# Jupiter_Ace_build023.net
KiCad netlist of a schematic drawn in EAGLE
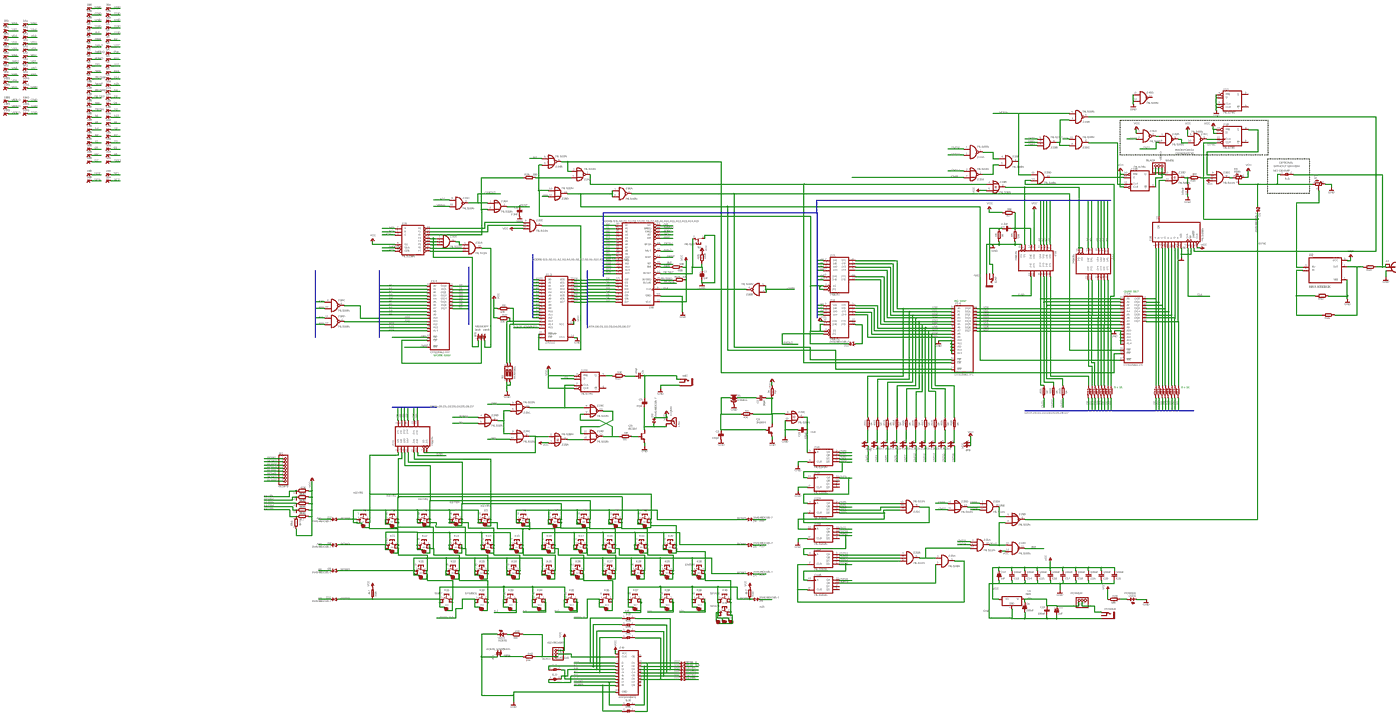
[diagram p0: schematic, sheet 1, overview]
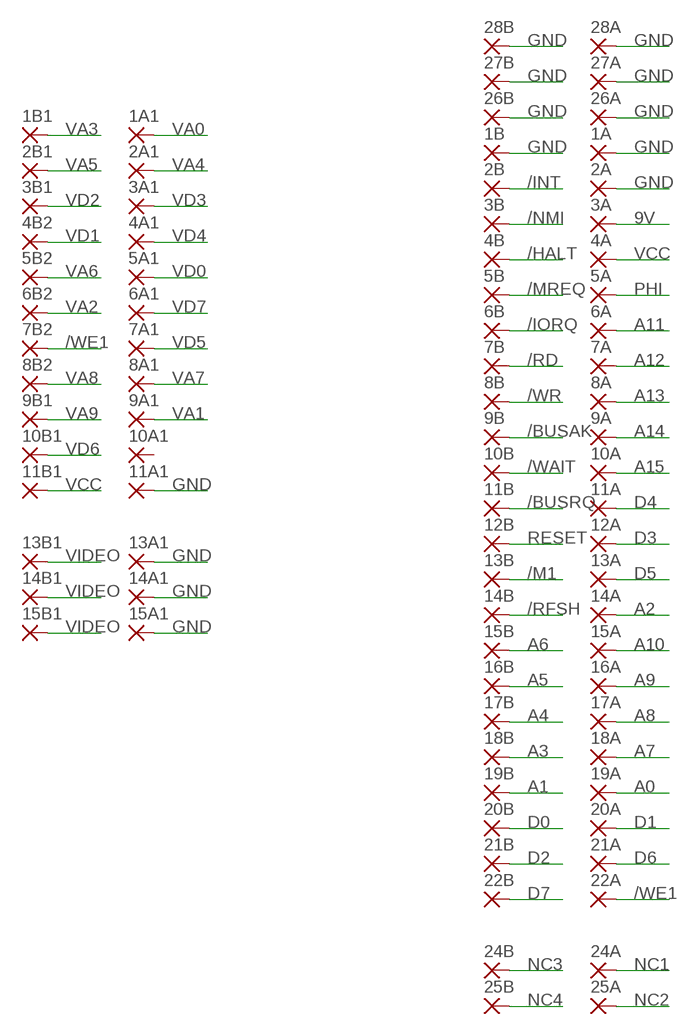
[diagram p1: schematic, sheet 1, part 1 of 5]
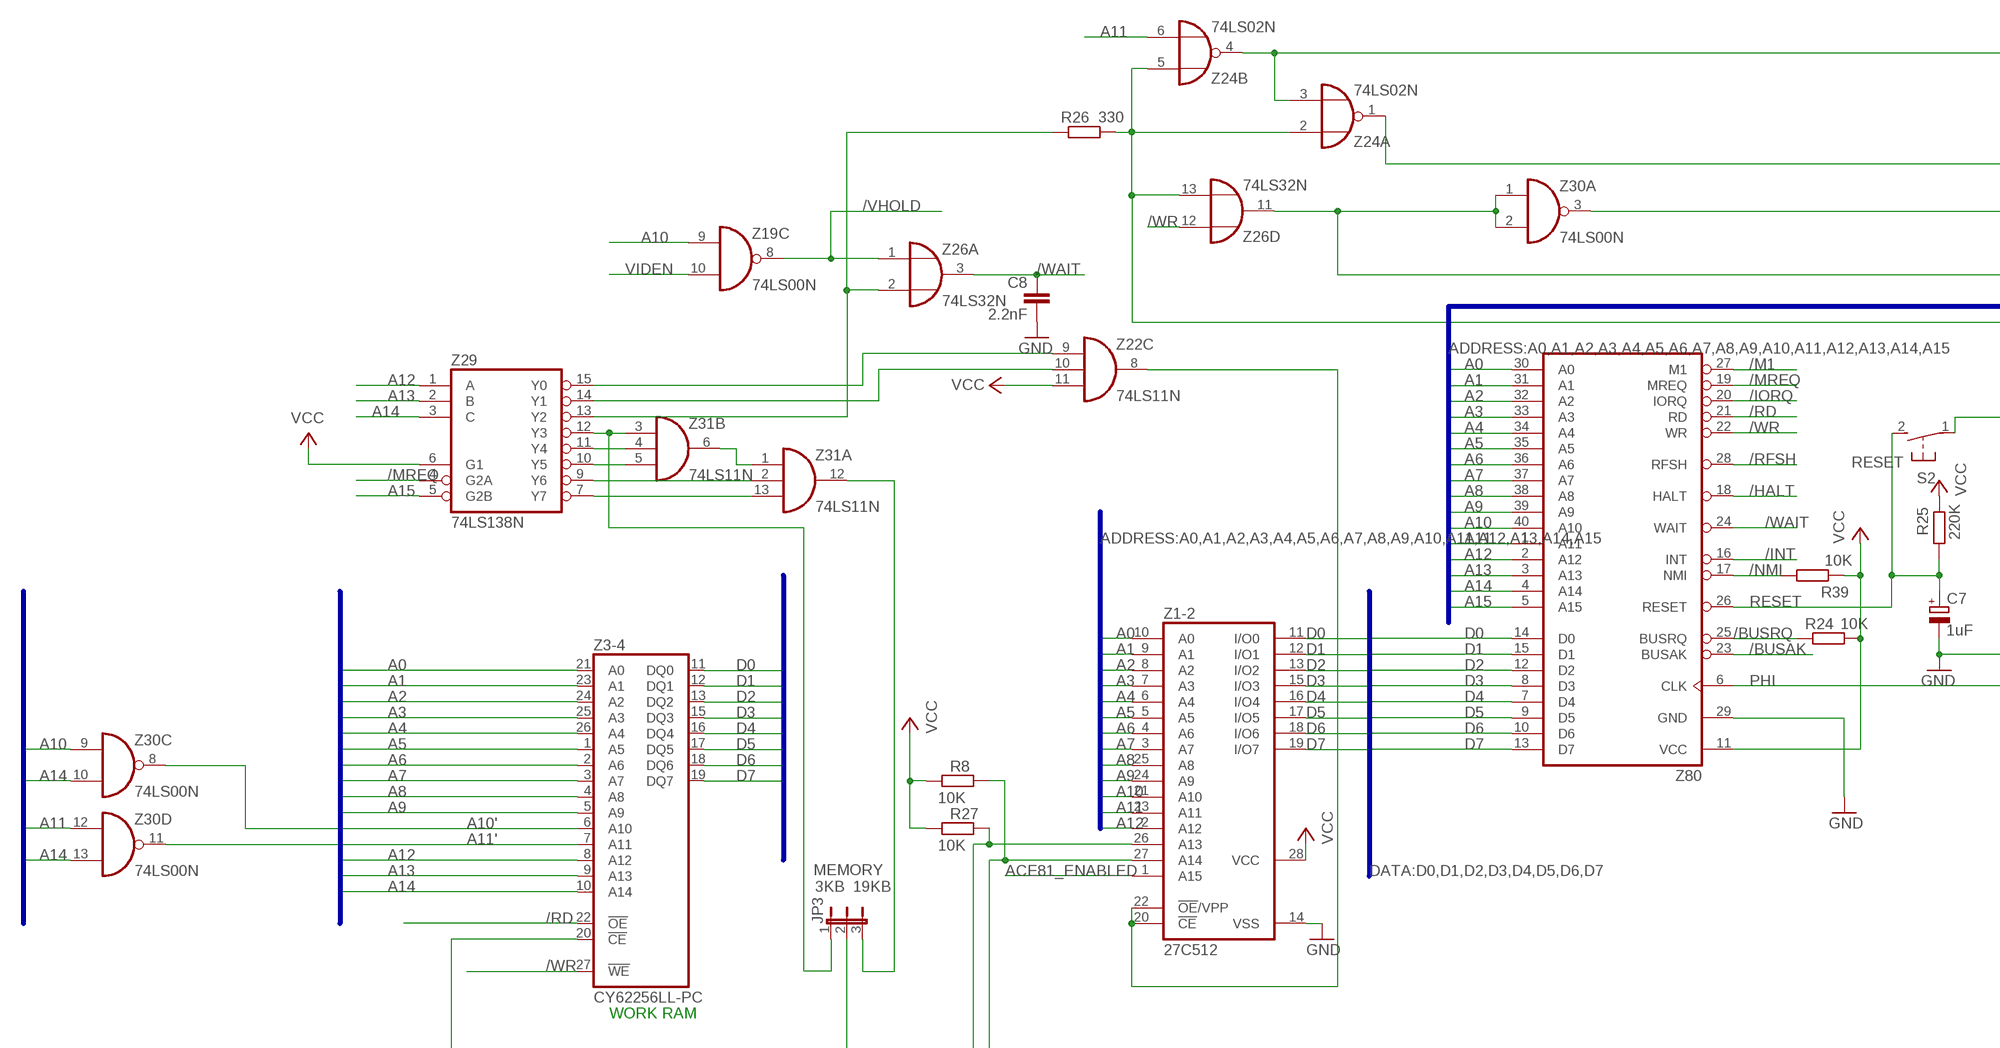
[diagram p2: schematic, sheet 1, part 2 of 5]
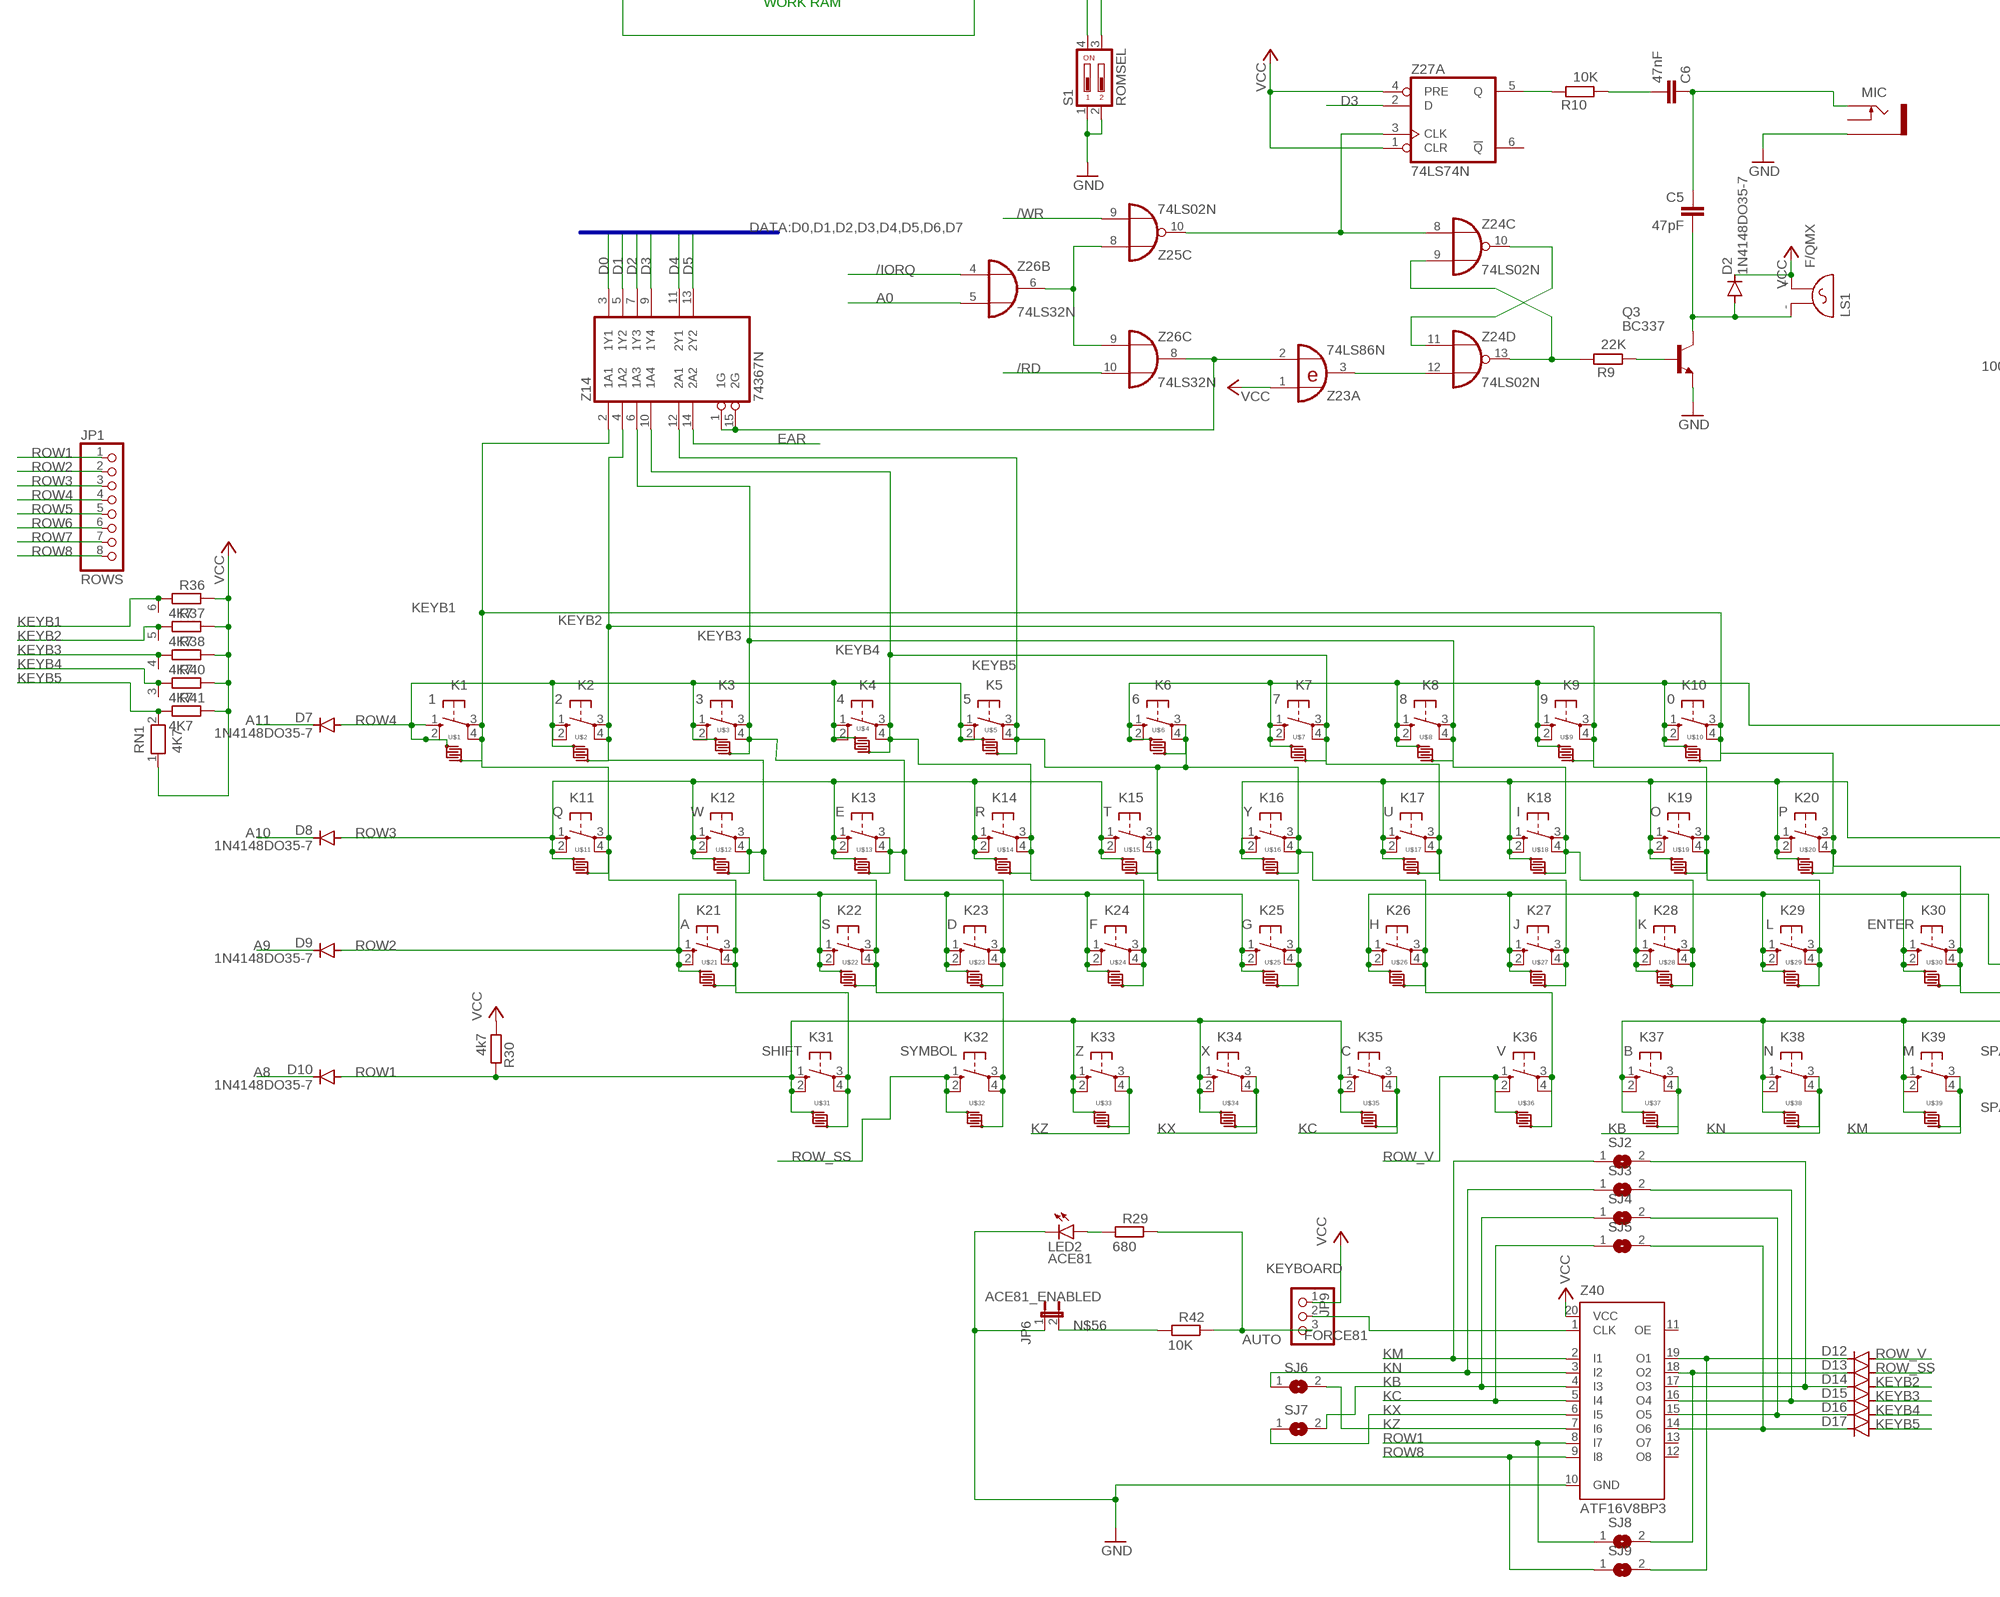
[diagram p3: schematic, sheet 1, part 3 of 5]
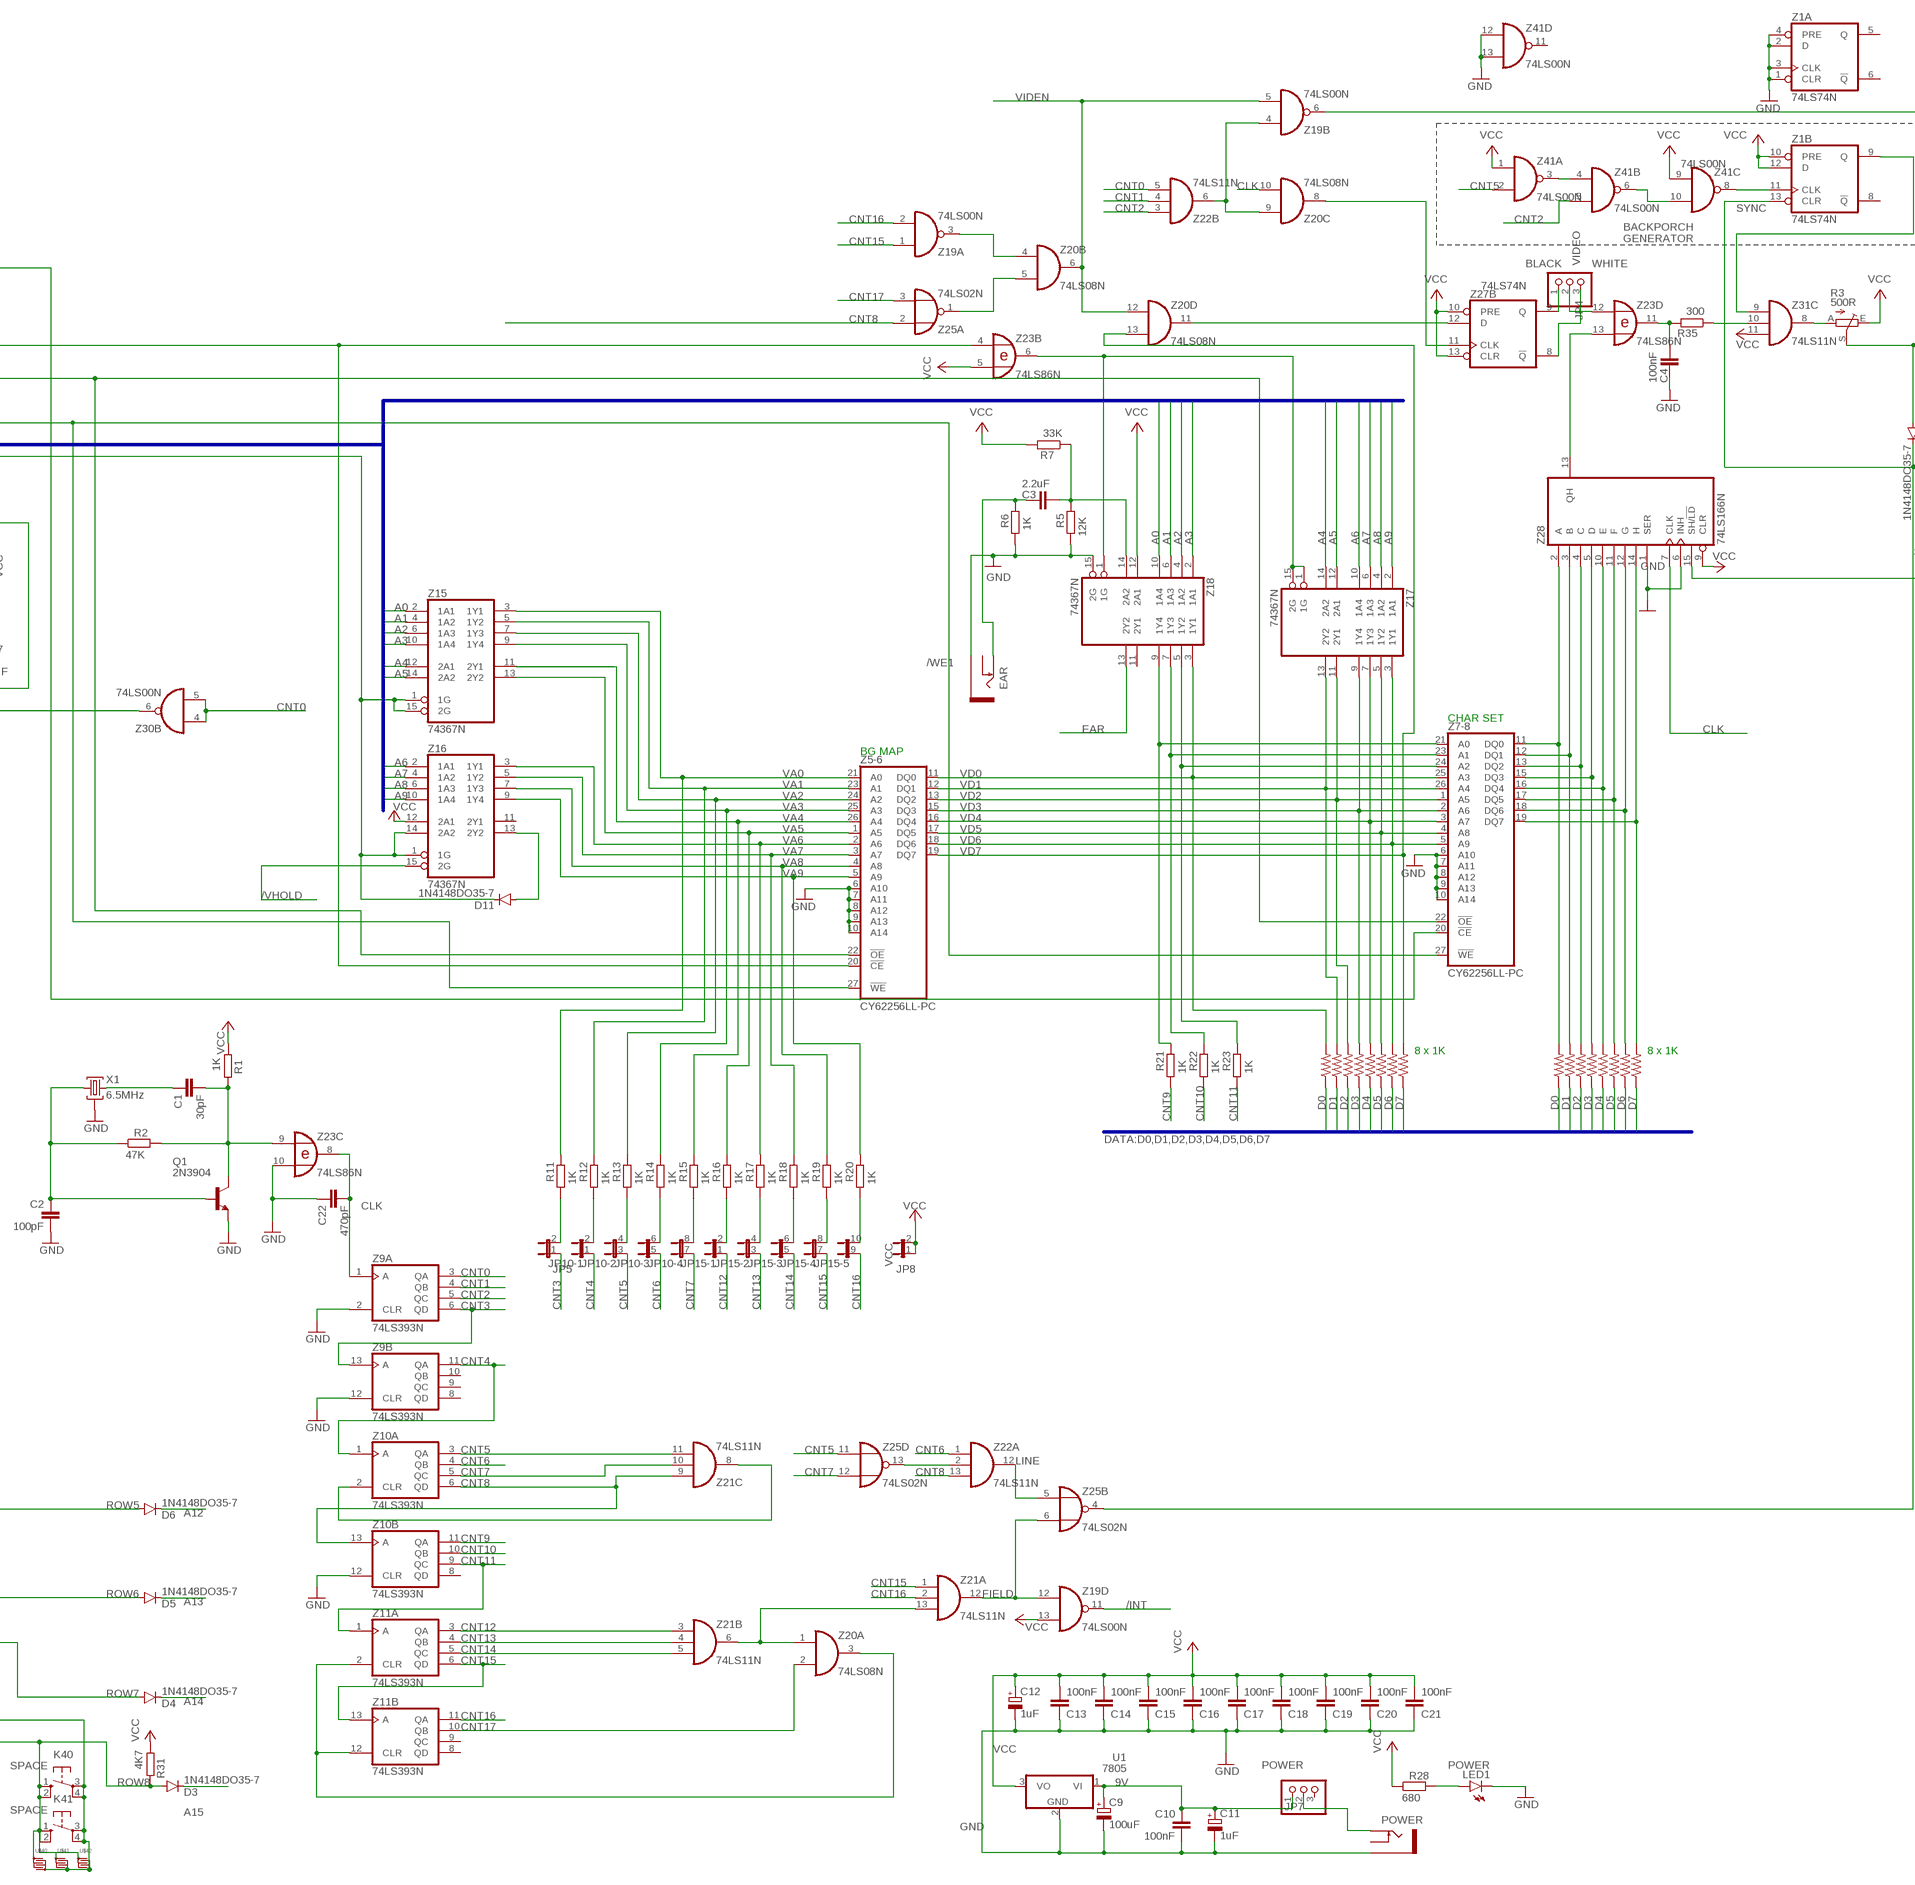
[diagram p4: schematic, sheet 1, part 4 of 5]
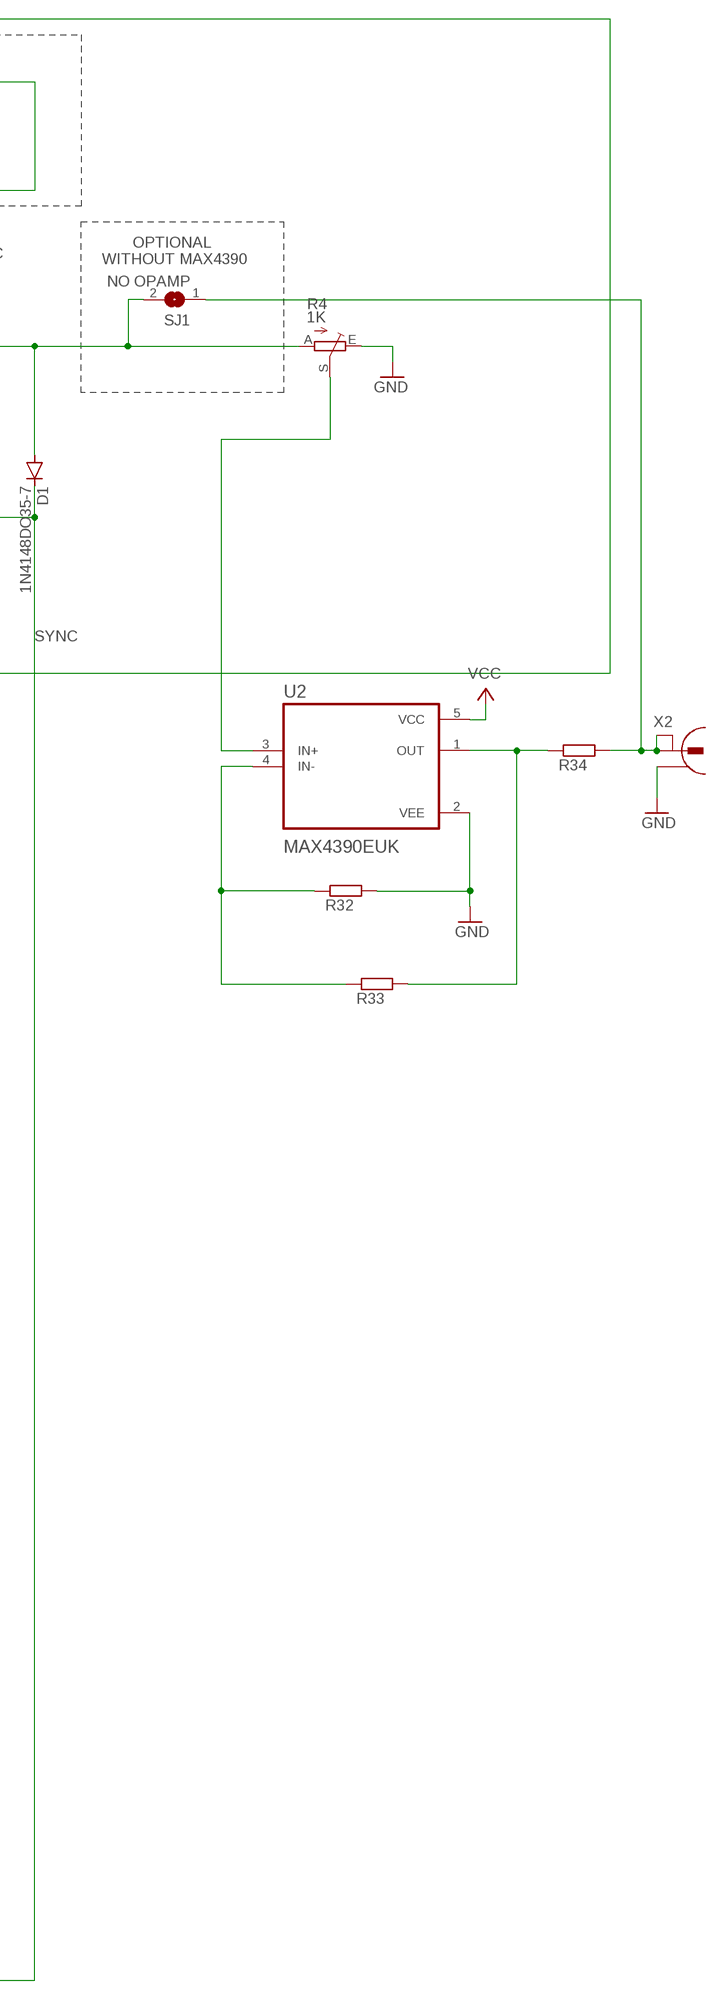
[diagram p5: schematic, sheet 1, part 5 of 5]

(export (version "E")
  (design (tool "Eeschema 10.0.6"))
  (components
    (comp (ref "1A")
      (value "SMD2EDGEPIN")
      (footprint "eagle-import:EDGEPIN")
      (libsource (lib "eagle-import") (part "SMD2EDGEPIN"))
    )
    (comp (ref "1A1")
      (value "SMD2EDGEPIN")
      (footprint "eagle-import:EDGEPIN")
      (libsource (lib "eagle-import") (part "SMD2EDGEPIN"))
    )
    (comp (ref "1B")
      (value "SMD2EDGEPIN")
      (footprint "eagle-import:EDGEPIN")
      (libsource (lib "eagle-import") (part "SMD2EDGEPIN"))
    )
    (comp (ref "1B1")
      (value "SMD2EDGEPIN")
      (footprint "eagle-import:EDGEPIN")
      (libsource (lib "eagle-import") (part "SMD2EDGEPIN"))
    )
    (comp (ref "2A")
      (value "SMD2EDGEPIN")
      (footprint "eagle-import:EDGEPIN")
      (libsource (lib "eagle-import") (part "SMD2EDGEPIN"))
    )
    (comp (ref "2A1")
      (value "SMD2EDGEPIN")
      (footprint "eagle-import:EDGEPIN")
      (libsource (lib "eagle-import") (part "SMD2EDGEPIN"))
    )
    (comp (ref "2B")
      (value "SMD2EDGEPIN")
      (footprint "eagle-import:EDGEPIN")
      (libsource (lib "eagle-import") (part "SMD2EDGEPIN"))
    )
    (comp (ref "2B1")
      (value "SMD2EDGEPIN")
      (footprint "eagle-import:EDGEPIN")
      (libsource (lib "eagle-import") (part "SMD2EDGEPIN"))
    )
    (comp (ref "3A")
      (value "SMD2EDGEPIN")
      (footprint "eagle-import:EDGEPIN")
      (libsource (lib "eagle-import") (part "SMD2EDGEPIN"))
    )
    (comp (ref "3A1")
      (value "SMD2EDGEPIN")
      (footprint "eagle-import:EDGEPIN")
      (libsource (lib "eagle-import") (part "SMD2EDGEPIN"))
    )
    (comp (ref "3B")
      (value "SMD2EDGEPIN")
      (footprint "eagle-import:EDGEPIN")
      (libsource (lib "eagle-import") (part "SMD2EDGEPIN"))
    )
    (comp (ref "3B1")
      (value "SMD2EDGEPIN")
      (footprint "eagle-import:EDGEPIN")
      (libsource (lib "eagle-import") (part "SMD2EDGEPIN"))
    )
    (comp (ref "4A")
      (value "SMD2EDGEPIN")
      (footprint "eagle-import:EDGEPIN")
      (libsource (lib "eagle-import") (part "SMD2EDGEPIN"))
    )
    (comp (ref "4A1")
      (value "SMD2EDGEPIN")
      (footprint "eagle-import:EDGEPIN")
      (libsource (lib "eagle-import") (part "SMD2EDGEPIN"))
    )
    (comp (ref "4B")
      (value "SMD2EDGEPIN")
      (footprint "eagle-import:EDGEPIN")
      (libsource (lib "eagle-import") (part "SMD2EDGEPIN"))
    )
    (comp (ref "4B2")
      (value "SMD2EDGEPIN")
      (footprint "eagle-import:EDGEPIN")
      (libsource (lib "eagle-import") (part "SMD2EDGEPIN"))
    )
    (comp (ref "5A")
      (value "SMD2EDGEPIN")
      (footprint "eagle-import:EDGEPIN")
      (libsource (lib "eagle-import") (part "SMD2EDGEPIN"))
    )
    (comp (ref "5A1")
      (value "SMD2EDGEPIN")
      (footprint "eagle-import:EDGEPIN")
      (libsource (lib "eagle-import") (part "SMD2EDGEPIN"))
    )
    (comp (ref "5B")
      (value "SMD2EDGEPIN")
      (footprint "eagle-import:EDGEPIN")
      (libsource (lib "eagle-import") (part "SMD2EDGEPIN"))
    )
    (comp (ref "5B2")
      (value "SMD2EDGEPIN")
      (footprint "eagle-import:EDGEPIN")
      (libsource (lib "eagle-import") (part "SMD2EDGEPIN"))
    )
    (comp (ref "6A")
      (value "SMD2EDGEPIN")
      (footprint "eagle-import:EDGEPIN")
      (libsource (lib "eagle-import") (part "SMD2EDGEPIN"))
    )
    (comp (ref "6A1")
      (value "SMD2EDGEPIN")
      (footprint "eagle-import:EDGEPIN")
      (libsource (lib "eagle-import") (part "SMD2EDGEPIN"))
    )
    (comp (ref "6B")
      (value "SMD2EDGEPIN")
      (footprint "eagle-import:EDGEPIN")
      (libsource (lib "eagle-import") (part "SMD2EDGEPIN"))
    )
    (comp (ref "6B2")
      (value "SMD2EDGEPIN")
      (footprint "eagle-import:EDGEPIN")
      (libsource (lib "eagle-import") (part "SMD2EDGEPIN"))
    )
    (comp (ref "7A")
      (value "SMD2EDGEPIN")
      (footprint "eagle-import:EDGEPIN")
      (libsource (lib "eagle-import") (part "SMD2EDGEPIN"))
    )
    (comp (ref "7A1")
      (value "SMD2EDGEPIN")
      (footprint "eagle-import:EDGEPIN")
      (libsource (lib "eagle-import") (part "SMD2EDGEPIN"))
    )
    (comp (ref "7B")
      (value "SMD2EDGEPIN")
      (footprint "eagle-import:EDGEPIN")
      (libsource (lib "eagle-import") (part "SMD2EDGEPIN"))
    )
    (comp (ref "7B2")
      (value "SMD2EDGEPIN")
      (footprint "eagle-import:EDGEPIN")
      (libsource (lib "eagle-import") (part "SMD2EDGEPIN"))
    )
    (comp (ref "8A")
      (value "SMD2EDGEPIN")
      (footprint "eagle-import:EDGEPIN")
      (libsource (lib "eagle-import") (part "SMD2EDGEPIN"))
    )
    (comp (ref "8A1")
      (value "SMD2EDGEPIN")
      (footprint "eagle-import:EDGEPIN")
      (libsource (lib "eagle-import") (part "SMD2EDGEPIN"))
    )
    (comp (ref "8B")
      (value "SMD2EDGEPIN")
      (footprint "eagle-import:EDGEPIN")
      (libsource (lib "eagle-import") (part "SMD2EDGEPIN"))
    )
    (comp (ref "8B2")
      (value "SMD2EDGEPIN")
      (footprint "eagle-import:EDGEPIN")
      (libsource (lib "eagle-import") (part "SMD2EDGEPIN"))
    )
    (comp (ref "9A")
      (value "SMD2EDGEPIN")
      (footprint "eagle-import:EDGEPIN")
      (libsource (lib "eagle-import") (part "SMD2EDGEPIN"))
    )
    (comp (ref "9A1")
      (value "SMD2EDGEPIN")
      (footprint "eagle-import:EDGEPIN")
      (libsource (lib "eagle-import") (part "SMD2EDGEPIN"))
    )
    (comp (ref "9B")
      (value "SMD2EDGEPIN")
      (footprint "eagle-import:EDGEPIN")
      (libsource (lib "eagle-import") (part "SMD2EDGEPIN"))
    )
    (comp (ref "9B1")
      (value "SMD2EDGEPIN")
      (footprint "eagle-import:EDGEPIN")
      (libsource (lib "eagle-import") (part "SMD2EDGEPIN"))
    )
    (comp (ref "10A")
      (value "SMD2EDGEPIN")
      (footprint "eagle-import:EDGEPIN")
      (libsource (lib "eagle-import") (part "SMD2EDGEPIN"))
    )
    (comp (ref "10A1")
      (value "SMD2EDGEPIN")
      (footprint "eagle-import:EDGEPIN")
      (libsource (lib "eagle-import") (part "SMD2EDGEPIN"))
    )
    (comp (ref "10B")
      (value "SMD2EDGEPIN")
      (footprint "eagle-import:EDGEPIN")
      (libsource (lib "eagle-import") (part "SMD2EDGEPIN"))
    )
    (comp (ref "10B1")
      (value "SMD2EDGEPIN")
      (footprint "eagle-import:EDGEPIN")
      (libsource (lib "eagle-import") (part "SMD2EDGEPIN"))
    )
    (comp (ref "11A")
      (value "SMD2EDGEPIN")
      (footprint "eagle-import:EDGEPIN")
      (libsource (lib "eagle-import") (part "SMD2EDGEPIN"))
    )
    (comp (ref "11A1")
      (value "SMD2EDGEPIN")
      (footprint "eagle-import:EDGEPIN")
      (libsource (lib "eagle-import") (part "SMD2EDGEPIN"))
    )
    (comp (ref "11B")
      (value "SMD2EDGEPIN")
      (footprint "eagle-import:EDGEPIN")
      (libsource (lib "eagle-import") (part "SMD2EDGEPIN"))
    )
    (comp (ref "11B1")
      (value "SMD2EDGEPIN")
      (footprint "eagle-import:EDGEPIN")
      (libsource (lib "eagle-import") (part "SMD2EDGEPIN"))
    )
    (comp (ref "12A")
      (value "SMD2EDGEPIN")
      (footprint "eagle-import:EDGEPIN")
      (libsource (lib "eagle-import") (part "SMD2EDGEPIN"))
    )
    (comp (ref "12B")
      (value "SMD2EDGEPIN")
      (footprint "eagle-import:EDGEPIN")
      (libsource (lib "eagle-import") (part "SMD2EDGEPIN"))
    )
    (comp (ref "13A")
      (value "SMD2EDGEPIN")
      (footprint "eagle-import:EDGEPIN")
      (libsource (lib "eagle-import") (part "SMD2EDGEPIN"))
    )
    (comp (ref "13A1")
      (value "SMD2EDGEPIN")
      (footprint "eagle-import:EDGEPIN")
      (libsource (lib "eagle-import") (part "SMD2EDGEPIN"))
    )
    (comp (ref "13B")
      (value "SMD2EDGEPIN")
      (footprint "eagle-import:EDGEPIN")
      (libsource (lib "eagle-import") (part "SMD2EDGEPIN"))
    )
    (comp (ref "13B1")
      (value "SMD2EDGEPIN")
      (footprint "eagle-import:EDGEPIN")
      (libsource (lib "eagle-import") (part "SMD2EDGEPIN"))
    )
    (comp (ref "14A")
      (value "SMD2EDGEPIN")
      (footprint "eagle-import:EDGEPIN")
      (libsource (lib "eagle-import") (part "SMD2EDGEPIN"))
    )
    (comp (ref "14A1")
      (value "SMD2EDGEPIN")
      (footprint "eagle-import:EDGEPIN")
      (libsource (lib "eagle-import") (part "SMD2EDGEPIN"))
    )
    (comp (ref "14B")
      (value "SMD2EDGEPIN")
      (footprint "eagle-import:EDGEPIN")
      (libsource (lib "eagle-import") (part "SMD2EDGEPIN"))
    )
    (comp (ref "14B1")
      (value "SMD2EDGEPIN")
      (footprint "eagle-import:EDGEPIN")
      (libsource (lib "eagle-import") (part "SMD2EDGEPIN"))
    )
    (comp (ref "15A")
      (value "SMD2EDGEPIN")
      (footprint "eagle-import:EDGEPIN")
      (libsource (lib "eagle-import") (part "SMD2EDGEPIN"))
    )
    (comp (ref "15A1")
      (value "SMD2EDGEPIN")
      (footprint "eagle-import:EDGEPIN")
      (libsource (lib "eagle-import") (part "SMD2EDGEPIN"))
    )
    (comp (ref "15B")
      (value "SMD2EDGEPIN")
      (footprint "eagle-import:EDGEPIN")
      (libsource (lib "eagle-import") (part "SMD2EDGEPIN"))
    )
    (comp (ref "15B1")
      (value "SMD2EDGEPIN")
      (footprint "eagle-import:EDGEPIN")
      (libsource (lib "eagle-import") (part "SMD2EDGEPIN"))
    )
    (comp (ref "16A")
      (value "SMD2EDGEPIN")
      (footprint "eagle-import:EDGEPIN")
      (libsource (lib "eagle-import") (part "SMD2EDGEPIN"))
    )
    (comp (ref "16B")
      (value "SMD2EDGEPIN")
      (footprint "eagle-import:EDGEPIN")
      (libsource (lib "eagle-import") (part "SMD2EDGEPIN"))
    )
    (comp (ref "17A")
      (value "SMD2EDGEPIN")
      (footprint "eagle-import:EDGEPIN")
      (libsource (lib "eagle-import") (part "SMD2EDGEPIN"))
    )
    (comp (ref "17B")
      (value "SMD2EDGEPIN")
      (footprint "eagle-import:EDGEPIN")
      (libsource (lib "eagle-import") (part "SMD2EDGEPIN"))
    )
    (comp (ref "18A")
      (value "SMD2EDGEPIN")
      (footprint "eagle-import:EDGEPIN")
      (libsource (lib "eagle-import") (part "SMD2EDGEPIN"))
    )
    (comp (ref "18B")
      (value "SMD2EDGEPIN")
      (footprint "eagle-import:EDGEPIN")
      (libsource (lib "eagle-import") (part "SMD2EDGEPIN"))
    )
    (comp (ref "19A")
      (value "SMD2EDGEPIN")
      (footprint "eagle-import:EDGEPIN")
      (libsource (lib "eagle-import") (part "SMD2EDGEPIN"))
    )
    (comp (ref "19B")
      (value "SMD2EDGEPIN")
      (footprint "eagle-import:EDGEPIN")
      (libsource (lib "eagle-import") (part "SMD2EDGEPIN"))
    )
    (comp (ref "20A")
      (value "SMD2EDGEPIN")
      (footprint "eagle-import:EDGEPIN")
      (libsource (lib "eagle-import") (part "SMD2EDGEPIN"))
    )
    (comp (ref "20B")
      (value "SMD2EDGEPIN")
      (footprint "eagle-import:EDGEPIN")
      (libsource (lib "eagle-import") (part "SMD2EDGEPIN"))
    )
    (comp (ref "21A")
      (value "SMD2EDGEPIN")
      (footprint "eagle-import:EDGEPIN")
      (libsource (lib "eagle-import") (part "SMD2EDGEPIN"))
    )
    (comp (ref "21B")
      (value "SMD2EDGEPIN")
      (footprint "eagle-import:EDGEPIN")
      (libsource (lib "eagle-import") (part "SMD2EDGEPIN"))
    )
    (comp (ref "22A")
      (value "SMD2EDGEPIN")
      (footprint "eagle-import:EDGEPIN")
      (libsource (lib "eagle-import") (part "SMD2EDGEPIN"))
    )
    (comp (ref "22B")
      (value "SMD2EDGEPIN")
      (footprint "eagle-import:EDGEPIN")
      (libsource (lib "eagle-import") (part "SMD2EDGEPIN"))
    )
    (comp (ref "24A")
      (value "SMD2EDGEPIN")
      (footprint "eagle-import:EDGEPIN")
      (libsource (lib "eagle-import") (part "SMD2EDGEPIN"))
    )
    (comp (ref "24B")
      (value "SMD2EDGEPIN")
      (footprint "eagle-import:EDGEPIN")
      (libsource (lib "eagle-import") (part "SMD2EDGEPIN"))
    )
    (comp (ref "25A")
      (value "SMD2EDGEPIN")
      (footprint "eagle-import:EDGEPIN")
      (libsource (lib "eagle-import") (part "SMD2EDGEPIN"))
    )
    (comp (ref "25B")
      (value "SMD2EDGEPIN")
      (footprint "eagle-import:EDGEPIN")
      (libsource (lib "eagle-import") (part "SMD2EDGEPIN"))
    )
    (comp (ref "26A")
      (value "SMD2EDGEPIN")
      (footprint "eagle-import:EDGEPIN")
      (libsource (lib "eagle-import") (part "SMD2EDGEPIN"))
    )
    (comp (ref "26B")
      (value "SMD2EDGEPIN")
      (footprint "eagle-import:EDGEPIN")
      (libsource (lib "eagle-import") (part "SMD2EDGEPIN"))
    )
    (comp (ref "27A")
      (value "SMD2EDGEPIN")
      (footprint "eagle-import:EDGEPIN")
      (libsource (lib "eagle-import") (part "SMD2EDGEPIN"))
    )
    (comp (ref "27B")
      (value "SMD2EDGEPIN")
      (footprint "eagle-import:EDGEPIN")
      (libsource (lib "eagle-import") (part "SMD2EDGEPIN"))
    )
    (comp (ref "28A")
      (value "SMD2EDGEPIN")
      (footprint "eagle-import:EDGEPIN")
      (libsource (lib "eagle-import") (part "SMD2EDGEPIN"))
    )
    (comp (ref "28B")
      (value "SMD2EDGEPIN")
      (footprint "eagle-import:EDGEPIN")
      (libsource (lib "eagle-import") (part "SMD2EDGEPIN"))
    )
    (comp (ref "C1")
      (value "30pF")
      (footprint "eagle-import:C025-025X050")
      (libsource (lib "eagle-import") (part "C-EU025-025X050"))
    )
    (comp (ref "C2")
      (value "100pF")
      (footprint "eagle-import:C025-025X050")
      (libsource (lib "eagle-import") (part "C-EU025-025X050"))
    )
    (comp (ref "C3")
      (value "2.2uF")
      (footprint "eagle-import:C025-025X050")
      (libsource (lib "eagle-import") (part "C-EU025-025X050"))
    )
    (comp (ref "C4")
      (value "100nF")
      (footprint "eagle-import:C025-025X050")
      (libsource (lib "eagle-import") (part "C-EU025-025X050"))
    )
    (comp (ref "C5")
      (value "47pF")
      (footprint "eagle-import:C025-025X050")
      (libsource (lib "eagle-import") (part "C-EU025-025X050"))
    )
    (comp (ref "C6")
      (value "47nF")
      (footprint "eagle-import:C025-025X050")
      (libsource (lib "eagle-import") (part "C-EU025-025X050"))
    )
    (comp (ref "C7")
      (value "1uF")
      (footprint "eagle-import:E1,8-4")
      (libsource (lib "eagle-import") (part "CPOL-EUE1.8-4"))
    )
    (comp (ref "C8")
      (value "2.2nF")
      (footprint "eagle-import:C025-025X050")
      (libsource (lib "eagle-import") (part "C-EU025-025X050"))
    )
    (comp (ref "C9")
      (value "100uF")
      (footprint "eagle-import:E1,8-4")
      (libsource (lib "eagle-import") (part "CPOL-EUE1.8-4"))
    )
    (comp (ref "C10")
      (value "100nF")
      (footprint "eagle-import:C025-025X050")
      (libsource (lib "eagle-import") (part "C-EU025-025X050"))
    )
    (comp (ref "C11")
      (value "1uF")
      (footprint "eagle-import:E1,8-4")
      (libsource (lib "eagle-import") (part "CPOL-EUE1.8-4"))
    )
    (comp (ref "C12")
      (value "1uF")
      (footprint "eagle-import:E1,8-4")
      (libsource (lib "eagle-import") (part "CPOL-EUE1.8-4"))
    )
    (comp (ref "C13")
      (value "100nF")
      (footprint "eagle-import:C025-025X050")
      (libsource (lib "eagle-import") (part "C-EU025-025X050"))
    )
    (comp (ref "C14")
      (value "100nF")
      (footprint "eagle-import:C025-025X050")
      (libsource (lib "eagle-import") (part "C-EU025-025X050"))
    )
    (comp (ref "C15")
      (value "100nF")
      (footprint "eagle-import:C025-025X050")
      (libsource (lib "eagle-import") (part "C-EU025-025X050"))
    )
    (comp (ref "C16")
      (value "100nF")
      (footprint "eagle-import:C025-025X050")
      (libsource (lib "eagle-import") (part "C-EU025-025X050"))
    )
    (comp (ref "C17")
      (value "100nF")
      (footprint "eagle-import:C025-025X050")
      (libsource (lib "eagle-import") (part "C-EU025-025X050"))
    )
    (comp (ref "C18")
      (value "100nF")
      (footprint "eagle-import:C025-025X050")
      (libsource (lib "eagle-import") (part "C-EU025-025X050"))
    )
    (comp (ref "C19")
      (value "100nF")
      (footprint "eagle-import:C025-025X050")
      (libsource (lib "eagle-import") (part "C-EU025-025X050"))
    )
    (comp (ref "C20")
      (value "100nF")
      (footprint "eagle-import:C025-025X050")
      (libsource (lib "eagle-import") (part "C-EU025-025X050"))
    )
    (comp (ref "C21")
      (value "100nF")
      (footprint "eagle-import:C025-025X050")
      (libsource (lib "eagle-import") (part "C-EU025-025X050"))
    )
    (comp (ref "C22")
      (value "470pF")
      (footprint "eagle-import:C025-025X050")
      (libsource (lib "eagle-import") (part "C-EU025-025X050"))
    )
    (comp (ref "D1")
      (value "1N4148DO35-7")
      (footprint "eagle-import:DO35-7")
      (libsource (lib "eagle-import") (part "1N4148DO35-7"))
    )
    (comp (ref "D2")
      (value "1N4148DO35-7")
      (footprint "eagle-import:DO35-7")
      (libsource (lib "eagle-import") (part "1N4148DO35-7"))
    )
    (comp (ref "D3")
      (value "1N4148DO35-7")
      (footprint "eagle-import:DO35-7")
      (libsource (lib "eagle-import") (part "1N4148DO35-7"))
    )
    (comp (ref "D4")
      (value "1N4148DO35-7")
      (footprint "eagle-import:DO35-7")
      (libsource (lib "eagle-import") (part "1N4148DO35-7"))
    )
    (comp (ref "D5")
      (value "1N4148DO35-7")
      (footprint "eagle-import:DO35-7")
      (libsource (lib "eagle-import") (part "1N4148DO35-7"))
    )
    (comp (ref "D6")
      (value "1N4148DO35-7")
      (footprint "eagle-import:DO35-7")
      (libsource (lib "eagle-import") (part "1N4148DO35-7"))
    )
    (comp (ref "D7")
      (value "1N4148DO35-7")
      (footprint "eagle-import:DO35-7")
      (libsource (lib "eagle-import") (part "1N4148DO35-7"))
    )
    (comp (ref "D8")
      (value "1N4148DO35-7")
      (footprint "eagle-import:DO35-7")
      (libsource (lib "eagle-import") (part "1N4148DO35-7"))
    )
    (comp (ref "D9")
      (value "1N4148DO35-7")
      (footprint "eagle-import:DO35-7")
      (libsource (lib "eagle-import") (part "1N4148DO35-7"))
    )
    (comp (ref "D10")
      (value "1N4148DO35-7")
      (footprint "eagle-import:DO35-7")
      (libsource (lib "eagle-import") (part "1N4148DO35-7"))
    )
    (comp (ref "D11")
      (value "1N4148DO35-7")
      (footprint "eagle-import:DO35-7")
      (libsource (lib "eagle-import") (part "1N4148DO35-7"))
    )
    (comp (ref "D12")
      (value "1N4148DO35-7")
      (footprint "eagle-import:DO35-7")
      (libsource (lib "eagle-import") (part "1N4148DO35-7"))
    )
    (comp (ref "D13")
      (value "1N4148DO35-7")
      (footprint "eagle-import:DO35-7")
      (libsource (lib "eagle-import") (part "1N4148DO35-7"))
    )
    (comp (ref "D14")
      (value "1N4148DO35-7")
      (footprint "eagle-import:DO35-7")
      (libsource (lib "eagle-import") (part "1N4148DO35-7"))
    )
    (comp (ref "D15")
      (value "1N4148DO35-7")
      (footprint "eagle-import:DO35-7")
      (libsource (lib "eagle-import") (part "1N4148DO35-7"))
    )
    (comp (ref "D16")
      (value "1N4148DO35-7")
      (footprint "eagle-import:DO35-7")
      (libsource (lib "eagle-import") (part "1N4148DO35-7"))
    )
    (comp (ref "D17")
      (value "1N4148DO35-7")
      (footprint "eagle-import:DO35-7")
      (libsource (lib "eagle-import") (part "1N4148DO35-7"))
    )
    (comp (ref "EAR")
      (value "PJ302M")
      (footprint "eagle-import:PJ302M")
      (libsource (lib "eagle-import") (part "PJ302M"))
    )
    (comp (ref "JP1")
      (value "ROWS")
      (footprint "eagle-import:1X08")
      (libsource (lib "eagle-import") (part "PINHD-1X8"))
    )
    (comp (ref "JP3")
      (value "MEMORY")
      (footprint "eagle-import:JP2")
      (libsource (lib "eagle-import") (part "JP2E"))
    )
    (comp (ref "JP4")
      (value "VIDEO")
      (footprint "eagle-import:1X03")
      (libsource (lib "eagle-import") (part "PINHD-1X3"))
    )
    (comp (ref "JP5")
      (value "JP1E1Q")
      (footprint "eagle-import:JP1Q")
      (libsource (lib "eagle-import") (part "JP1E1Q"))
    )
    (comp (ref "JP6")
      (value "ACE81_ENABLED")
      (footprint "eagle-import:JP1Q")
      (libsource (lib "eagle-import") (part "JP1E1Q"))
    )
    (comp (ref "JP7")
      (value "POWER")
      (footprint "eagle-import:1X03")
      (libsource (lib "eagle-import") (part "PINHD-1X3"))
    )
    (comp (ref "JP8")
      (value "VCC")
      (footprint "eagle-import:JP1Q")
      (libsource (lib "eagle-import") (part "JP1E1Q"))
    )
    (comp (ref "JP9")
      (value "KEYBOARD")
      (footprint "eagle-import:1X03")
      (libsource (lib "eagle-import") (part "PINHD-1X3"))
    )
    (comp (ref "JP10")
      (value "JP4QE")
      (footprint "eagle-import:JP4Q")
      (libsource (lib "eagle-import") (part "JP4QE"))
    )
    (comp (ref "JP15")
      (value "JP5QE")
      (footprint "eagle-import:JP5Q")
      (libsource (lib "eagle-import") (part "JP5QE"))
    )
    (comp (ref "K1")
      (value "1")
      (footprint "eagle-import:B3F-40XXNOHOLE")
      (libsource (lib "eagle-import") (part "40-XXNOHOLES"))
    )
    (comp (ref "K2")
      (value "2")
      (footprint "eagle-import:B3F-40XXNOHOLE")
      (libsource (lib "eagle-import") (part "40-XXNOHOLES"))
    )
    (comp (ref "K3")
      (value "3")
      (footprint "eagle-import:B3F-40XXNOHOLE")
      (libsource (lib "eagle-import") (part "40-XXNOHOLES"))
    )
    (comp (ref "K4")
      (value "4")
      (footprint "eagle-import:B3F-40XXNOHOLE")
      (libsource (lib "eagle-import") (part "40-XXNOHOLES"))
    )
    (comp (ref "K5")
      (value "5")
      (footprint "eagle-import:B3F-40XXNOHOLE")
      (libsource (lib "eagle-import") (part "40-XXNOHOLES"))
    )
    (comp (ref "K6")
      (value "6")
      (footprint "eagle-import:B3F-40XXNOHOLE")
      (libsource (lib "eagle-import") (part "40-XXNOHOLES"))
    )
    (comp (ref "K7")
      (value "7")
      (footprint "eagle-import:B3F-40XXNOHOLE")
      (libsource (lib "eagle-import") (part "40-XXNOHOLES"))
    )
    (comp (ref "K8")
      (value "8")
      (footprint "eagle-import:B3F-40XXNOHOLE")
      (libsource (lib "eagle-import") (part "40-XXNOHOLES"))
    )
    (comp (ref "K9")
      (value "9")
      (footprint "eagle-import:B3F-40XXNOHOLE")
      (libsource (lib "eagle-import") (part "40-XXNOHOLES"))
    )
    (comp (ref "K10")
      (value "0")
      (footprint "eagle-import:B3F-40XXNOHOLE")
      (libsource (lib "eagle-import") (part "40-XXNOHOLES"))
    )
    (comp (ref "K11")
      (value "Q")
      (footprint "eagle-import:B3F-40XXNOHOLE")
      (libsource (lib "eagle-import") (part "40-XXNOHOLES"))
    )
    (comp (ref "K12")
      (value "W")
      (footprint "eagle-import:B3F-40XXNOHOLE")
      (libsource (lib "eagle-import") (part "40-XXNOHOLES"))
    )
    (comp (ref "K13")
      (value "E")
      (footprint "eagle-import:B3F-40XXNOHOLE")
      (libsource (lib "eagle-import") (part "40-XXNOHOLES"))
    )
    (comp (ref "K14")
      (value "R")
      (footprint "eagle-import:B3F-40XXNOHOLE")
      (libsource (lib "eagle-import") (part "40-XXNOHOLES"))
    )
    (comp (ref "K15")
      (value "T")
      (footprint "eagle-import:B3F-40XXNOHOLE")
      (libsource (lib "eagle-import") (part "40-XXNOHOLES"))
    )
    (comp (ref "K16")
      (value "Y")
      (footprint "eagle-import:B3F-40XXNOHOLE")
      (libsource (lib "eagle-import") (part "40-XXNOHOLES"))
    )
    (comp (ref "K17")
      (value "U")
      (footprint "eagle-import:B3F-40XXNOHOLE")
      (libsource (lib "eagle-import") (part "40-XXNOHOLES"))
    )
    (comp (ref "K18")
      (value "I")
      (footprint "eagle-import:B3F-40XXNOHOLE")
      (libsource (lib "eagle-import") (part "40-XXNOHOLES"))
    )
    (comp (ref "K19")
      (value "O")
      (footprint "eagle-import:B3F-40XXNOHOLE")
      (libsource (lib "eagle-import") (part "40-XXNOHOLES"))
    )
    (comp (ref "K20")
      (value "P")
      (footprint "eagle-import:B3F-40XXNOHOLE")
      (libsource (lib "eagle-import") (part "40-XXNOHOLES"))
    )
    (comp (ref "K21")
      (value "A")
      (footprint "eagle-import:B3F-40XXNOHOLE")
      (libsource (lib "eagle-import") (part "40-XXNOHOLES"))
    )
    (comp (ref "K22")
      (value "S")
      (footprint "eagle-import:B3F-40XXNOHOLE")
      (libsource (lib "eagle-import") (part "40-XXNOHOLES"))
    )
    (comp (ref "K23")
      (value "D")
      (footprint "eagle-import:B3F-40XXNOHOLE")
      (libsource (lib "eagle-import") (part "40-XXNOHOLES"))
    )
    (comp (ref "K24")
      (value "F")
      (footprint "eagle-import:B3F-40XXNOHOLE")
      (libsource (lib "eagle-import") (part "40-XXNOHOLES"))
    )
    (comp (ref "K25")
      (value "G")
      (footprint "eagle-import:B3F-40XXNOHOLE")
      (libsource (lib "eagle-import") (part "40-XXNOHOLES"))
    )
    (comp (ref "K26")
      (value "H")
      (footprint "eagle-import:B3F-40XXNOHOLE")
      (libsource (lib "eagle-import") (part "40-XXNOHOLES"))
    )
    (comp (ref "K27")
      (value "J")
      (footprint "eagle-import:B3F-40XXNOHOLE")
      (libsource (lib "eagle-import") (part "40-XXNOHOLES"))
    )
    (comp (ref "K28")
      (value "K")
      (footprint "eagle-import:B3F-40XXNOHOLE")
      (libsource (lib "eagle-import") (part "40-XXNOHOLES"))
    )
    (comp (ref "K29")
      (value "L")
      (footprint "eagle-import:B3F-40XXNOHOLE")
      (libsource (lib "eagle-import") (part "40-XXNOHOLES"))
    )
    (comp (ref "K30")
      (value "ENTER")
      (footprint "eagle-import:B3F-40XXNOHOLE")
      (libsource (lib "eagle-import") (part "40-XXNOHOLES"))
    )
    (comp (ref "K31")
      (value "SHIFT")
      (footprint "eagle-import:B3F-40XXNOHOLE")
      (libsource (lib "eagle-import") (part "40-XXNOHOLES"))
    )
    (comp (ref "K32")
      (value "SYMBOL")
      (footprint "eagle-import:B3F-40XXNOHOLE")
      (libsource (lib "eagle-import") (part "40-XXNOHOLES"))
    )
    (comp (ref "K33")
      (value "Z")
      (footprint "eagle-import:B3F-40XXNOHOLE")
      (libsource (lib "eagle-import") (part "40-XXNOHOLES"))
    )
    (comp (ref "K34")
      (value "X")
      (footprint "eagle-import:B3F-40XXNOHOLE")
      (libsource (lib "eagle-import") (part "40-XXNOHOLES"))
    )
    (comp (ref "K35")
      (value "C")
      (footprint "eagle-import:B3F-40XXNOHOLE")
      (libsource (lib "eagle-import") (part "40-XXNOHOLES"))
    )
    (comp (ref "K36")
      (value "V")
      (footprint "eagle-import:B3F-40XXNOHOLE")
      (libsource (lib "eagle-import") (part "40-XXNOHOLES"))
    )
    (comp (ref "K37")
      (value "B")
      (footprint "eagle-import:B3F-40XXNOHOLE")
      (libsource (lib "eagle-import") (part "40-XXNOHOLES"))
    )
    (comp (ref "K38")
      (value "N")
      (footprint "eagle-import:B3F-40XXNOHOLE")
      (libsource (lib "eagle-import") (part "40-XXNOHOLES"))
    )
    (comp (ref "K39")
      (value "M")
      (footprint "eagle-import:B3F-40XXNOHOLE")
      (libsource (lib "eagle-import") (part "40-XXNOHOLES"))
    )
    (comp (ref "K40")
      (value "SPACE")
      (footprint "eagle-import:B3F-40XXNOHOLE")
      (libsource (lib "eagle-import") (part "40-XXNOHOLES"))
    )
    (comp (ref "K41")
      (value "SPACE")
      (footprint "eagle-import:B3F-40XXNOHOLE")
      (libsource (lib "eagle-import") (part "40-XXNOHOLES"))
    )
    (comp (ref "LED1")
      (value "POWER")
      (footprint "eagle-import:LED3MM")
      (libsource (lib "eagle-import") (part "LED3MM"))
    )
    (comp (ref "LED2")
      (value "ACE81")
      (footprint "eagle-import:LED3MM")
      (libsource (lib "eagle-import") (part "LED3MM"))
    )
    (comp (ref "LS1")
      (value "F/QMX")
      (footprint "eagle-import:F_QMX")
      (libsource (lib "eagle-import") (part "F/QMX"))
    )
    (comp (ref "MIC")
      (value "PJ302M")
      (footprint "eagle-import:PJ302M")
      (libsource (lib "eagle-import") (part "PJ302M"))
    )
    (comp (ref "POWER")
      (value "PJ302M")
      (footprint "eagle-import:PJ302M")
      (libsource (lib "eagle-import") (part "PJ302M"))
    )
    (comp (ref "Q1")
      (value "2N3904")
      (footprint "eagle-import:TO92")
      (libsource (lib "eagle-import") (part "2N3904"))
    )
    (comp (ref "Q3")
      (value "BC337")
      (footprint "eagle-import:TO92")
      (libsource (lib "eagle-import") (part "BC337"))
    )
    (comp (ref "R1")
      (value "1K")
      (footprint "eagle-import:0204_7")
      (libsource (lib "eagle-import") (part "R-EU_0204/7"))
    )
    (comp (ref "R2")
      (value "47K")
      (footprint "eagle-import:0204_7")
      (libsource (lib "eagle-import") (part "R-EU_0204/7"))
    )
    (comp (ref "R3")
      (value "500R")
      (footprint "eagle-import:B25P")
      (libsource (lib "eagle-import") (part "TRIM_EU-B25P"))
    )
    (comp (ref "R4")
      (value "1K")
      (footprint "eagle-import:B25P")
      (libsource (lib "eagle-import") (part "TRIM_EU-B25P"))
    )
    (comp (ref "R5")
      (value "12K")
      (footprint "eagle-import:0204_7")
      (libsource (lib "eagle-import") (part "R-EU_0204/7"))
    )
    (comp (ref "R6")
      (value "1K")
      (footprint "eagle-import:0204_7")
      (libsource (lib "eagle-import") (part "R-EU_0204/7"))
    )
    (comp (ref "R7")
      (value "33K")
      (footprint "eagle-import:0204_7")
      (libsource (lib "eagle-import") (part "R-EU_0204/7"))
    )
    (comp (ref "R8")
      (value "10K")
      (footprint "eagle-import:0204_7")
      (libsource (lib "eagle-import") (part "R-EU_0204/7"))
    )
    (comp (ref "R9")
      (value "22K")
      (footprint "eagle-import:0204_7")
      (libsource (lib "eagle-import") (part "R-EU_0204/7"))
    )
    (comp (ref "R10")
      (value "10K")
      (footprint "eagle-import:0204_7")
      (libsource (lib "eagle-import") (part "R-EU_0204/7"))
    )
    (comp (ref "R11")
      (value "1K")
      (footprint "eagle-import:0204_7")
      (libsource (lib "eagle-import") (part "R-EU_0204/7"))
    )
    (comp (ref "R12")
      (value "1K")
      (footprint "eagle-import:0204_7")
      (libsource (lib "eagle-import") (part "R-EU_0204/7"))
    )
    (comp (ref "R13")
      (value "1K")
      (footprint "eagle-import:0204_7")
      (libsource (lib "eagle-import") (part "R-EU_0204/7"))
    )
    (comp (ref "R14")
      (value "1K")
      (footprint "eagle-import:0204_7")
      (libsource (lib "eagle-import") (part "R-EU_0204/7"))
    )
    (comp (ref "R15")
      (value "1K")
      (footprint "eagle-import:0204_7")
      (libsource (lib "eagle-import") (part "R-EU_0204/7"))
    )
    (comp (ref "R16")
      (value "1K")
      (footprint "eagle-import:0204_7")
      (libsource (lib "eagle-import") (part "R-EU_0204/7"))
    )
    (comp (ref "R17")
      (value "1K")
      (footprint "eagle-import:0204_7")
      (libsource (lib "eagle-import") (part "R-EU_0204/7"))
    )
    (comp (ref "R18")
      (value "1K")
      (footprint "eagle-import:0204_7")
      (libsource (lib "eagle-import") (part "R-EU_0204/7"))
    )
    (comp (ref "R19")
      (value "1K")
      (footprint "eagle-import:0204_7")
      (libsource (lib "eagle-import") (part "R-EU_0204/7"))
    )
    (comp (ref "R20")
      (value "1K")
      (footprint "eagle-import:0204_7")
      (libsource (lib "eagle-import") (part "R-EU_0204/7"))
    )
    (comp (ref "R21")
      (value "1K")
      (footprint "eagle-import:0204_7")
      (libsource (lib "eagle-import") (part "R-EU_0204/7"))
    )
    (comp (ref "R22")
      (value "1K")
      (footprint "eagle-import:0204_7")
      (libsource (lib "eagle-import") (part "R-EU_0204/7"))
    )
    (comp (ref "R23")
      (value "1K")
      (footprint "eagle-import:0204_7")
      (libsource (lib "eagle-import") (part "R-EU_0204/7"))
    )
    (comp (ref "R24")
      (value "10K")
      (footprint "eagle-import:0204_7")
      (libsource (lib "eagle-import") (part "R-EU_0204/7"))
    )
    (comp (ref "R25")
      (value "220K")
      (footprint "eagle-import:0204_7")
      (libsource (lib "eagle-import") (part "R-EU_0204/7"))
    )
    (comp (ref "R26")
      (value "330")
      (footprint "eagle-import:0204_7")
      (libsource (lib "eagle-import") (part "R-EU_0204/7"))
    )
    (comp (ref "R27")
      (value "10K")
      (footprint "eagle-import:0204_7")
      (libsource (lib "eagle-import") (part "R-EU_0204/7"))
    )
    (comp (ref "R28")
      (value "680")
      (footprint "eagle-import:0204_7")
      (libsource (lib "eagle-import") (part "R-EU_0204/7"))
    )
    (comp (ref "R29")
      (value "680")
      (footprint "eagle-import:0204_7")
      (libsource (lib "eagle-import") (part "R-EU_0204/7"))
    )
    (comp (ref "R30")
      (value "4k7")
      (footprint "eagle-import:0204_7")
      (libsource (lib "eagle-import") (part "R-EU_0204/7"))
    )
    (comp (ref "R31")
      (value "4K7")
      (footprint "eagle-import:0204_7")
      (libsource (lib "eagle-import") (part "R-EU_0204/7"))
    )
    (comp (ref "R32")
      (value "R-EU_0204/7")
      (footprint "eagle-import:0204_7")
      (libsource (lib "eagle-import") (part "R-EU_0204/7"))
    )
    (comp (ref "R33")
      (value "R-EU_0204/7")
      (footprint "eagle-import:0204_7")
      (libsource (lib "eagle-import") (part "R-EU_0204/7"))
    )
    (comp (ref "R34")
      (value "R-EU_0204/7")
      (footprint "eagle-import:0204_7")
      (libsource (lib "eagle-import") (part "R-EU_0204/7"))
    )
    (comp (ref "R35")
      (value "300")
      (footprint "eagle-import:0204_7")
      (libsource (lib "eagle-import") (part "R-EU_0204/7"))
    )
    (comp (ref "R36")
      (value "4K7")
      (footprint "eagle-import:0207_10")
      (libsource (lib "eagle-import") (part "R-EU_0207/10"))
    )
    (comp (ref "R37")
      (value "4K7")
      (footprint "eagle-import:0207_10")
      (libsource (lib "eagle-import") (part "R-EU_0207/10"))
    )
    (comp (ref "R38")
      (value "4K7")
      (footprint "eagle-import:0207_10")
      (libsource (lib "eagle-import") (part "R-EU_0207/10"))
    )
    (comp (ref "R39")
      (value "10K")
      (footprint "eagle-import:0204_7")
      (libsource (lib "eagle-import") (part "R-EU_0204/7"))
    )
    (comp (ref "R40")
      (value "4K7")
      (footprint "eagle-import:0207_10")
      (libsource (lib "eagle-import") (part "R-EU_0207/10"))
    )
    (comp (ref "R41")
      (value "4K7")
      (footprint "eagle-import:0207_10")
      (libsource (lib "eagle-import") (part "R-EU_0207/10"))
    )
    (comp (ref "R42")
      (value "10K")
      (footprint "eagle-import:0204_7")
      (libsource (lib "eagle-import") (part "R-EU_0204/7"))
    )
    (comp (ref "R100")
      (value "1K")
      (footprint "eagle-import:0204V")
      (libsource (lib "eagle-import") (part "R-US_0204/2V"))
    )
    (comp (ref "R101")
      (value "1K")
      (footprint "eagle-import:0204V")
      (libsource (lib "eagle-import") (part "R-US_0204/2V"))
    )
    (comp (ref "R102")
      (value "1K")
      (footprint "eagle-import:0204V")
      (libsource (lib "eagle-import") (part "R-US_0204/2V"))
    )
    (comp (ref "R103")
      (value "1K")
      (footprint "eagle-import:0204V")
      (libsource (lib "eagle-import") (part "R-US_0204/2V"))
    )
    (comp (ref "R104")
      (value "1K")
      (footprint "eagle-import:0204V")
      (libsource (lib "eagle-import") (part "R-US_0204/2V"))
    )
    (comp (ref "R105")
      (value "1K")
      (footprint "eagle-import:0204V")
      (libsource (lib "eagle-import") (part "R-US_0204/2V"))
    )
    (comp (ref "R106")
      (value "1K")
      (footprint "eagle-import:0204V")
      (libsource (lib "eagle-import") (part "R-US_0204/2V"))
    )
    (comp (ref "R107")
      (value "1K")
      (footprint "eagle-import:0204V")
      (libsource (lib "eagle-import") (part "R-US_0204/2V"))
    )
    (comp (ref "R200")
      (value "1K")
      (footprint "eagle-import:0204V")
      (libsource (lib "eagle-import") (part "R-US_0204/2V"))
    )
    (comp (ref "R201")
      (value "1K")
      (footprint "eagle-import:0204V")
      (libsource (lib "eagle-import") (part "R-US_0204/2V"))
    )
    (comp (ref "R202")
      (value "1K")
      (footprint "eagle-import:0204V")
      (libsource (lib "eagle-import") (part "R-US_0204/2V"))
    )
    (comp (ref "R203")
      (value "1K")
      (footprint "eagle-import:0204V")
      (libsource (lib "eagle-import") (part "R-US_0204/2V"))
    )
    (comp (ref "R204")
      (value "1K")
      (footprint "eagle-import:0204V")
      (libsource (lib "eagle-import") (part "R-US_0204/2V"))
    )
    (comp (ref "R205")
      (value "1K")
      (footprint "eagle-import:0204V")
      (libsource (lib "eagle-import") (part "R-US_0204/2V"))
    )
    (comp (ref "R206")
      (value "1K")
      (footprint "eagle-import:0204V")
      (libsource (lib "eagle-import") (part "R-US_0204/2V"))
    )
    (comp (ref "R207")
      (value "1K")
      (footprint "eagle-import:0204V")
      (libsource (lib "eagle-import") (part "R-US_0204/2V"))
    )
    (comp (ref "RN1")
      (value "4K7")
      (footprint "eagle-import:RN-6")
      (libsource (lib "eagle-import") (part "RN05"))
    )
    (comp (ref "S1")
      (value "ROMSEL")
      (footprint "eagle-import:DS-02")
      (libsource (lib "eagle-import") (part "DS02"))
    )
    (comp (ref "S2")
      (value "RESET")
      (footprint "eagle-import:B3F-31XX")
      (fields (field (name "MPN") "B3F-3100"))
      (libsource (lib "eagle-import") (part "31-XX"))
    )
    (comp (ref "SJ1")
      (value "NO OPAMP")
      (footprint "eagle-import:SJ")
      (libsource (lib "eagle-import") (part "SJ"))
    )
    (comp (ref "SJ2") (value "SJ") (footprint "eagle-import:SJ") (libsource (lib "eagle-import") (part "SJ")))
    (comp (ref "SJ3") (value "SJ") (footprint "eagle-import:SJ") (libsource (lib "eagle-import") (part "SJ")))
    (comp (ref "SJ4") (value "SJ") (footprint "eagle-import:SJ") (libsource (lib "eagle-import") (part "SJ")))
    (comp (ref "SJ5") (value "SJ") (footprint "eagle-import:SJ") (libsource (lib "eagle-import") (part "SJ")))
    (comp (ref "SJ6") (value "SJ") (footprint "eagle-import:SJ") (libsource (lib "eagle-import") (part "SJ")))
    (comp (ref "SJ7") (value "SJ") (footprint "eagle-import:SJ") (libsource (lib "eagle-import") (part "SJ")))
    (comp (ref "SJ8") (value "SJ") (footprint "eagle-import:SJ") (libsource (lib "eagle-import") (part "SJ")))
    (comp (ref "SJ9") (value "SJ") (footprint "eagle-import:SJ") (libsource (lib "eagle-import") (part "SJ")))
    (comp (ref "U$1")
      (value "40-XX-CARBON")
      (footprint "eagle-import:CARBONB3F")
      (libsource (lib "eagle-import") (part "40-XX-CARBON"))
    )
    (comp (ref "U$2")
      (value "40-XX-CARBON")
      (footprint "eagle-import:CARBONB3F")
      (libsource (lib "eagle-import") (part "40-XX-CARBON"))
    )
    (comp (ref "U$3")
      (value "40-XX-CARBON")
      (footprint "eagle-import:CARBONB3F")
      (libsource (lib "eagle-import") (part "40-XX-CARBON"))
    )
    (comp (ref "U$4")
      (value "40-XX-CARBON")
      (footprint "eagle-import:CARBONB3F")
      (libsource (lib "eagle-import") (part "40-XX-CARBON"))
    )
    (comp (ref "U$5")
      (value "40-XX-CARBON")
      (footprint "eagle-import:CARBONB3F")
      (libsource (lib "eagle-import") (part "40-XX-CARBON"))
    )
    (comp (ref "U$6")
      (value "40-XX-CARBON")
      (footprint "eagle-import:CARBONB3F")
      (libsource (lib "eagle-import") (part "40-XX-CARBON"))
    )
    (comp (ref "U$7")
      (value "40-XX-CARBON")
      (footprint "eagle-import:CARBONB3F")
      (libsource (lib "eagle-import") (part "40-XX-CARBON"))
    )
    (comp (ref "U$8")
      (value "40-XX-CARBON")
      (footprint "eagle-import:CARBONB3F")
      (libsource (lib "eagle-import") (part "40-XX-CARBON"))
    )
    (comp (ref "U$9")
      (value "40-XX-CARBON")
      (footprint "eagle-import:CARBONB3F")
      (libsource (lib "eagle-import") (part "40-XX-CARBON"))
    )
    (comp (ref "U$10")
      (value "40-XX-CARBON")
      (footprint "eagle-import:CARBONB3F")
      (libsource (lib "eagle-import") (part "40-XX-CARBON"))
    )
    (comp (ref "U$11")
      (value "40-XX-CARBON")
      (footprint "eagle-import:CARBONB3F")
      (libsource (lib "eagle-import") (part "40-XX-CARBON"))
    )
    (comp (ref "U$12")
      (value "40-XX-CARBON")
      (footprint "eagle-import:CARBONB3F")
      (libsource (lib "eagle-import") (part "40-XX-CARBON"))
    )
    (comp (ref "U$13")
      (value "40-XX-CARBON")
      (footprint "eagle-import:CARBONB3F")
      (libsource (lib "eagle-import") (part "40-XX-CARBON"))
    )
    (comp (ref "U$14")
      (value "40-XX-CARBON")
      (footprint "eagle-import:CARBONB3F")
      (libsource (lib "eagle-import") (part "40-XX-CARBON"))
    )
    (comp (ref "U$15")
      (value "40-XX-CARBON")
      (footprint "eagle-import:CARBONB3F")
      (libsource (lib "eagle-import") (part "40-XX-CARBON"))
    )
    (comp (ref "U$16")
      (value "40-XX-CARBON")
      (footprint "eagle-import:CARBONB3F")
      (libsource (lib "eagle-import") (part "40-XX-CARBON"))
    )
    (comp (ref "U$17")
      (value "40-XX-CARBON")
      (footprint "eagle-import:CARBONB3F")
      (libsource (lib "eagle-import") (part "40-XX-CARBON"))
    )
    (comp (ref "U$18")
      (value "40-XX-CARBON")
      (footprint "eagle-import:CARBONB3F")
      (libsource (lib "eagle-import") (part "40-XX-CARBON"))
    )
    (comp (ref "U$19")
      (value "40-XX-CARBON")
      (footprint "eagle-import:CARBONB3F")
      (libsource (lib "eagle-import") (part "40-XX-CARBON"))
    )
    (comp (ref "U$20")
      (value "40-XX-CARBON")
      (footprint "eagle-import:CARBONB3F")
      (libsource (lib "eagle-import") (part "40-XX-CARBON"))
    )
    (comp (ref "U$21")
      (value "40-XX-CARBON")
      (footprint "eagle-import:CARBONB3F")
      (libsource (lib "eagle-import") (part "40-XX-CARBON"))
    )
    (comp (ref "U$22")
      (value "40-XX-CARBON")
      (footprint "eagle-import:CARBONB3F")
      (libsource (lib "eagle-import") (part "40-XX-CARBON"))
    )
    (comp (ref "U$23")
      (value "40-XX-CARBON")
      (footprint "eagle-import:CARBONB3F")
      (libsource (lib "eagle-import") (part "40-XX-CARBON"))
    )
    (comp (ref "U$24")
      (value "40-XX-CARBON")
      (footprint "eagle-import:CARBONB3F")
      (libsource (lib "eagle-import") (part "40-XX-CARBON"))
    )
    (comp (ref "U$25")
      (value "40-XX-CARBON")
      (footprint "eagle-import:CARBONB3F")
      (libsource (lib "eagle-import") (part "40-XX-CARBON"))
    )
    (comp (ref "U$26")
      (value "40-XX-CARBON")
      (footprint "eagle-import:CARBONB3F")
      (libsource (lib "eagle-import") (part "40-XX-CARBON"))
    )
    (comp (ref "U$27")
      (value "40-XX-CARBON")
      (footprint "eagle-import:CARBONB3F")
      (libsource (lib "eagle-import") (part "40-XX-CARBON"))
    )
    (comp (ref "U$28")
      (value "40-XX-CARBON")
      (footprint "eagle-import:CARBONB3F")
      (libsource (lib "eagle-import") (part "40-XX-CARBON"))
    )
    (comp (ref "U$29")
      (value "40-XX-CARBON")
      (footprint "eagle-import:CARBONB3F")
      (libsource (lib "eagle-import") (part "40-XX-CARBON"))
    )
    (comp (ref "U$30")
      (value "40-XX-CARBON")
      (footprint "eagle-import:CARBONB3F")
      (libsource (lib "eagle-import") (part "40-XX-CARBON"))
    )
    (comp (ref "U$31")
      (value "40-XX-CARBON")
      (footprint "eagle-import:CARBONB3F")
      (libsource (lib "eagle-import") (part "40-XX-CARBON"))
    )
    (comp (ref "U$32")
      (value "40-XX-CARBON")
      (footprint "eagle-import:CARBONB3F")
      (libsource (lib "eagle-import") (part "40-XX-CARBON"))
    )
    (comp (ref "U$33")
      (value "40-XX-CARBON")
      (footprint "eagle-import:CARBONB3F")
      (libsource (lib "eagle-import") (part "40-XX-CARBON"))
    )
    (comp (ref "U$34")
      (value "40-XX-CARBON")
      (footprint "eagle-import:CARBONB3F")
      (libsource (lib "eagle-import") (part "40-XX-CARBON"))
    )
    (comp (ref "U$35")
      (value "40-XX-CARBON")
      (footprint "eagle-import:CARBONB3F")
      (libsource (lib "eagle-import") (part "40-XX-CARBON"))
    )
    (comp (ref "U$36")
      (value "40-XX-CARBON")
      (footprint "eagle-import:CARBONB3F")
      (libsource (lib "eagle-import") (part "40-XX-CARBON"))
    )
    (comp (ref "U$37")
      (value "40-XX-CARBON")
      (footprint "eagle-import:CARBONB3F")
      (libsource (lib "eagle-import") (part "40-XX-CARBON"))
    )
    (comp (ref "U$38")
      (value "40-XX-CARBON")
      (footprint "eagle-import:CARBONB3F")
      (libsource (lib "eagle-import") (part "40-XX-CARBON"))
    )
    (comp (ref "U$39")
      (value "40-XX-CARBON")
      (footprint "eagle-import:CARBONB3F")
      (libsource (lib "eagle-import") (part "40-XX-CARBON"))
    )
    (comp (ref "U$40")
      (value "40-XX-CARBON")
      (footprint "eagle-import:CARBONB3F")
      (libsource (lib "eagle-import") (part "40-XX-CARBON"))
    )
    (comp (ref "U$41")
      (value "40-XX-CARBON")
      (footprint "eagle-import:CARBONB3F")
      (libsource (lib "eagle-import") (part "40-XX-CARBON"))
    )
    (comp (ref "U$42")
      (value "40-XX-CARBON")
      (footprint "eagle-import:CARBONB3F")
      (libsource (lib "eagle-import") (part "40-XX-CARBON"))
    )
    (comp (ref "U1")
      (value "7805")
      (footprint "eagle-import:TO220V")
      (libsource (lib "eagle-import") (part "78TV05"))
    )
    (comp (ref "U2")
      (value "MAX4390EUK")
      (footprint "eagle-import:SOT95P280X145-5N")
      (fields (field (name "MF") "Maxim Integrated") (field (name "MP") "MAX4390EUK+T"))
      (libsource (lib "eagle-import") (part "MAX4390EUK"))
    )
    (comp (ref "X1")
      (value "6.5MHz")
      (footprint "eagle-import:HC49U")
      (libsource (lib "eagle-import") (part "8M10AHC49T"))
    )
    (comp (ref "X2")
      (value "CON-CONRAD_736880-49")
      (footprint "eagle-import:CON-CONRAD_736880-49")
      (libsource (lib "eagle-import") (part "CON-CONRAD_736880-49"))
    )
    (comp (ref "Z0")
      (value "Z80")
      (footprint "eagle-import:DIL40")
      (libsource (lib "eagle-import") (part "Z80CPU"))
    )
    (comp (ref "Z1")
      (value "74LS74N")
      (footprint "eagle-import:DIL14")
      (libsource (lib "eagle-import") (part "7474NLS"))
    )
    (comp (ref "Z1-2")
      (value "27C512")
      (footprint "eagle-import:DIL28-6")
      (libsource (lib "eagle-import") (part "27512G"))
    )
    (comp (ref "Z3-4")
      (value "CY62256LL-PC")
      (footprint "eagle-import:DIL28-6")
      (libsource (lib "eagle-import") (part "CY62256LL-?PC"))
    )
    (comp (ref "Z5-6")
      (value "CY62256LL-PC")
      (footprint "eagle-import:DIL28-6")
      (libsource (lib "eagle-import") (part "CY62256LL-?PC"))
    )
    (comp (ref "Z7-8")
      (value "CY62256LL-PC")
      (footprint "eagle-import:DIL28-6")
      (libsource (lib "eagle-import") (part "CY62256LL-?PC"))
    )
    (comp (ref "Z9")
      (value "74LS393N")
      (footprint "eagle-import:DIL14")
      (libsource (lib "eagle-import") (part "74393NLS"))
    )
    (comp (ref "Z10")
      (value "74LS393N")
      (footprint "eagle-import:DIL14")
      (libsource (lib "eagle-import") (part "74393NLS"))
    )
    (comp (ref "Z11")
      (value "74LS393N")
      (footprint "eagle-import:DIL14")
      (libsource (lib "eagle-import") (part "74393NLS"))
    )
    (comp (ref "Z14")
      (value "74367N")
      (footprint "eagle-import:DIL16")
      (libsource (lib "eagle-import") (part "74367N"))
    )
    (comp (ref "Z15")
      (value "74367N")
      (footprint "eagle-import:DIL16")
      (libsource (lib "eagle-import") (part "74367N"))
    )
    (comp (ref "Z16")
      (value "74367N")
      (footprint "eagle-import:DIL16")
      (libsource (lib "eagle-import") (part "74367N"))
    )
    (comp (ref "Z17")
      (value "74367N")
      (footprint "eagle-import:DIL16")
      (libsource (lib "eagle-import") (part "74367N"))
    )
    (comp (ref "Z18")
      (value "74367N")
      (footprint "eagle-import:DIL16")
      (libsource (lib "eagle-import") (part "74367N"))
    )
    (comp (ref "Z19")
      (value "74LS00N")
      (footprint "eagle-import:DIL14")
      (libsource (lib "eagle-import") (part "7400NLS"))
    )
    (comp (ref "Z20")
      (value "74LS08N")
      (footprint "eagle-import:DIL14")
      (libsource (lib "eagle-import") (part "7408NLS"))
    )
    (comp (ref "Z21")
      (value "74LS11N")
      (footprint "eagle-import:DIL14")
      (libsource (lib "eagle-import") (part "7411NLS"))
    )
    (comp (ref "Z22")
      (value "74LS11N")
      (footprint "eagle-import:DIL14")
      (libsource (lib "eagle-import") (part "7411NLS"))
    )
    (comp (ref "Z23")
      (value "74LS86N")
      (footprint "eagle-import:DIL14")
      (libsource (lib "eagle-import") (part "7486NLS"))
    )
    (comp (ref "Z24")
      (value "74LS02N")
      (footprint "eagle-import:DIL14")
      (libsource (lib "eagle-import") (part "7402NLS"))
    )
    (comp (ref "Z25")
      (value "74LS02N")
      (footprint "eagle-import:DIL14")
      (libsource (lib "eagle-import") (part "7402NLS"))
    )
    (comp (ref "Z26")
      (value "74LS32N")
      (footprint "eagle-import:DIL14")
      (libsource (lib "eagle-import") (part "7432NLS"))
    )
    (comp (ref "Z27")
      (value "74LS74N")
      (footprint "eagle-import:DIL14")
      (libsource (lib "eagle-import") (part "7474NLS"))
    )
    (comp (ref "Z28")
      (value "74LS166N")
      (footprint "eagle-import:DIL16")
      (libsource (lib "eagle-import") (part "74166NLS"))
    )
    (comp (ref "Z29")
      (value "74LS138N")
      (footprint "eagle-import:DIL16")
      (libsource (lib "eagle-import") (part "74138NLS"))
    )
    (comp (ref "Z30")
      (value "74LS00N")
      (footprint "eagle-import:DIL14")
      (libsource (lib "eagle-import") (part "7400NLS"))
    )
    (comp (ref "Z31")
      (value "74LS11N")
      (footprint "eagle-import:DIL14")
      (libsource (lib "eagle-import") (part "7411NLS"))
    )
    (comp (ref "Z40")
      (value "ATF16V8BP3")
      (footprint "eagle-import:DIL20")
      (fields (field (name "MPN") "ATF16V8CZ-15PU"))
      (libsource (lib "eagle-import") (part "ATF16V8BP3"))
    )
    (comp (ref "Z41")
      (value "74LS00N")
      (footprint "eagle-import:DIL14")
      (libsource (lib "eagle-import") (part "7400NLS"))
    )
  )
  (nets
    (net (code "3") (name "/9V") (class "Default")
      (node (ref "3A") (pin "1") (pinfunction "P_1") (pintype "passive"))
      (node (ref "C10") (pin "1") (pinfunction "1_1") (pintype "passive"))
      (node (ref "C11") (pin "+") (pinfunction "+_+") (pintype "passive"))
      (node (ref "C9") (pin "+") (pinfunction "+_+") (pintype "passive"))
      (node (ref "JP7") (pin "1") (pinfunction "1_1") (pintype "passive"))
      (node (ref "U1") (pin "1") (pinfunction "VI_1") (pintype "input"))
    )
    (net (code "4") (name "/A0") (class "Default")
      (node (ref "19A") (pin "1") (pinfunction "P_1") (pintype "passive"))
      (node (ref "Z0") (pin "30") (pinfunction "A0_30") (pintype "output"))
      (node (ref "Z1-2") (pin "10") (pinfunction "A0_10") (pintype "input"))
      (node (ref "Z15") (pin "2") (pinfunction "1A1_2") (pintype "input"))
      (node (ref "Z18") (pin "10") (pinfunction "1A4_10") (pintype "input"))
      (node (ref "Z26") (pin "5") (pinfunction "I1_5") (pintype "input"))
      (node (ref "Z3-4") (pin "21") (pinfunction "A0_21") (pintype "input"))
    )
    (net (code "5") (name "/A1") (class "Default")
      (node (ref "19B") (pin "1") (pinfunction "P_1") (pintype "passive"))
      (node (ref "Z0") (pin "31") (pinfunction "A1_31") (pintype "output"))
      (node (ref "Z1-2") (pin "9") (pinfunction "A1_9") (pintype "input"))
      (node (ref "Z15") (pin "4") (pinfunction "1A2_4") (pintype "input"))
      (node (ref "Z18") (pin "6") (pinfunction "1A3_6") (pintype "input"))
      (node (ref "Z3-4") (pin "23") (pinfunction "A1_23") (pintype "input"))
    )
    (net (code "6") (name "/A2") (class "Default")
      (node (ref "14A") (pin "1") (pinfunction "P_1") (pintype "passive"))
      (node (ref "Z0") (pin "32") (pinfunction "A2_32") (pintype "output"))
      (node (ref "Z1-2") (pin "8") (pinfunction "A2_8") (pintype "input"))
      (node (ref "Z15") (pin "6") (pinfunction "1A3_6") (pintype "input"))
      (node (ref "Z18") (pin "4") (pinfunction "1A2_4") (pintype "input"))
      (node (ref "Z3-4") (pin "24") (pinfunction "A2_24") (pintype "input"))
    )
    (net (code "7") (name "/A3") (class "Default")
      (node (ref "18B") (pin "1") (pinfunction "P_1") (pintype "passive"))
      (node (ref "Z0") (pin "33") (pinfunction "A3_33") (pintype "output"))
      (node (ref "Z1-2") (pin "7") (pinfunction "A3_7") (pintype "input"))
      (node (ref "Z15") (pin "10") (pinfunction "1A4_10") (pintype "input"))
      (node (ref "Z18") (pin "2") (pinfunction "1A1_2") (pintype "input"))
      (node (ref "Z3-4") (pin "25") (pinfunction "A3_25") (pintype "input"))
    )
    (net (code "8") (name "/A4") (class "Default")
      (node (ref "17B") (pin "1") (pinfunction "P_1") (pintype "passive"))
      (node (ref "Z0") (pin "34") (pinfunction "A4_34") (pintype "output"))
      (node (ref "Z1-2") (pin "6") (pinfunction "A4_6") (pintype "input"))
      (node (ref "Z15") (pin "12") (pinfunction "2A1_12") (pintype "input"))
      (node (ref "Z17") (pin "14") (pinfunction "2A2_14") (pintype "input"))
      (node (ref "Z3-4") (pin "26") (pinfunction "A4_26") (pintype "input"))
    )
    (net (code "9") (name "/A5") (class "Default")
      (node (ref "16B") (pin "1") (pinfunction "P_1") (pintype "passive"))
      (node (ref "Z0") (pin "35") (pinfunction "A5_35") (pintype "output"))
      (node (ref "Z1-2") (pin "5") (pinfunction "A5_5") (pintype "input"))
      (node (ref "Z15") (pin "14") (pinfunction "2A2_14") (pintype "input"))
      (node (ref "Z17") (pin "12") (pinfunction "2A1_12") (pintype "input"))
      (node (ref "Z3-4") (pin "1") (pinfunction "A5_1") (pintype "input"))
    )
    (net (code "10") (name "/A6") (class "Default")
      (node (ref "15B") (pin "1") (pinfunction "P_1") (pintype "passive"))
      (node (ref "Z0") (pin "36") (pinfunction "A6_36") (pintype "output"))
      (node (ref "Z1-2") (pin "4") (pinfunction "A6_4") (pintype "input"))
      (node (ref "Z16") (pin "2") (pinfunction "1A1_2") (pintype "input"))
      (node (ref "Z17") (pin "10") (pinfunction "1A4_10") (pintype "input"))
      (node (ref "Z3-4") (pin "2") (pinfunction "A6_2") (pintype "input"))
    )
    (net (code "11") (name "/A7") (class "Default")
      (node (ref "18A") (pin "1") (pinfunction "P_1") (pintype "passive"))
      (node (ref "Z0") (pin "37") (pinfunction "A7_37") (pintype "output"))
      (node (ref "Z1-2") (pin "3") (pinfunction "A7_3") (pintype "input"))
      (node (ref "Z16") (pin "4") (pinfunction "1A2_4") (pintype "input"))
      (node (ref "Z17") (pin "6") (pinfunction "1A3_6") (pintype "input"))
      (node (ref "Z3-4") (pin "3") (pinfunction "A7_3") (pintype "input"))
    )
    (net (code "12") (name "/A8") (class "Default")
      (node (ref "17A") (pin "1") (pinfunction "P_1") (pintype "passive"))
      (node (ref "D10") (pin "C") (pinfunction "C_C") (pintype "passive"))
      (node (ref "Z0") (pin "38") (pinfunction "A8_38") (pintype "output"))
      (node (ref "Z1-2") (pin "25") (pinfunction "A8_25") (pintype "input"))
      (node (ref "Z16") (pin "6") (pinfunction "1A3_6") (pintype "input"))
      (node (ref "Z17") (pin "4") (pinfunction "1A2_4") (pintype "input"))
      (node (ref "Z3-4") (pin "4") (pinfunction "A8_4") (pintype "input"))
    )
    (net (code "13") (name "/A9") (class "Default")
      (node (ref "16A") (pin "1") (pinfunction "P_1") (pintype "passive"))
      (node (ref "D9") (pin "C") (pinfunction "C_C") (pintype "passive"))
      (node (ref "Z0") (pin "39") (pinfunction "A9_39") (pintype "output"))
      (node (ref "Z1-2") (pin "24") (pinfunction "A9_24") (pintype "input"))
      (node (ref "Z16") (pin "10") (pinfunction "1A4_10") (pintype "input"))
      (node (ref "Z17") (pin "2") (pinfunction "1A1_2") (pintype "input"))
      (node (ref "Z3-4") (pin "5") (pinfunction "A9_5") (pintype "input"))
    )
    (net (code "14") (name "/A10") (class "Default")
      (node (ref "15A") (pin "1") (pinfunction "P_1") (pintype "passive"))
      (node (ref "D8") (pin "C") (pinfunction "C_C") (pintype "passive"))
      (node (ref "Z0") (pin "40") (pinfunction "A10_40") (pintype "output"))
      (node (ref "Z1-2") (pin "21") (pinfunction "A10_21") (pintype "input"))
      (node (ref "Z19") (pin "9") (pinfunction "I0_9") (pintype "input"))
      (node (ref "Z30") (pin "9") (pinfunction "I0_9") (pintype "input"))
    )
    (net (code "15") (name "/A10'") (class "Default")
      (node (ref "Z3-4") (pin "6") (pinfunction "A10_6") (pintype "input"))
      (node (ref "Z30") (pin "8") (pinfunction "O_8") (pintype "output"))
    )
    (net (code "16") (name "/A11") (class "Default")
      (node (ref "6A") (pin "1") (pinfunction "P_1") (pintype "passive"))
      (node (ref "D7") (pin "C") (pinfunction "C_C") (pintype "passive"))
      (node (ref "Z0") (pin "1") (pinfunction "A11_1") (pintype "output"))
      (node (ref "Z1-2") (pin "23") (pinfunction "A11_23") (pintype "input"))
      (node (ref "Z24") (pin "6") (pinfunction "I1_6") (pintype "input"))
      (node (ref "Z30") (pin "12") (pinfunction "I0_12") (pintype "input"))
    )
    (net (code "17") (name "/A11'") (class "Default")
      (node (ref "Z3-4") (pin "7") (pinfunction "A11_7") (pintype "input"))
      (node (ref "Z30") (pin "11") (pinfunction "O_11") (pintype "output"))
    )
    (net (code "18") (name "/A12") (class "Default")
      (node (ref "7A") (pin "1") (pinfunction "P_1") (pintype "passive"))
      (node (ref "D6") (pin "C") (pinfunction "C_C") (pintype "passive"))
      (node (ref "Z0") (pin "2") (pinfunction "A12_2") (pintype "output"))
      (node (ref "Z1-2") (pin "2") (pinfunction "A12_2") (pintype "input"))
      (node (ref "Z29") (pin "1") (pinfunction "A_1") (pintype "input"))
      (node (ref "Z3-4") (pin "8") (pinfunction "A12_8") (pintype "input"))
    )
    (net (code "19") (name "/A13") (class "Default")
      (node (ref "8A") (pin "1") (pinfunction "P_1") (pintype "passive"))
      (node (ref "D5") (pin "C") (pinfunction "C_C") (pintype "passive"))
      (node (ref "Z0") (pin "3") (pinfunction "A13_3") (pintype "output"))
      (node (ref "Z29") (pin "2") (pinfunction "B_2") (pintype "input"))
      (node (ref "Z3-4") (pin "9") (pinfunction "A13_9") (pintype "input"))
    )
    (net (code "20") (name "/A14") (class "Default")
      (node (ref "9A") (pin "1") (pinfunction "P_1") (pintype "passive"))
      (node (ref "D4") (pin "C") (pinfunction "C_C") (pintype "passive"))
      (node (ref "Z0") (pin "4") (pinfunction "A14_4") (pintype "output"))
      (node (ref "Z29") (pin "3") (pinfunction "C_3") (pintype "input"))
      (node (ref "Z3-4") (pin "10") (pinfunction "A14_10") (pintype "input"))
      (node (ref "Z30") (pin "10") (pinfunction "I1_10") (pintype "input"))
      (node (ref "Z30") (pin "13") (pinfunction "I1_13") (pintype "input"))
    )
    (net (code "21") (name "/A15") (class "Default")
      (node (ref "10A") (pin "1") (pinfunction "P_1") (pintype "passive"))
      (node (ref "D3") (pin "C") (pinfunction "C_C") (pintype "passive"))
      (node (ref "Z0") (pin "5") (pinfunction "A15_5") (pintype "output"))
      (node (ref "Z29") (pin "5") (pinfunction "G2B_5") (pintype "input"))
    )
    (net (code "22") (name "/ACE81_ENABLED") (class "Default")
      (node (ref "JP9") (pin "3") (pinfunction "3_3") (pintype "passive"))
      (node (ref "R29") (pin "2") (pinfunction "2_2") (pintype "passive"))
      (node (ref "R42") (pin "2") (pinfunction "2_2") (pintype "passive"))
      (node (ref "Z1-2") (pin "1") (pinfunction "A15_1") (pintype "input"))
    )
    (net (code "23") (name "/CLK") (class "Default")
      (node (ref "C22") (pin "2") (pinfunction "2_2") (pintype "passive"))
      (node (ref "Z20") (pin "10") (pinfunction "I1_10") (pintype "input"))
      (node (ref "Z23") (pin "8") (pinfunction "O_8") (pintype "output"))
      (node (ref "Z28") (pin "7") (pinfunction "CLK_7") (pintype "input"))
      (node (ref "Z9") (pin "1") (pinfunction "A_1") (pintype "input"))
    )
    (net (code "24") (name "/CNT0") (class "Default")
      (node (ref "Z22") (pin "5") (pinfunction "I2_5") (pintype "input"))
      (node (ref "Z30") (pin "4") (pinfunction "I0_4") (pintype "input"))
      (node (ref "Z30") (pin "5") (pinfunction "I1_5") (pintype "input"))
      (node (ref "Z9") (pin "3") (pinfunction "QA_3") (pintype "output"))
    )
    (net (code "25") (name "/CNT1") (class "Default")
      (node (ref "Z22") (pin "4") (pinfunction "I1_4") (pintype "input"))
      (node (ref "Z9") (pin "4") (pinfunction "QB_4") (pintype "output"))
    )
    (net (code "26") (name "/CNT2") (class "Default")
      (node (ref "Z22") (pin "3") (pinfunction "I0_3") (pintype "input"))
      (node (ref "Z41") (pin "5") (pinfunction "I1_5") (pintype "input"))
      (node (ref "Z9") (pin "5") (pinfunction "QC_5") (pintype "output"))
    )
    (net (code "27") (name "/CNT3") (class "Default")
      (node (ref "JP5") (pin "1") (pinfunction "1_1") (pintype "passive"))
      (node (ref "Z9") (pin "13") (pinfunction "A_13") (pintype "input"))
      (node (ref "Z9") (pin "6") (pinfunction "QD_6") (pintype "output"))
    )
    (net (code "28") (name "/CNT4") (class "Default")
      (node (ref "JP10") (pin "1") (pinfunction "1_1") (pintype "passive"))
      (node (ref "Z10") (pin "1") (pinfunction "A_1") (pintype "input"))
      (node (ref "Z9") (pin "11") (pinfunction "QA_11") (pintype "output"))
    )
    (net (code "29") (name "/CNT5") (class "Default")
      (node (ref "JP10") (pin "3") (pinfunction "1_3") (pintype "passive"))
      (node (ref "Z10") (pin "3") (pinfunction "QA_3") (pintype "output"))
      (node (ref "Z21") (pin "11") (pinfunction "I2_11") (pintype "input"))
      (node (ref "Z25") (pin "11") (pinfunction "I0_11") (pintype "input"))
      (node (ref "Z41") (pin "2") (pinfunction "I1_2") (pintype "input"))
    )
    (net (code "30") (name "/CNT6") (class "Default")
      (node (ref "JP10") (pin "5") (pinfunction "1_5") (pintype "passive"))
      (node (ref "Z10") (pin "4") (pinfunction "QB_4") (pintype "output"))
      (node (ref "Z22") (pin "1") (pinfunction "I0_1") (pintype "input"))
    )
    (net (code "31") (name "/CNT7") (class "Default")
      (node (ref "JP10") (pin "7") (pinfunction "1_7") (pintype "passive"))
      (node (ref "Z10") (pin "5") (pinfunction "QC_5") (pintype "output"))
      (node (ref "Z21") (pin "10") (pinfunction "I1_10") (pintype "input"))
      (node (ref "Z25") (pin "12") (pinfunction "I1_12") (pintype "input"))
    )
    (net (code "32") (name "/CNT8") (class "Default")
      (node (ref "Z10") (pin "13") (pinfunction "A_13") (pintype "input"))
      (node (ref "Z10") (pin "6") (pinfunction "QD_6") (pintype "output"))
      (node (ref "Z21") (pin "9") (pinfunction "I0_9") (pintype "input"))
      (node (ref "Z22") (pin "13") (pinfunction "I2_13") (pintype "input"))
      (node (ref "Z25") (pin "2") (pinfunction "I0_2") (pintype "input"))
    )
    (net (code "33") (name "/CNT9") (class "Default")
      (node (ref "R21") (pin "1") (pinfunction "1_1") (pintype "passive"))
      (node (ref "Z10") (pin "11") (pinfunction "QA_11") (pintype "output"))
    )
    (net (code "34") (name "/CNT10") (class "Default")
      (node (ref "R22") (pin "1") (pinfunction "1_1") (pintype "passive"))
      (node (ref "Z10") (pin "10") (pinfunction "QB_10") (pintype "output"))
    )
    (net (code "35") (name "/CNT11") (class "Default")
      (node (ref "R23") (pin "1") (pinfunction "1_1") (pintype "passive"))
      (node (ref "Z10") (pin "9") (pinfunction "QC_9") (pintype "output"))
      (node (ref "Z11") (pin "1") (pinfunction "A_1") (pintype "input"))
    )
    (net (code "36") (name "/CNT12") (class "Default")
      (node (ref "JP15") (pin "1") (pinfunction "1_1") (pintype "passive"))
      (node (ref "Z11") (pin "3") (pinfunction "QA_3") (pintype "output"))
      (node (ref "Z21") (pin "3") (pinfunction "I0_3") (pintype "input"))
    )
    (net (code "37") (name "/CNT13") (class "Default")
      (node (ref "JP15") (pin "3") (pinfunction "1_3") (pintype "passive"))
      (node (ref "Z11") (pin "4") (pinfunction "QB_4") (pintype "output"))
      (node (ref "Z21") (pin "4") (pinfunction "I1_4") (pintype "input"))
    )
    (net (code "38") (name "/CNT14") (class "Default")
      (node (ref "JP15") (pin "5") (pinfunction "1_5") (pintype "passive"))
      (node (ref "Z11") (pin "5") (pinfunction "QC_5") (pintype "output"))
      (node (ref "Z21") (pin "5") (pinfunction "I2_5") (pintype "input"))
    )
    (net (code "39") (name "/CNT15") (class "Default")
      (node (ref "JP15") (pin "7") (pinfunction "1_7") (pintype "passive"))
      (node (ref "Z11") (pin "13") (pinfunction "A_13") (pintype "input"))
      (node (ref "Z11") (pin "6") (pinfunction "QD_6") (pintype "output"))
      (node (ref "Z19") (pin "1") (pinfunction "I0_1") (pintype "input"))
      (node (ref "Z21") (pin "1") (pinfunction "I0_1") (pintype "input"))
    )
    (net (code "40") (name "/CNT16") (class "Default")
      (node (ref "JP15") (pin "9") (pinfunction "1_9") (pintype "passive"))
      (node (ref "Z11") (pin "11") (pinfunction "QA_11") (pintype "output"))
      (node (ref "Z19") (pin "2") (pinfunction "I1_2") (pintype "input"))
      (node (ref "Z21") (pin "2") (pinfunction "I1_2") (pintype "input"))
    )
    (net (code "41") (name "/CNT17") (class "Default")
      (node (ref "Z11") (pin "10") (pinfunction "QB_10") (pintype "output"))
      (node (ref "Z20") (pin "2") (pinfunction "I1_2") (pintype "input"))
      (node (ref "Z25") (pin "3") (pinfunction "I1_3") (pintype "input"))
    )
    (net (code "42") (name "/D0") (class "Default")
      (node (ref "20B") (pin "1") (pinfunction "P_1") (pintype "passive"))
      (node (ref "R100") (pin "1") (pinfunction "1_1") (pintype "passive"))
      (node (ref "R200") (pin "1") (pinfunction "1_1") (pintype "passive"))
      (node (ref "Z0") (pin "14") (pinfunction "D0_14") (pintype "bidirectional"))
      (node (ref "Z1-2") (pin "11") (pinfunction "I/O0_11") (pintype "tri_state"))
      (node (ref "Z14") (pin "3") (pinfunction "1Y1_3") (pintype "tri_state"))
      (node (ref "Z3-4") (pin "11") (pinfunction "DQ0_11") (pintype "bidirectional"))
    )
    (net (code "43") (name "/D1") (class "Default")
      (node (ref "20A") (pin "1") (pinfunction "P_1") (pintype "passive"))
      (node (ref "R101") (pin "1") (pinfunction "1_1") (pintype "passive"))
      (node (ref "R201") (pin "1") (pinfunction "1_1") (pintype "passive"))
      (node (ref "Z0") (pin "15") (pinfunction "D1_15") (pintype "bidirectional"))
      (node (ref "Z1-2") (pin "12") (pinfunction "I/O1_12") (pintype "tri_state"))
      (node (ref "Z14") (pin "5") (pinfunction "1Y2_5") (pintype "tri_state"))
      (node (ref "Z3-4") (pin "12") (pinfunction "DQ1_12") (pintype "bidirectional"))
    )
    (net (code "44") (name "/D2") (class "Default")
      (node (ref "21B") (pin "1") (pinfunction "P_1") (pintype "passive"))
      (node (ref "R102") (pin "1") (pinfunction "1_1") (pintype "passive"))
      (node (ref "R202") (pin "1") (pinfunction "1_1") (pintype "passive"))
      (node (ref "Z0") (pin "12") (pinfunction "D2_12") (pintype "bidirectional"))
      (node (ref "Z1-2") (pin "13") (pinfunction "I/O2_13") (pintype "tri_state"))
      (node (ref "Z14") (pin "7") (pinfunction "1Y3_7") (pintype "tri_state"))
      (node (ref "Z3-4") (pin "13") (pinfunction "DQ2_13") (pintype "bidirectional"))
    )
    (net (code "45") (name "/D3") (class "Default")
      (node (ref "12A") (pin "1") (pinfunction "P_1") (pintype "passive"))
      (node (ref "R103") (pin "1") (pinfunction "1_1") (pintype "passive"))
      (node (ref "R203") (pin "1") (pinfunction "1_1") (pintype "passive"))
      (node (ref "Z0") (pin "8") (pinfunction "D3_8") (pintype "bidirectional"))
      (node (ref "Z1-2") (pin "15") (pinfunction "I/O3_15") (pintype "tri_state"))
      (node (ref "Z14") (pin "9") (pinfunction "1Y4_9") (pintype "tri_state"))
      (node (ref "Z27") (pin "2") (pinfunction "D_2") (pintype "input"))
      (node (ref "Z3-4") (pin "15") (pinfunction "DQ3_15") (pintype "bidirectional"))
    )
    (net (code "46") (name "/D4") (class "Default")
      (node (ref "11A") (pin "1") (pinfunction "P_1") (pintype "passive"))
      (node (ref "R104") (pin "1") (pinfunction "1_1") (pintype "passive"))
      (node (ref "R204") (pin "1") (pinfunction "1_1") (pintype "passive"))
      (node (ref "Z0") (pin "7") (pinfunction "D4_7") (pintype "bidirectional"))
      (node (ref "Z1-2") (pin "16") (pinfunction "I/O4_16") (pintype "tri_state"))
      (node (ref "Z14") (pin "11") (pinfunction "2Y1_11") (pintype "tri_state"))
      (node (ref "Z3-4") (pin "16") (pinfunction "DQ4_16") (pintype "bidirectional"))
    )
    (net (code "47") (name "/D5") (class "Default")
      (node (ref "13A") (pin "1") (pinfunction "P_1") (pintype "passive"))
      (node (ref "R105") (pin "1") (pinfunction "1_1") (pintype "passive"))
      (node (ref "R205") (pin "1") (pinfunction "1_1") (pintype "passive"))
      (node (ref "Z0") (pin "9") (pinfunction "D5_9") (pintype "bidirectional"))
      (node (ref "Z1-2") (pin "17") (pinfunction "I/O5_17") (pintype "tri_state"))
      (node (ref "Z14") (pin "13") (pinfunction "2Y2_13") (pintype "tri_state"))
      (node (ref "Z3-4") (pin "17") (pinfunction "DQ5_17") (pintype "bidirectional"))
    )
    (net (code "48") (name "/D6") (class "Default")
      (node (ref "21A") (pin "1") (pinfunction "P_1") (pintype "passive"))
      (node (ref "R106") (pin "1") (pinfunction "1_1") (pintype "passive"))
      (node (ref "R206") (pin "1") (pinfunction "1_1") (pintype "passive"))
      (node (ref "Z0") (pin "10") (pinfunction "D6_10") (pintype "bidirectional"))
      (node (ref "Z1-2") (pin "18") (pinfunction "I/O6_18") (pintype "tri_state"))
      (node (ref "Z3-4") (pin "18") (pinfunction "DQ6_18") (pintype "bidirectional"))
    )
    (net (code "49") (name "/D7") (class "Default")
      (node (ref "22B") (pin "1") (pinfunction "P_1") (pintype "passive"))
      (node (ref "R107") (pin "1") (pinfunction "1_1") (pintype "passive"))
      (node (ref "R207") (pin "1") (pinfunction "1_1") (pintype "passive"))
      (node (ref "Z0") (pin "13") (pinfunction "D7_13") (pintype "bidirectional"))
      (node (ref "Z1-2") (pin "19") (pinfunction "I/O7_19") (pintype "tri_state"))
      (node (ref "Z3-4") (pin "19") (pinfunction "DQ7_19") (pintype "bidirectional"))
    )
    (net (code "50") (name "/EAR") (class "Default")
      (node (ref "Z14") (pin "14") (pinfunction "2A2_14") (pintype "input"))
      (node (ref "Z18") (pin "13") (pinfunction "2Y2_13") (pintype "tri_state"))
    )
    (net (code "51") (name "/FIELD") (class "Default")
      (node (ref "Z19") (pin "12") (pinfunction "I0_12") (pintype "input"))
      (node (ref "Z21") (pin "12") (pinfunction "O_12") (pintype "output"))
      (node (ref "Z25") (pin "6") (pinfunction "I1_6") (pintype "input"))
    )
    (net (code "52") (name "/KB") (class "Default")
      (node (ref "K37") (pin "3") (pinfunction "P_3") (pintype "passive"))
      (node (ref "K37") (pin "4") (pinfunction "P1_4") (pintype "passive"))
      (node (ref "SJ4") (pin "1") (pinfunction "1_1") (pintype "passive"))
      (node (ref "SJ7") (pin "2") (pinfunction "2_2") (pintype "passive"))
      (node (ref "U$37") (pin "P$2") (pinfunction "2_P$2") (pintype "passive"))
      (node (ref "Z40") (pin "4") (pinfunction "I3_4") (pintype "input"))
    )
    (net (code "53") (name "/KC") (class "Default")
      (node (ref "K35") (pin "3") (pinfunction "P_3") (pintype "passive"))
      (node (ref "K35") (pin "4") (pinfunction "P1_4") (pintype "passive"))
      (node (ref "SJ5") (pin "1") (pinfunction "1_1") (pintype "passive"))
      (node (ref "U$35") (pin "P$2") (pinfunction "2_P$2") (pintype "passive"))
      (node (ref "Z40") (pin "5") (pinfunction "I4_5") (pintype "input"))
    )
    (net (code "54") (name "/KEYB1") (class "Default")
      (node (ref "K1") (pin "3") (pinfunction "P_3") (pintype "passive"))
      (node (ref "K1") (pin "4") (pinfunction "P1_4") (pintype "passive"))
      (node (ref "K10") (pin "3") (pinfunction "P_3") (pintype "passive"))
      (node (ref "K10") (pin "4") (pinfunction "P1_4") (pintype "passive"))
      (node (ref "K11") (pin "3") (pinfunction "P_3") (pintype "passive"))
      (node (ref "K11") (pin "4") (pinfunction "P1_4") (pintype "passive"))
      (node (ref "K20") (pin "3") (pinfunction "P_3") (pintype "passive"))
      (node (ref "K20") (pin "4") (pinfunction "P1_4") (pintype "passive"))
      (node (ref "K21") (pin "3") (pinfunction "P_3") (pintype "passive"))
      (node (ref "K21") (pin "4") (pinfunction "P1_4") (pintype "passive"))
      (node (ref "K30") (pin "3") (pinfunction "P_3") (pintype "passive"))
      (node (ref "K30") (pin "4") (pinfunction "P1_4") (pintype "passive"))
      (node (ref "K31") (pin "3") (pinfunction "P_3") (pintype "passive"))
      (node (ref "K31") (pin "4") (pinfunction "P1_4") (pintype "passive"))
      (node (ref "K40") (pin "3") (pinfunction "P_3") (pintype "passive"))
      (node (ref "K40") (pin "4") (pinfunction "P1_4") (pintype "passive"))
      (node (ref "K41") (pin "3") (pinfunction "P_3") (pintype "passive"))
      (node (ref "K41") (pin "4") (pinfunction "P1_4") (pintype "passive"))
      (node (ref "R36") (pin "1") (pinfunction "1_1") (pintype "passive"))
      (node (ref "RN1") (pin "6") (pinfunction "6_6") (pintype "passive"))
      (node (ref "U$1") (pin "P$2") (pinfunction "2_P$2") (pintype "passive"))
      (node (ref "U$10") (pin "P$2") (pinfunction "2_P$2") (pintype "passive"))
      (node (ref "U$11") (pin "P$2") (pinfunction "2_P$2") (pintype "passive"))
      (node (ref "U$20") (pin "P$2") (pinfunction "2_P$2") (pintype "passive"))
      (node (ref "U$21") (pin "P$2") (pinfunction "2_P$2") (pintype "passive"))
      (node (ref "U$30") (pin "P$2") (pinfunction "2_P$2") (pintype "passive"))
      (node (ref "U$31") (pin "P$2") (pinfunction "2_P$2") (pintype "passive"))
      (node (ref "U$40") (pin "P$2") (pinfunction "2_P$2") (pintype "passive"))
      (node (ref "U$41") (pin "P$2") (pinfunction "2_P$2") (pintype "passive"))
      (node (ref "U$42") (pin "P$2") (pinfunction "2_P$2") (pintype "passive"))
      (node (ref "Z14") (pin "2") (pinfunction "1A1_2") (pintype "input"))
    )
    (net (code "55") (name "/KEYB2") (class "Default")
      (node (ref "D14") (pin "A") (pinfunction "A_A") (pintype "passive"))
      (node (ref "K12") (pin "3") (pinfunction "P_3") (pintype "passive"))
      (node (ref "K12") (pin "4") (pinfunction "P1_4") (pintype "passive"))
      (node (ref "K19") (pin "3") (pinfunction "P_3") (pintype "passive"))
      (node (ref "K19") (pin "4") (pinfunction "P1_4") (pintype "passive"))
      (node (ref "K2") (pin "3") (pinfunction "P_3") (pintype "passive"))
      (node (ref "K2") (pin "4") (pinfunction "P1_4") (pintype "passive"))
      (node (ref "K22") (pin "3") (pinfunction "P_3") (pintype "passive"))
      (node (ref "K22") (pin "4") (pinfunction "P1_4") (pintype "passive"))
      (node (ref "K29") (pin "3") (pinfunction "P_3") (pintype "passive"))
      (node (ref "K29") (pin "4") (pinfunction "P1_4") (pintype "passive"))
      (node (ref "K32") (pin "3") (pinfunction "P_3") (pintype "passive"))
      (node (ref "K32") (pin "4") (pinfunction "P1_4") (pintype "passive"))
      (node (ref "K9") (pin "3") (pinfunction "P_3") (pintype "passive"))
      (node (ref "K9") (pin "4") (pinfunction "P1_4") (pintype "passive"))
      (node (ref "R37") (pin "1") (pinfunction "1_1") (pintype "passive"))
      (node (ref "RN1") (pin "5") (pinfunction "5_5") (pintype "passive"))
      (node (ref "U$12") (pin "P$2") (pinfunction "2_P$2") (pintype "passive"))
      (node (ref "U$19") (pin "P$2") (pinfunction "2_P$2") (pintype "passive"))
      (node (ref "U$2") (pin "P$2") (pinfunction "2_P$2") (pintype "passive"))
      (node (ref "U$22") (pin "P$2") (pinfunction "2_P$2") (pintype "passive"))
      (node (ref "U$29") (pin "P$2") (pinfunction "2_P$2") (pintype "passive"))
      (node (ref "U$32") (pin "P$2") (pinfunction "2_P$2") (pintype "passive"))
      (node (ref "U$9") (pin "P$2") (pinfunction "2_P$2") (pintype "passive"))
      (node (ref "Z14") (pin "4") (pinfunction "1A2_4") (pintype "input"))
    )
    (net (code "56") (name "/KEYB3") (class "Default")
      (node (ref "D15") (pin "A") (pinfunction "A_A") (pintype "passive"))
      (node (ref "K13") (pin "3") (pinfunction "P_3") (pintype "passive"))
      (node (ref "K13") (pin "4") (pinfunction "P1_4") (pintype "passive"))
      (node (ref "K18") (pin "3") (pinfunction "P_3") (pintype "passive"))
      (node (ref "K18") (pin "4") (pinfunction "P1_4") (pintype "passive"))
      (node (ref "K23") (pin "3") (pinfunction "P_3") (pintype "passive"))
      (node (ref "K23") (pin "4") (pinfunction "P1_4") (pintype "passive"))
      (node (ref "K28") (pin "3") (pinfunction "P_3") (pintype "passive"))
      (node (ref "K28") (pin "4") (pinfunction "P1_4") (pintype "passive"))
      (node (ref "K3") (pin "3") (pinfunction "P_3") (pintype "passive"))
      (node (ref "K3") (pin "4") (pinfunction "P1_4") (pintype "passive"))
      (node (ref "K8") (pin "3") (pinfunction "P_3") (pintype "passive"))
      (node (ref "K8") (pin "4") (pinfunction "P1_4") (pintype "passive"))
      (node (ref "R38") (pin "1") (pinfunction "1_1") (pintype "passive"))
      (node (ref "RN1") (pin "4") (pinfunction "4_4") (pintype "passive"))
      (node (ref "U$13") (pin "P$2") (pinfunction "2_P$2") (pintype "passive"))
      (node (ref "U$18") (pin "P$2") (pinfunction "2_P$2") (pintype "passive"))
      (node (ref "U$23") (pin "P$2") (pinfunction "2_P$2") (pintype "passive"))
      (node (ref "U$28") (pin "P$2") (pinfunction "2_P$2") (pintype "passive"))
      (node (ref "U$3") (pin "P$2") (pinfunction "2_P$2") (pintype "passive"))
      (node (ref "U$8") (pin "P$2") (pinfunction "2_P$2") (pintype "passive"))
      (node (ref "Z14") (pin "6") (pinfunction "1A3_6") (pintype "input"))
    )
    (net (code "57") (name "/KEYB4") (class "Default")
      (node (ref "D16") (pin "A") (pinfunction "A_A") (pintype "passive"))
      (node (ref "K14") (pin "3") (pinfunction "P_3") (pintype "passive"))
      (node (ref "K14") (pin "4") (pinfunction "P1_4") (pintype "passive"))
      (node (ref "K17") (pin "3") (pinfunction "P_3") (pintype "passive"))
      (node (ref "K17") (pin "4") (pinfunction "P1_4") (pintype "passive"))
      (node (ref "K24") (pin "3") (pinfunction "P_3") (pintype "passive"))
      (node (ref "K24") (pin "4") (pinfunction "P1_4") (pintype "passive"))
      (node (ref "K27") (pin "3") (pinfunction "P_3") (pintype "passive"))
      (node (ref "K27") (pin "4") (pinfunction "P1_4") (pintype "passive"))
      (node (ref "K4") (pin "3") (pinfunction "P_3") (pintype "passive"))
      (node (ref "K4") (pin "4") (pinfunction "P1_4") (pintype "passive"))
      (node (ref "K7") (pin "3") (pinfunction "P_3") (pintype "passive"))
      (node (ref "K7") (pin "4") (pinfunction "P1_4") (pintype "passive"))
      (node (ref "R40") (pin "1") (pinfunction "1_1") (pintype "passive"))
      (node (ref "RN1") (pin "3") (pinfunction "3_3") (pintype "passive"))
      (node (ref "U$14") (pin "P$2") (pinfunction "2_P$2") (pintype "passive"))
      (node (ref "U$17") (pin "P$2") (pinfunction "2_P$2") (pintype "passive"))
      (node (ref "U$24") (pin "P$2") (pinfunction "2_P$2") (pintype "passive"))
      (node (ref "U$27") (pin "P$2") (pinfunction "2_P$2") (pintype "passive"))
      (node (ref "U$4") (pin "P$2") (pinfunction "2_P$2") (pintype "passive"))
      (node (ref "U$7") (pin "P$2") (pinfunction "2_P$2") (pintype "passive"))
      (node (ref "Z14") (pin "10") (pinfunction "1A4_10") (pintype "input"))
    )
    (net (code "58") (name "/KEYB5") (class "Default")
      (node (ref "D17") (pin "A") (pinfunction "A_A") (pintype "passive"))
      (node (ref "K15") (pin "3") (pinfunction "P_3") (pintype "passive"))
      (node (ref "K15") (pin "4") (pinfunction "P1_4") (pintype "passive"))
      (node (ref "K16") (pin "3") (pinfunction "P_3") (pintype "passive"))
      (node (ref "K16") (pin "4") (pinfunction "P1_4") (pintype "passive"))
      (node (ref "K25") (pin "3") (pinfunction "P_3") (pintype "passive"))
      (node (ref "K25") (pin "4") (pinfunction "P1_4") (pintype "passive"))
      (node (ref "K26") (pin "3") (pinfunction "P_3") (pintype "passive"))
      (node (ref "K26") (pin "4") (pinfunction "P1_4") (pintype "passive"))
      (node (ref "K36") (pin "3") (pinfunction "P_3") (pintype "passive"))
      (node (ref "K36") (pin "4") (pinfunction "P1_4") (pintype "passive"))
      (node (ref "K5") (pin "3") (pinfunction "P_3") (pintype "passive"))
      (node (ref "K5") (pin "4") (pinfunction "P1_4") (pintype "passive"))
      (node (ref "K6") (pin "3") (pinfunction "P_3") (pintype "passive"))
      (node (ref "K6") (pin "4") (pinfunction "P1_4") (pintype "passive"))
      (node (ref "R41") (pin "1") (pinfunction "1_1") (pintype "passive"))
      (node (ref "RN1") (pin "2") (pinfunction "2_2") (pintype "passive"))
      (node (ref "U$15") (pin "P$2") (pinfunction "2_P$2") (pintype "passive"))
      (node (ref "U$16") (pin "P$2") (pinfunction "2_P$2") (pintype "passive"))
      (node (ref "U$25") (pin "P$2") (pinfunction "2_P$2") (pintype "passive"))
      (node (ref "U$26") (pin "P$2") (pinfunction "2_P$2") (pintype "passive"))
      (node (ref "U$36") (pin "P$2") (pinfunction "2_P$2") (pintype "passive"))
      (node (ref "U$5") (pin "P$2") (pinfunction "2_P$2") (pintype "passive"))
      (node (ref "U$6") (pin "P$2") (pinfunction "2_P$2") (pintype "passive"))
      (node (ref "Z14") (pin "12") (pinfunction "2A1_12") (pintype "input"))
    )
    (net (code "59") (name "/KM") (class "Default")
      (node (ref "K39") (pin "3") (pinfunction "P_3") (pintype "passive"))
      (node (ref "K39") (pin "4") (pinfunction "P1_4") (pintype "passive"))
      (node (ref "SJ2") (pin "1") (pinfunction "1_1") (pintype "passive"))
      (node (ref "U$39") (pin "P$2") (pinfunction "2_P$2") (pintype "passive"))
      (node (ref "Z40") (pin "2") (pinfunction "I1_2") (pintype "input"))
    )
    (net (code "60") (name "/KN") (class "Default")
      (node (ref "K38") (pin "3") (pinfunction "P_3") (pintype "passive"))
      (node (ref "K38") (pin "4") (pinfunction "P1_4") (pintype "passive"))
      (node (ref "SJ3") (pin "1") (pinfunction "1_1") (pintype "passive"))
      (node (ref "SJ6") (pin "1") (pinfunction "1_1") (pintype "passive"))
      (node (ref "U$38") (pin "P$2") (pinfunction "2_P$2") (pintype "passive"))
      (node (ref "Z40") (pin "3") (pinfunction "I2_3") (pintype "input"))
    )
    (net (code "61") (name "/KX") (class "Default")
      (node (ref "K34") (pin "3") (pinfunction "P_3") (pintype "passive"))
      (node (ref "K34") (pin "4") (pinfunction "P1_4") (pintype "passive"))
      (node (ref "SJ7") (pin "1") (pinfunction "1_1") (pintype "passive"))
      (node (ref "U$34") (pin "P$2") (pinfunction "2_P$2") (pintype "passive"))
      (node (ref "Z40") (pin "6") (pinfunction "I5_6") (pintype "input"))
    )
    (net (code "62") (name "/KZ") (class "Default")
      (node (ref "K33") (pin "3") (pinfunction "P_3") (pintype "passive"))
      (node (ref "K33") (pin "4") (pinfunction "P1_4") (pintype "passive"))
      (node (ref "SJ6") (pin "2") (pinfunction "2_2") (pintype "passive"))
      (node (ref "U$33") (pin "P$2") (pinfunction "2_P$2") (pintype "passive"))
      (node (ref "Z40") (pin "7") (pinfunction "I6_7") (pintype "input"))
    )
    (net (code "63") (name "/LINE") (class "Default")
      (node (ref "Z22") (pin "12") (pinfunction "O_12") (pintype "output"))
      (node (ref "Z25") (pin "5") (pinfunction "I0_5") (pintype "input"))
    )
    (net (code "64") (name "/N$56") (class "Default")
      (node (ref "JP6") (pin "2") (pinfunction "2_2") (pintype "passive"))
      (node (ref "R42") (pin "1") (pinfunction "1_1") (pintype "passive"))
    )
    (net (code "65") (name "/NC1") (class "Default")
      (node (ref "24A") (pin "1") (pinfunction "P_1") (pintype "passive"))
    )
    (net (code "66") (name "/NC2") (class "Default")
      (node (ref "25A") (pin "1") (pinfunction "P_1") (pintype "passive"))
    )
    (net (code "67") (name "/NC3") (class "Default")
      (node (ref "24B") (pin "1") (pinfunction "P_1") (pintype "passive"))
    )
    (net (code "68") (name "/NC4") (class "Default")
      (node (ref "25B") (pin "1") (pinfunction "P_1") (pintype "passive"))
    )
    (net (code "69") (name "/PHI") (class "Default")
      (node (ref "5A") (pin "1") (pinfunction "P_1") (pintype "passive"))
      (node (ref "Z0") (pin "6") (pinfunction "CLK_6") (pintype "input"))
      (node (ref "Z30") (pin "6") (pinfunction "O_6") (pintype "output"))
    )
    (net (code "70") (name "/RESET") (class "Default")
      (node (ref "12B") (pin "1") (pinfunction "P_1") (pintype "passive"))
      (node (ref "C7") (pin "+") (pinfunction "+_+") (pintype "passive"))
      (node (ref "R25") (pin "1") (pinfunction "1_1") (pintype "passive"))
      (node (ref "S2") (pin "2") (pinfunction "S_2") (pintype "passive"))
      (node (ref "Z0") (pin "26") (pinfunction "RESET_26") (pintype "input"))
    )
    (net (code "71") (name "/ROW1") (class "Default")
      (node (ref "D10") (pin "A") (pinfunction "A_A") (pintype "passive"))
      (node (ref "JP1") (pin "1") (pinfunction "1_1") (pintype "passive"))
      (node (ref "K31") (pin "1") (pinfunction "S_1") (pintype "passive"))
      (node (ref "K31") (pin "2") (pinfunction "S1_2") (pintype "passive"))
      (node (ref "K33") (pin "1") (pinfunction "S_1") (pintype "passive"))
      (node (ref "K33") (pin "2") (pinfunction "S1_2") (pintype "passive"))
      (node (ref "K34") (pin "1") (pinfunction "S_1") (pintype "passive"))
      (node (ref "K34") (pin "2") (pinfunction "S1_2") (pintype "passive"))
      (node (ref "K35") (pin "1") (pinfunction "S_1") (pintype "passive"))
      (node (ref "K35") (pin "2") (pinfunction "S1_2") (pintype "passive"))
      (node (ref "R30") (pin "2") (pinfunction "2_2") (pintype "passive"))
      (node (ref "SJ8") (pin "1") (pinfunction "1_1") (pintype "passive"))
      (node (ref "U$31") (pin "P$1") (pinfunction "1_P$1") (pintype "passive"))
      (node (ref "U$33") (pin "P$1") (pinfunction "1_P$1") (pintype "passive"))
      (node (ref "U$34") (pin "P$1") (pinfunction "1_P$1") (pintype "passive"))
      (node (ref "U$35") (pin "P$1") (pinfunction "1_P$1") (pintype "passive"))
      (node (ref "Z40") (pin "8") (pinfunction "I7_8") (pintype "input"))
    )
    (net (code "72") (name "/ROW2") (class "Default")
      (node (ref "D9") (pin "A") (pinfunction "A_A") (pintype "passive"))
      (node (ref "JP1") (pin "2") (pinfunction "2_2") (pintype "passive"))
      (node (ref "K21") (pin "1") (pinfunction "S_1") (pintype "passive"))
      (node (ref "K21") (pin "2") (pinfunction "S1_2") (pintype "passive"))
      (node (ref "K22") (pin "1") (pinfunction "S_1") (pintype "passive"))
      (node (ref "K22") (pin "2") (pinfunction "S1_2") (pintype "passive"))
      (node (ref "K23") (pin "1") (pinfunction "S_1") (pintype "passive"))
      (node (ref "K23") (pin "2") (pinfunction "S1_2") (pintype "passive"))
      (node (ref "K24") (pin "1") (pinfunction "S_1") (pintype "passive"))
      (node (ref "K24") (pin "2") (pinfunction "S1_2") (pintype "passive"))
      (node (ref "K25") (pin "1") (pinfunction "S_1") (pintype "passive"))
      (node (ref "K25") (pin "2") (pinfunction "S1_2") (pintype "passive"))
      (node (ref "U$21") (pin "P$1") (pinfunction "1_P$1") (pintype "passive"))
      (node (ref "U$22") (pin "P$1") (pinfunction "1_P$1") (pintype "passive"))
      (node (ref "U$23") (pin "P$1") (pinfunction "1_P$1") (pintype "passive"))
      (node (ref "U$24") (pin "P$1") (pinfunction "1_P$1") (pintype "passive"))
      (node (ref "U$25") (pin "P$1") (pinfunction "1_P$1") (pintype "passive"))
    )
    (net (code "73") (name "/ROW3") (class "Default")
      (node (ref "D8") (pin "A") (pinfunction "A_A") (pintype "passive"))
      (node (ref "JP1") (pin "3") (pinfunction "3_3") (pintype "passive"))
      (node (ref "K11") (pin "1") (pinfunction "S_1") (pintype "passive"))
      (node (ref "K11") (pin "2") (pinfunction "S1_2") (pintype "passive"))
      (node (ref "K12") (pin "1") (pinfunction "S_1") (pintype "passive"))
      (node (ref "K12") (pin "2") (pinfunction "S1_2") (pintype "passive"))
      (node (ref "K13") (pin "1") (pinfunction "S_1") (pintype "passive"))
      (node (ref "K13") (pin "2") (pinfunction "S1_2") (pintype "passive"))
      (node (ref "K14") (pin "1") (pinfunction "S_1") (pintype "passive"))
      (node (ref "K14") (pin "2") (pinfunction "S1_2") (pintype "passive"))
      (node (ref "K15") (pin "1") (pinfunction "S_1") (pintype "passive"))
      (node (ref "K15") (pin "2") (pinfunction "S1_2") (pintype "passive"))
      (node (ref "U$11") (pin "P$1") (pinfunction "1_P$1") (pintype "passive"))
      (node (ref "U$12") (pin "P$1") (pinfunction "1_P$1") (pintype "passive"))
      (node (ref "U$13") (pin "P$1") (pinfunction "1_P$1") (pintype "passive"))
      (node (ref "U$14") (pin "P$1") (pinfunction "1_P$1") (pintype "passive"))
      (node (ref "U$15") (pin "P$1") (pinfunction "1_P$1") (pintype "passive"))
    )
    (net (code "74") (name "/ROW4") (class "Default")
      (node (ref "D7") (pin "A") (pinfunction "A_A") (pintype "passive"))
      (node (ref "JP1") (pin "4") (pinfunction "4_4") (pintype "passive"))
      (node (ref "K1") (pin "1") (pinfunction "S_1") (pintype "passive"))
      (node (ref "K1") (pin "2") (pinfunction "S1_2") (pintype "passive"))
      (node (ref "K2") (pin "1") (pinfunction "S_1") (pintype "passive"))
      (node (ref "K2") (pin "2") (pinfunction "S1_2") (pintype "passive"))
      (node (ref "K3") (pin "1") (pinfunction "S_1") (pintype "passive"))
      (node (ref "K3") (pin "2") (pinfunction "S1_2") (pintype "passive"))
      (node (ref "K4") (pin "1") (pinfunction "S_1") (pintype "passive"))
      (node (ref "K4") (pin "2") (pinfunction "S1_2") (pintype "passive"))
      (node (ref "K5") (pin "1") (pinfunction "S_1") (pintype "passive"))
      (node (ref "K5") (pin "2") (pinfunction "S1_2") (pintype "passive"))
      (node (ref "U$1") (pin "P$1") (pinfunction "1_P$1") (pintype "passive"))
      (node (ref "U$2") (pin "P$1") (pinfunction "1_P$1") (pintype "passive"))
      (node (ref "U$3") (pin "P$1") (pinfunction "1_P$1") (pintype "passive"))
      (node (ref "U$4") (pin "P$1") (pinfunction "1_P$1") (pintype "passive"))
      (node (ref "U$5") (pin "P$1") (pinfunction "1_P$1") (pintype "passive"))
    )
    (net (code "75") (name "/ROW5") (class "Default")
      (node (ref "D6") (pin "A") (pinfunction "A_A") (pintype "passive"))
      (node (ref "JP1") (pin "5") (pinfunction "5_5") (pintype "passive"))
      (node (ref "K10") (pin "1") (pinfunction "S_1") (pintype "passive"))
      (node (ref "K10") (pin "2") (pinfunction "S1_2") (pintype "passive"))
      (node (ref "K6") (pin "1") (pinfunction "S_1") (pintype "passive"))
      (node (ref "K6") (pin "2") (pinfunction "S1_2") (pintype "passive"))
      (node (ref "K7") (pin "1") (pinfunction "S_1") (pintype "passive"))
      (node (ref "K7") (pin "2") (pinfunction "S1_2") (pintype "passive"))
      (node (ref "K8") (pin "1") (pinfunction "S_1") (pintype "passive"))
      (node (ref "K8") (pin "2") (pinfunction "S1_2") (pintype "passive"))
      (node (ref "K9") (pin "1") (pinfunction "S_1") (pintype "passive"))
      (node (ref "K9") (pin "2") (pinfunction "S1_2") (pintype "passive"))
      (node (ref "U$10") (pin "P$1") (pinfunction "1_P$1") (pintype "passive"))
      (node (ref "U$6") (pin "P$1") (pinfunction "1_P$1") (pintype "passive"))
      (node (ref "U$7") (pin "P$1") (pinfunction "1_P$1") (pintype "passive"))
      (node (ref "U$8") (pin "P$1") (pinfunction "1_P$1") (pintype "passive"))
      (node (ref "U$9") (pin "P$1") (pinfunction "1_P$1") (pintype "passive"))
    )
    (net (code "76") (name "/ROW6") (class "Default")
      (node (ref "D5") (pin "A") (pinfunction "A_A") (pintype "passive"))
      (node (ref "JP1") (pin "6") (pinfunction "6_6") (pintype "passive"))
      (node (ref "K16") (pin "1") (pinfunction "S_1") (pintype "passive"))
      (node (ref "K16") (pin "2") (pinfunction "S1_2") (pintype "passive"))
      (node (ref "K17") (pin "1") (pinfunction "S_1") (pintype "passive"))
      (node (ref "K17") (pin "2") (pinfunction "S1_2") (pintype "passive"))
      (node (ref "K18") (pin "1") (pinfunction "S_1") (pintype "passive"))
      (node (ref "K18") (pin "2") (pinfunction "S1_2") (pintype "passive"))
      (node (ref "K19") (pin "1") (pinfunction "S_1") (pintype "passive"))
      (node (ref "K19") (pin "2") (pinfunction "S1_2") (pintype "passive"))
      (node (ref "K20") (pin "1") (pinfunction "S_1") (pintype "passive"))
      (node (ref "K20") (pin "2") (pinfunction "S1_2") (pintype "passive"))
      (node (ref "U$16") (pin "P$1") (pinfunction "1_P$1") (pintype "passive"))
      (node (ref "U$17") (pin "P$1") (pinfunction "1_P$1") (pintype "passive"))
      (node (ref "U$18") (pin "P$1") (pinfunction "1_P$1") (pintype "passive"))
      (node (ref "U$19") (pin "P$1") (pinfunction "1_P$1") (pintype "passive"))
      (node (ref "U$20") (pin "P$1") (pinfunction "1_P$1") (pintype "passive"))
    )
    (net (code "77") (name "/ROW7") (class "Default")
      (node (ref "D4") (pin "A") (pinfunction "A_A") (pintype "passive"))
      (node (ref "JP1") (pin "7") (pinfunction "7_7") (pintype "passive"))
      (node (ref "K26") (pin "1") (pinfunction "S_1") (pintype "passive"))
      (node (ref "K26") (pin "2") (pinfunction "S1_2") (pintype "passive"))
      (node (ref "K27") (pin "1") (pinfunction "S_1") (pintype "passive"))
      (node (ref "K27") (pin "2") (pinfunction "S1_2") (pintype "passive"))
      (node (ref "K28") (pin "1") (pinfunction "S_1") (pintype "passive"))
      (node (ref "K28") (pin "2") (pinfunction "S1_2") (pintype "passive"))
      (node (ref "K29") (pin "1") (pinfunction "S_1") (pintype "passive"))
      (node (ref "K29") (pin "2") (pinfunction "S1_2") (pintype "passive"))
      (node (ref "K30") (pin "1") (pinfunction "S_1") (pintype "passive"))
      (node (ref "K30") (pin "2") (pinfunction "S1_2") (pintype "passive"))
      (node (ref "U$26") (pin "P$1") (pinfunction "1_P$1") (pintype "passive"))
      (node (ref "U$27") (pin "P$1") (pinfunction "1_P$1") (pintype "passive"))
      (node (ref "U$28") (pin "P$1") (pinfunction "1_P$1") (pintype "passive"))
      (node (ref "U$29") (pin "P$1") (pinfunction "1_P$1") (pintype "passive"))
      (node (ref "U$30") (pin "P$1") (pinfunction "1_P$1") (pintype "passive"))
    )
    (net (code "78") (name "/ROW8") (class "Default")
      (node (ref "D3") (pin "A") (pinfunction "A_A") (pintype "passive"))
      (node (ref "JP1") (pin "8") (pinfunction "8_8") (pintype "passive"))
      (node (ref "K37") (pin "1") (pinfunction "S_1") (pintype "passive"))
      (node (ref "K37") (pin "2") (pinfunction "S1_2") (pintype "passive"))
      (node (ref "K38") (pin "1") (pinfunction "S_1") (pintype "passive"))
      (node (ref "K38") (pin "2") (pinfunction "S1_2") (pintype "passive"))
      (node (ref "K39") (pin "1") (pinfunction "S_1") (pintype "passive"))
      (node (ref "K39") (pin "2") (pinfunction "S1_2") (pintype "passive"))
      (node (ref "K40") (pin "1") (pinfunction "S_1") (pintype "passive"))
      (node (ref "K40") (pin "2") (pinfunction "S1_2") (pintype "passive"))
      (node (ref "K41") (pin "1") (pinfunction "S_1") (pintype "passive"))
      (node (ref "K41") (pin "2") (pinfunction "S1_2") (pintype "passive"))
      (node (ref "R31") (pin "2") (pinfunction "2_2") (pintype "passive"))
      (node (ref "SJ9") (pin "1") (pinfunction "1_1") (pintype "passive"))
      (node (ref "U$37") (pin "P$1") (pinfunction "1_P$1") (pintype "passive"))
      (node (ref "U$38") (pin "P$1") (pinfunction "1_P$1") (pintype "passive"))
      (node (ref "U$39") (pin "P$1") (pinfunction "1_P$1") (pintype "passive"))
      (node (ref "U$40") (pin "P$1") (pinfunction "1_P$1") (pintype "passive"))
      (node (ref "U$41") (pin "P$1") (pinfunction "1_P$1") (pintype "passive"))
      (node (ref "U$42") (pin "P$1") (pinfunction "1_P$1") (pintype "passive"))
      (node (ref "Z40") (pin "9") (pinfunction "I8_9") (pintype "input"))
    )
    (net (code "79") (name "/ROW_SS") (class "Default")
      (node (ref "D13") (pin "A") (pinfunction "A_A") (pintype "passive"))
      (node (ref "K32") (pin "1") (pinfunction "S_1") (pintype "passive"))
      (node (ref "K32") (pin "2") (pinfunction "S1_2") (pintype "passive"))
      (node (ref "U$32") (pin "P$1") (pinfunction "1_P$1") (pintype "passive"))
    )
    (net (code "80") (name "/ROW_V") (class "Default")
      (node (ref "D12") (pin "A") (pinfunction "A_A") (pintype "passive"))
      (node (ref "K36") (pin "1") (pinfunction "S_1") (pintype "passive"))
      (node (ref "K36") (pin "2") (pinfunction "S1_2") (pintype "passive"))
      (node (ref "U$36") (pin "P$1") (pinfunction "1_P$1") (pintype "passive"))
    )
    (net (code "81") (name "/SYNC") (class "Default")
      (node (ref "D1") (pin "C") (pinfunction "C_C") (pintype "passive"))
      (node (ref "Z1") (pin "13") (pinfunction "CLR_13") (pintype "input"))
      (node (ref "Z25") (pin "4") (pinfunction "O_4") (pintype "output"))
    )
    (net (code "82") (name "/VA0") (class "Default")
      (node (ref "1A1") (pin "1") (pinfunction "P_1") (pintype "passive"))
      (node (ref "R11") (pin "2") (pinfunction "2_2") (pintype "passive"))
      (node (ref "Z15") (pin "3") (pinfunction "1Y1_3") (pintype "tri_state"))
      (node (ref "Z5-6") (pin "21") (pinfunction "A0_21") (pintype "input"))
    )
    (net (code "83") (name "/VA1") (class "Default")
      (node (ref "9A1") (pin "1") (pinfunction "P_1") (pintype "passive"))
      (node (ref "R12") (pin "2") (pinfunction "2_2") (pintype "passive"))
      (node (ref "Z15") (pin "5") (pinfunction "1Y2_5") (pintype "tri_state"))
      (node (ref "Z5-6") (pin "23") (pinfunction "A1_23") (pintype "input"))
    )
    (net (code "84") (name "/VA2") (class "Default")
      (node (ref "6B2") (pin "1") (pinfunction "P_1") (pintype "passive"))
      (node (ref "R13") (pin "2") (pinfunction "2_2") (pintype "passive"))
      (node (ref "Z15") (pin "7") (pinfunction "1Y3_7") (pintype "tri_state"))
      (node (ref "Z5-6") (pin "24") (pinfunction "A2_24") (pintype "input"))
    )
    (net (code "85") (name "/VA3") (class "Default")
      (node (ref "1B1") (pin "1") (pinfunction "P_1") (pintype "passive"))
      (node (ref "R14") (pin "2") (pinfunction "2_2") (pintype "passive"))
      (node (ref "Z15") (pin "9") (pinfunction "1Y4_9") (pintype "tri_state"))
      (node (ref "Z5-6") (pin "25") (pinfunction "A3_25") (pintype "input"))
    )
    (net (code "86") (name "/VA4") (class "Default")
      (node (ref "2A1") (pin "1") (pinfunction "P_1") (pintype "passive"))
      (node (ref "R15") (pin "2") (pinfunction "2_2") (pintype "passive"))
      (node (ref "Z15") (pin "11") (pinfunction "2Y1_11") (pintype "tri_state"))
      (node (ref "Z5-6") (pin "26") (pinfunction "A4_26") (pintype "input"))
    )
    (net (code "87") (name "/VA5") (class "Default")
      (node (ref "2B1") (pin "1") (pinfunction "P_1") (pintype "passive"))
      (node (ref "R16") (pin "2") (pinfunction "2_2") (pintype "passive"))
      (node (ref "Z15") (pin "13") (pinfunction "2Y2_13") (pintype "tri_state"))
      (node (ref "Z5-6") (pin "1") (pinfunction "A5_1") (pintype "input"))
    )
    (net (code "88") (name "/VA6") (class "Default")
      (node (ref "5B2") (pin "1") (pinfunction "P_1") (pintype "passive"))
      (node (ref "R17") (pin "2") (pinfunction "2_2") (pintype "passive"))
      (node (ref "Z16") (pin "3") (pinfunction "1Y1_3") (pintype "tri_state"))
      (node (ref "Z5-6") (pin "2") (pinfunction "A6_2") (pintype "input"))
    )
    (net (code "89") (name "/VA7") (class "Default")
      (node (ref "8A1") (pin "1") (pinfunction "P_1") (pintype "passive"))
      (node (ref "R18") (pin "2") (pinfunction "2_2") (pintype "passive"))
      (node (ref "Z16") (pin "5") (pinfunction "1Y2_5") (pintype "tri_state"))
      (node (ref "Z5-6") (pin "3") (pinfunction "A7_3") (pintype "input"))
    )
    (net (code "90") (name "/VA8") (class "Default")
      (node (ref "8B2") (pin "1") (pinfunction "P_1") (pintype "passive"))
      (node (ref "R19") (pin "2") (pinfunction "2_2") (pintype "passive"))
      (node (ref "Z16") (pin "7") (pinfunction "1Y3_7") (pintype "tri_state"))
      (node (ref "Z5-6") (pin "4") (pinfunction "A8_4") (pintype "input"))
    )
    (net (code "91") (name "/VA9") (class "Default")
      (node (ref "9B1") (pin "1") (pinfunction "P_1") (pintype "passive"))
      (node (ref "R20") (pin "2") (pinfunction "2_2") (pintype "passive"))
      (node (ref "Z16") (pin "9") (pinfunction "1Y4_9") (pintype "tri_state"))
      (node (ref "Z5-6") (pin "5") (pinfunction "A9_5") (pintype "input"))
    )
    (net (code "92") (name "/VD0") (class "Default")
      (node (ref "5A1") (pin "1") (pinfunction "P_1") (pintype "passive"))
      (node (ref "R100") (pin "2") (pinfunction "2_2") (pintype "passive"))
      (node (ref "Z18") (pin "3") (pinfunction "1Y1_3") (pintype "tri_state"))
      (node (ref "Z5-6") (pin "11") (pinfunction "DQ0_11") (pintype "bidirectional"))
      (node (ref "Z7-8") (pin "25") (pinfunction "A3_25") (pintype "input"))
    )
    (net (code "93") (name "/VD1") (class "Default")
      (node (ref "4B2") (pin "1") (pinfunction "P_1") (pintype "passive"))
      (node (ref "R101") (pin "2") (pinfunction "2_2") (pintype "passive"))
      (node (ref "Z17") (pin "13") (pinfunction "2Y2_13") (pintype "tri_state"))
      (node (ref "Z5-6") (pin "12") (pinfunction "DQ1_12") (pintype "bidirectional"))
      (node (ref "Z7-8") (pin "26") (pinfunction "A4_26") (pintype "input"))
    )
    (net (code "94") (name "/VD2") (class "Default")
      (node (ref "3B1") (pin "1") (pinfunction "P_1") (pintype "passive"))
      (node (ref "R102") (pin "2") (pinfunction "2_2") (pintype "passive"))
      (node (ref "Z17") (pin "11") (pinfunction "2Y1_11") (pintype "tri_state"))
      (node (ref "Z5-6") (pin "13") (pinfunction "DQ2_13") (pintype "bidirectional"))
      (node (ref "Z7-8") (pin "1") (pinfunction "A5_1") (pintype "input"))
    )
    (net (code "95") (name "/VD3") (class "Default")
      (node (ref "3A1") (pin "1") (pinfunction "P_1") (pintype "passive"))
      (node (ref "R103") (pin "2") (pinfunction "2_2") (pintype "passive"))
      (node (ref "Z17") (pin "9") (pinfunction "1Y4_9") (pintype "tri_state"))
      (node (ref "Z5-6") (pin "15") (pinfunction "DQ3_15") (pintype "bidirectional"))
      (node (ref "Z7-8") (pin "2") (pinfunction "A6_2") (pintype "input"))
    )
    (net (code "96") (name "/VD4") (class "Default")
      (node (ref "4A1") (pin "1") (pinfunction "P_1") (pintype "passive"))
      (node (ref "R104") (pin "2") (pinfunction "2_2") (pintype "passive"))
      (node (ref "Z17") (pin "7") (pinfunction "1Y3_7") (pintype "tri_state"))
      (node (ref "Z5-6") (pin "16") (pinfunction "DQ4_16") (pintype "bidirectional"))
      (node (ref "Z7-8") (pin "3") (pinfunction "A7_3") (pintype "input"))
    )
    (net (code "97") (name "/VD5") (class "Default")
      (node (ref "7A1") (pin "1") (pinfunction "P_1") (pintype "passive"))
      (node (ref "R105") (pin "2") (pinfunction "2_2") (pintype "passive"))
      (node (ref "Z17") (pin "5") (pinfunction "1Y2_5") (pintype "tri_state"))
      (node (ref "Z5-6") (pin "17") (pinfunction "DQ5_17") (pintype "bidirectional"))
      (node (ref "Z7-8") (pin "4") (pinfunction "A8_4") (pintype "input"))
    )
    (net (code "98") (name "/VD6") (class "Default")
      (node (ref "10B1") (pin "1") (pinfunction "P_1") (pintype "passive"))
      (node (ref "R106") (pin "2") (pinfunction "2_2") (pintype "passive"))
      (node (ref "Z17") (pin "3") (pinfunction "1Y1_3") (pintype "tri_state"))
      (node (ref "Z5-6") (pin "18") (pinfunction "DQ6_18") (pintype "bidirectional"))
      (node (ref "Z7-8") (pin "5") (pinfunction "A9_5") (pintype "input"))
    )
    (net (code "99") (name "/VD7") (class "Default")
      (node (ref "6A1") (pin "1") (pinfunction "P_1") (pintype "passive"))
      (node (ref "R107") (pin "2") (pinfunction "2_2") (pintype "passive"))
      (node (ref "Z20") (pin "13") (pinfunction "I1_13") (pintype "input"))
      (node (ref "Z5-6") (pin "19") (pinfunction "DQ7_19") (pintype "bidirectional"))
    )
    (net (code "100") (name "/VIDEN") (class "Default")
      (node (ref "Z19") (pin "10") (pinfunction "I1_10") (pintype "input"))
      (node (ref "Z19") (pin "5") (pinfunction "I1_5") (pintype "input"))
      (node (ref "Z20") (pin "12") (pinfunction "I0_12") (pintype "input"))
      (node (ref "Z20") (pin "6") (pinfunction "O_6") (pintype "output"))
    )
    (net (code "101") (name "/VIDEO") (class "Default")
      (node (ref "13B1") (pin "1") (pinfunction "P_1") (pintype "passive"))
      (node (ref "14B1") (pin "1") (pinfunction "P_1") (pintype "passive"))
      (node (ref "15B1") (pin "1") (pinfunction "P_1") (pintype "passive"))
    )
    (net (code "104") (name "/{slash}BUSAK") (class "Default")
      (node (ref "9B") (pin "1") (pinfunction "P_1") (pintype "passive"))
      (node (ref "Z0") (pin "23") (pinfunction "BUSAK_23") (pintype "output"))
    )
    (net (code "105") (name "/{slash}BUSRQ") (class "Default")
      (node (ref "11B") (pin "1") (pinfunction "P_1") (pintype "passive"))
      (node (ref "R24") (pin "1") (pinfunction "1_1") (pintype "passive"))
      (node (ref "Z0") (pin "25") (pinfunction "BUSRQ_25") (pintype "input"))
    )
    (net (code "106") (name "/{slash}HALT") (class "Default")
      (node (ref "4B") (pin "1") (pinfunction "P_1") (pintype "passive"))
      (node (ref "Z0") (pin "18") (pinfunction "HALT_18") (pintype "output"))
    )
    (net (code "107") (name "/{slash}INT") (class "Default")
      (node (ref "2B") (pin "1") (pinfunction "P_1") (pintype "passive"))
      (node (ref "Z0") (pin "16") (pinfunction "INT_16") (pintype "input"))
      (node (ref "Z19") (pin "11") (pinfunction "O_11") (pintype "output"))
    )
    (net (code "108") (name "/{slash}IORQ") (class "Default")
      (node (ref "6B") (pin "1") (pinfunction "P_1") (pintype "passive"))
      (node (ref "Z0") (pin "20") (pinfunction "IORQ_20") (pintype "output"))
      (node (ref "Z26") (pin "4") (pinfunction "I0_4") (pintype "input"))
    )
    (net (code "109") (name "/{slash}M1") (class "Default")
      (node (ref "13B") (pin "1") (pinfunction "P_1") (pintype "passive"))
      (node (ref "Z0") (pin "27") (pinfunction "M1_27") (pintype "output"))
    )
    (net (code "110") (name "/{slash}MREQ") (class "Default")
      (node (ref "5B") (pin "1") (pinfunction "P_1") (pintype "passive"))
      (node (ref "Z0") (pin "19") (pinfunction "MREQ_19") (pintype "output"))
      (node (ref "Z29") (pin "4") (pinfunction "G2A_4") (pintype "input"))
    )
    (net (code "111") (name "/{slash}NMI") (class "Default")
      (node (ref "3B") (pin "1") (pinfunction "P_1") (pintype "passive"))
      (node (ref "R39") (pin "1") (pinfunction "1_1") (pintype "passive"))
      (node (ref "Z0") (pin "17") (pinfunction "NMI_17") (pintype "input"))
    )
    (net (code "112") (name "/{slash}RD") (class "Default")
      (node (ref "7B") (pin "1") (pinfunction "P_1") (pintype "passive"))
      (node (ref "Z0") (pin "21") (pinfunction "RD_21") (pintype "output"))
      (node (ref "Z26") (pin "10") (pinfunction "I1_10") (pintype "input"))
      (node (ref "Z3-4") (pin "22") (pinfunction "~{OE}_22") (pintype "input"))
    )
    (net (code "113") (name "/{slash}RFSH") (class "Default")
      (node (ref "14B") (pin "1") (pinfunction "P_1") (pintype "passive"))
      (node (ref "Z0") (pin "28") (pinfunction "RFSH_28") (pintype "output"))
    )
    (net (code "114") (name "/{slash}VHOLD") (class "Default")
      (node (ref "Z16") (pin "15") (pinfunction "2G_15") (pintype "input"))
      (node (ref "Z19") (pin "8") (pinfunction "O_8") (pintype "output"))
      (node (ref "Z26") (pin "1") (pinfunction "I0_1") (pintype "input"))
    )
    (net (code "115") (name "/{slash}WAIT") (class "Default")
      (node (ref "10B") (pin "1") (pinfunction "P_1") (pintype "passive"))
      (node (ref "C8") (pin "1") (pinfunction "1_1") (pintype "passive"))
      (node (ref "Z0") (pin "24") (pinfunction "WAIT_24") (pintype "input"))
      (node (ref "Z26") (pin "3") (pinfunction "O_3") (pintype "output"))
    )
    (net (code "116") (name "/{slash}WE1") (class "Default")
      (node (ref "22A") (pin "1") (pinfunction "P_1") (pintype "passive"))
      (node (ref "7B2") (pin "1") (pinfunction "P_1") (pintype "passive"))
      (node (ref "Z26") (pin "11") (pinfunction "O_11") (pintype "output"))
      (node (ref "Z30") (pin "1") (pinfunction "I0_1") (pintype "input"))
      (node (ref "Z30") (pin "2") (pinfunction "I1_2") (pintype "input"))
      (node (ref "Z5-6") (pin "27") (pinfunction "~{WE}_27") (pintype "input"))
      (node (ref "Z7-8") (pin "27") (pinfunction "~{WE}_27") (pintype "input"))
    )
    (net (code "117") (name "/{slash}WR") (class "Default")
      (node (ref "8B") (pin "1") (pinfunction "P_1") (pintype "passive"))
      (node (ref "Z0") (pin "22") (pinfunction "WR_22") (pintype "output"))
      (node (ref "Z25") (pin "9") (pinfunction "I1_9") (pintype "input"))
      (node (ref "Z26") (pin "12") (pinfunction "I0_12") (pintype "input"))
      (node (ref "Z3-4") (pin "27") (pinfunction "~{WE}_27") (pintype "input"))
    )
    (net (code "118") (name "GND") (class "Default")
      (node (ref "11A1") (pin "1") (pinfunction "P_1") (pintype "passive"))
      (node (ref "13A1") (pin "1") (pinfunction "P_1") (pintype "passive"))
      (node (ref "14A1") (pin "1") (pinfunction "P_1") (pintype "passive"))
      (node (ref "15A1") (pin "1") (pinfunction "P_1") (pintype "passive"))
      (node (ref "1A") (pin "1") (pinfunction "P_1") (pintype "passive"))
      (node (ref "1B") (pin "1") (pinfunction "P_1") (pintype "passive"))
      (node (ref "26A") (pin "1") (pinfunction "P_1") (pintype "passive"))
      (node (ref "26B") (pin "1") (pinfunction "P_1") (pintype "passive"))
      (node (ref "27A") (pin "1") (pinfunction "P_1") (pintype "passive"))
      (node (ref "27B") (pin "1") (pinfunction "P_1") (pintype "passive"))
      (node (ref "28A") (pin "1") (pinfunction "P_1") (pintype "passive"))
      (node (ref "28B") (pin "1") (pinfunction "P_1") (pintype "passive"))
      (node (ref "2A") (pin "1") (pinfunction "P_1") (pintype "passive"))
      (node (ref "C10") (pin "2") (pinfunction "2_2") (pintype "passive"))
      (node (ref "C11") (pin "-") (pinfunction "-_-") (pintype "passive"))
      (node (ref "C12") (pin "-") (pinfunction "-_-") (pintype "passive"))
      (node (ref "C13") (pin "1") (pinfunction "1_1") (pintype "passive"))
      (node (ref "C14") (pin "1") (pinfunction "1_1") (pintype "passive"))
      (node (ref "C15") (pin "1") (pinfunction "1_1") (pintype "passive"))
      (node (ref "C16") (pin "1") (pinfunction "1_1") (pintype "passive"))
      (node (ref "C17") (pin "1") (pinfunction "1_1") (pintype "passive"))
      (node (ref "C18") (pin "1") (pinfunction "1_1") (pintype "passive"))
      (node (ref "C19") (pin "1") (pinfunction "1_1") (pintype "passive"))
      (node (ref "C2") (pin "2") (pinfunction "2_2") (pintype "passive"))
      (node (ref "C20") (pin "1") (pinfunction "1_1") (pintype "passive"))
      (node (ref "C21") (pin "1") (pinfunction "1_1") (pintype "passive"))
      (node (ref "C22") (pin "1") (pinfunction "1_1") (pintype "passive"))
      (node (ref "C4") (pin "1") (pinfunction "1_1") (pintype "passive"))
      (node (ref "C7") (pin "-") (pinfunction "-_-") (pintype "passive"))
      (node (ref "C8") (pin "2") (pinfunction "2_2") (pintype "passive"))
      (node (ref "C9") (pin "-") (pinfunction "-_-") (pintype "passive"))
      (node (ref "EAR") (pin "GND") (pinfunction "SLEEVE_GND") (pintype "passive"))
      (node (ref "JP6") (pin "1") (pinfunction "1_1") (pintype "passive"))
      (node (ref "LED1") (pin "K") (pinfunction "C_K") (pintype "passive"))
      (node (ref "LED2") (pin "K") (pinfunction "C_K") (pintype "passive"))
      (node (ref "MIC") (pin "GND") (pinfunction "SLEEVE_GND") (pintype "passive"))
      (node (ref "POWER") (pin "GND") (pinfunction "SLEEVE_GND") (pintype "passive"))
      (node (ref "Q1") (pin "3") (pinfunction "E_3") (pintype "passive"))
      (node (ref "Q3") (pin "1") (pinfunction "E_1") (pintype "passive"))
      (node (ref "R32") (pin "1") (pinfunction "1_1") (pintype "passive"))
      (node (ref "R4") (pin "E") (pinfunction "E_E") (pintype "passive"))
      (node (ref "R5") (pin "1") (pinfunction "1_1") (pintype "passive"))
      (node (ref "R6") (pin "1") (pinfunction "1_1") (pintype "passive"))
      (node (ref "S1") (pin "1") (pinfunction "1_1") (pintype "passive"))
      (node (ref "S1") (pin "2") (pinfunction "2_2") (pintype "passive"))
      (node (ref "S2") (pin "1") (pinfunction "P_1") (pintype "passive"))
      (node (ref "U1") (pin "2") (pinfunction "GND_2") (pintype "passive"))
      (node (ref "U2") (pin "2") (pinfunction "VEE_2") (pintype "power_in"))
      (node (ref "X1") (pin "2") (pinfunction "2_2") (pintype "passive"))
      (node (ref "X2") (pin "1") (pinfunction "2_1") (pintype "passive"))
      (node (ref "Z0") (pin "29") (pinfunction "GND_29") (pintype "power_in"))
      (node (ref "Z1") (pin "1") (pinfunction "CLR_1") (pintype "input"))
      (node (ref "Z1") (pin "2") (pinfunction "D_2") (pintype "input"))
      (node (ref "Z1") (pin "3") (pinfunction "CLK_3") (pintype "input"))
      (node (ref "Z1") (pin "4") (pinfunction "PRE_4") (pintype "input"))
      (node (ref "Z1-2") (pin "14") (pinfunction "VSS_14") (pintype "power_in"))
      (node (ref "Z10") (pin "12") (pinfunction "CLR_12") (pintype "input"))
      (node (ref "Z18") (pin "15") (pinfunction "2G_15") (pintype "input"))
      (node (ref "Z23") (pin "10") (pinfunction "I1_10") (pintype "input"))
      (node (ref "Z28") (pin "1") (pinfunction "SER_1") (pintype "input"))
      (node (ref "Z28") (pin "6") (pinfunction "INH_6") (pintype "input"))
      (node (ref "Z40") (pin "10") (pinfunction "GND_10") (pintype "power_in"))
      (node (ref "Z41") (pin "12") (pinfunction "I0_12") (pintype "input"))
      (node (ref "Z41") (pin "13") (pinfunction "I1_13") (pintype "input"))
      (node (ref "Z5-6") (pin "10") (pinfunction "A14_10") (pintype "input"))
      (node (ref "Z5-6") (pin "6") (pinfunction "A10_6") (pintype "input"))
      (node (ref "Z5-6") (pin "7") (pinfunction "A11_7") (pintype "input"))
      (node (ref "Z5-6") (pin "8") (pinfunction "A12_8") (pintype "input"))
      (node (ref "Z5-6") (pin "9") (pinfunction "A13_9") (pintype "input"))
      (node (ref "Z7-8") (pin "10") (pinfunction "A14_10") (pintype "input"))
      (node (ref "Z7-8") (pin "6") (pinfunction "A10_6") (pintype "input"))
      (node (ref "Z7-8") (pin "7") (pinfunction "A11_7") (pintype "input"))
      (node (ref "Z7-8") (pin "8") (pinfunction "A12_8") (pintype "input"))
      (node (ref "Z7-8") (pin "9") (pinfunction "A13_9") (pintype "input"))
      (node (ref "Z9") (pin "12") (pinfunction "CLR_12") (pintype "input"))
      (node (ref "Z9") (pin "2") (pinfunction "CLR_2") (pintype "input"))
    )
    (net (code "119") (name "Net-(C1-Pad1)") (class "Default")
      (node (ref "C1") (pin "1") (pinfunction "1_1") (pintype "passive"))
      (node (ref "X1") (pin "3") (pinfunction "3_3") (pintype "passive"))
    )
    (net (code "120") (name "Net-(C3-Pad1)") (class "Default")
      (node (ref "C3") (pin "1") (pinfunction "1_1") (pintype "passive"))
      (node (ref "EAR") (pin "TIP") (pinfunction "TIP_TIP") (pintype "passive"))
      (node (ref "R6") (pin "2") (pinfunction "2_2") (pintype "passive"))
    )
    (net (code "121") (name "Net-(C5-Pad1)") (class "Default")
      (node (ref "C5") (pin "1") (pinfunction "1_1") (pintype "passive"))
      (node (ref "C6") (pin "1") (pinfunction "1_1") (pintype "passive"))
      (node (ref "MIC") (pin "TIP") (pinfunction "TIP_TIP") (pintype "passive"))
    )
    (net (code "122") (name "Net-(C6-Pad2)") (class "Default")
      (node (ref "C6") (pin "2") (pinfunction "2_2") (pintype "passive"))
      (node (ref "R10") (pin "1") (pinfunction "1_1") (pintype "passive"))
    )
    (net (code "123") (name "Net-(D1-PadA)") (class "Default")
      (node (ref "D1") (pin "A") (pinfunction "A_A") (pintype "passive"))
      (node (ref "R3") (pin "S") (pinfunction "S_S") (pintype "passive"))
      (node (ref "R4") (pin "A") (pinfunction "A_A") (pintype "passive"))
      (node (ref "SJ1") (pin "2") (pinfunction "2_2") (pintype "passive"))
    )
    (net (code "124") (name "Net-(JP5-Pad2)") (class "Default")
      (node (ref "JP5") (pin "2") (pinfunction "2_2") (pintype "passive"))
      (node (ref "R11") (pin "1") (pinfunction "1_1") (pintype "passive"))
    )
    (net (code "125") (name "Net-(JP7-Pad2)") (class "Default")
      (node (ref "JP7") (pin "2") (pinfunction "2_2") (pintype "passive"))
      (node (ref "POWER") (pin "TIP") (pinfunction "TIP_TIP") (pintype "passive"))
    )
    (net (code "126") (name "Net-(JP10-Pad2)") (class "Default")
      (node (ref "JP10") (pin "2") (pinfunction "2_2") (pintype "passive"))
      (node (ref "R12") (pin "1") (pinfunction "1_1") (pintype "passive"))
    )
    (net (code "127") (name "Net-(JP10B-2)") (class "Default")
      (node (ref "JP10") (pin "4") (pinfunction "2_4") (pintype "passive"))
      (node (ref "R13") (pin "1") (pinfunction "1_1") (pintype "passive"))
    )
    (net (code "128") (name "Net-(JP10C-2)") (class "Default")
      (node (ref "JP10") (pin "6") (pinfunction "2_6") (pintype "passive"))
      (node (ref "R14") (pin "1") (pinfunction "1_1") (pintype "passive"))
    )
    (net (code "129") (name "Net-(JP10D-2)") (class "Default")
      (node (ref "JP10") (pin "8") (pinfunction "2_8") (pintype "passive"))
      (node (ref "R15") (pin "1") (pinfunction "1_1") (pintype "passive"))
    )
    (net (code "130") (name "Net-(JP15-Pad2)") (class "Default")
      (node (ref "JP15") (pin "2") (pinfunction "2_2") (pintype "passive"))
      (node (ref "R16") (pin "1") (pinfunction "1_1") (pintype "passive"))
    )
    (net (code "131") (name "Net-(JP15B-2)") (class "Default")
      (node (ref "JP15") (pin "4") (pinfunction "2_4") (pintype "passive"))
      (node (ref "R17") (pin "1") (pinfunction "1_1") (pintype "passive"))
    )
    (net (code "132") (name "Net-(JP15C-2)") (class "Default")
      (node (ref "JP15") (pin "6") (pinfunction "2_6") (pintype "passive"))
      (node (ref "R18") (pin "1") (pinfunction "1_1") (pintype "passive"))
    )
    (net (code "133") (name "Net-(JP15D-2)") (class "Default")
      (node (ref "JP15") (pin "8") (pinfunction "2_8") (pintype "passive"))
      (node (ref "R19") (pin "1") (pinfunction "1_1") (pintype "passive"))
    )
    (net (code "134") (name "Net-(JP15E-2)") (class "Default")
      (node (ref "JP15") (pin "10") (pinfunction "2_10") (pintype "passive"))
      (node (ref "R20") (pin "1") (pinfunction "1_1") (pintype "passive"))
    )
    (net (code "135") (name "Net-(LED1-PadA)") (class "Default")
      (node (ref "LED1") (pin "A") (pinfunction "A_A") (pintype "passive"))
      (node (ref "R28") (pin "2") (pinfunction "2_2") (pintype "passive"))
    )
    (net (code "136") (name "Net-(LED2-PadA)") (class "Default")
      (node (ref "LED2") (pin "A") (pinfunction "A_A") (pintype "passive"))
      (node (ref "R29") (pin "1") (pinfunction "1_1") (pintype "passive"))
    )
    (net (code "137") (name "Net-(LS1-1)") (class "Default")
      (node (ref "C5") (pin "2") (pinfunction "2_2") (pintype "passive"))
      (node (ref "D2") (pin "A") (pinfunction "A_A") (pintype "passive"))
      (node (ref "LS1") (pin "-") (pinfunction "1_-") (pintype "passive"))
      (node (ref "Q3") (pin "3") (pinfunction "C_3") (pintype "passive"))
    )
    (net (code "138") (name "Net-(Q1-B)") (class "Default")
      (node (ref "C2") (pin "1") (pinfunction "1_1") (pintype "passive"))
      (node (ref "Q1") (pin "2") (pinfunction "B_2") (pintype "passive"))
      (node (ref "R2") (pin "1") (pinfunction "1_1") (pintype "passive"))
      (node (ref "X1") (pin "1") (pinfunction "1_1") (pintype "passive"))
    )
    (net (code "139") (name "Net-(Q1-C)") (class "Default")
      (node (ref "C1") (pin "2") (pinfunction "2_2") (pintype "passive"))
      (node (ref "Q1") (pin "1") (pinfunction "C_1") (pintype "passive"))
      (node (ref "R1") (pin "2") (pinfunction "2_2") (pintype "passive"))
      (node (ref "R2") (pin "2") (pinfunction "2_2") (pintype "passive"))
      (node (ref "Z23") (pin "9") (pinfunction "I0_9") (pintype "input"))
    )
    (net (code "140") (name "Net-(Q3-B)") (class "Default")
      (node (ref "Q3") (pin "2") (pinfunction "B_2") (pintype "passive"))
      (node (ref "R9") (pin "1") (pinfunction "1_1") (pintype "passive"))
    )
    (net (code "141") (name "Net-(U2-IN+)") (class "Default")
      (node (ref "R4") (pin "S") (pinfunction "S_S") (pintype "passive"))
      (node (ref "U2") (pin "3") (pinfunction "IN+_3") (pintype "input"))
    )
    (net (code "142") (name "Net-(U2-IN-)") (class "Default")
      (node (ref "R32") (pin "2") (pinfunction "2_2") (pintype "passive"))
      (node (ref "R33") (pin "2") (pinfunction "2_2") (pintype "passive"))
      (node (ref "U2") (pin "4") (pinfunction "IN-_4") (pintype "input"))
    )
    (net (code "143") (name "Net-(U2-OUT)") (class "Default")
      (node (ref "R33") (pin "1") (pinfunction "1_1") (pintype "passive"))
      (node (ref "R34") (pin "2") (pinfunction "2_2") (pintype "passive"))
      (node (ref "U2") (pin "1") (pinfunction "OUT_1") (pintype "output"))
    )
    (net (code "144") (name "Net-(X2-1)") (class "Default")
      (node (ref "R34") (pin "1") (pinfunction "1_1") (pintype "passive"))
      (node (ref "SJ1") (pin "1") (pinfunction "1_1") (pintype "passive"))
      (node (ref "X2") (pin "2") (pinfunction "1_2") (pintype "passive"))
      (node (ref "X2") (pin "2@2") (pinfunction "2_2@2") (pintype "passive"))
    )
    (net (code "145") (name "Net-(Z1-2-A13)") (class "Default")
      (node (ref "R27") (pin "2") (pinfunction "2_2") (pintype "passive"))
      (node (ref "S1") (pin "4") (pinfunction "4_4") (pintype "passive"))
      (node (ref "Z1-2") (pin "26") (pinfunction "A13_26") (pintype "input"))
    )
    (net (code "146") (name "Net-(Z1-2-A14)") (class "Default")
      (node (ref "R8") (pin "2") (pinfunction "2_2") (pintype "passive"))
      (node (ref "S1") (pin "3") (pinfunction "3_3") (pintype "passive"))
      (node (ref "Z1-2") (pin "27") (pinfunction "A14_27") (pintype "input"))
    )
    (net (code "147") (name "Net-(Z1-2-~{CE})") (class "Default")
      (node (ref "Z1-2") (pin "20") (pinfunction "~{CE}_20") (pintype "input"))
      (node (ref "Z1-2") (pin "22") (pinfunction "~{OE}/VPP_22") (pintype "input"))
      (node (ref "Z22") (pin "8") (pinfunction "O_8") (pintype "output"))
    )
    (net (code "148") (name "Net-(Z1B-CLK)") (class "Default")
      (node (ref "Z1") (pin "11") (pinfunction "CLK_11") (pintype "input"))
      (node (ref "Z41") (pin "8") (pinfunction "O_8") (pintype "output"))
    )
    (net (code "149") (name "Net-(Z1B-Q)") (class "Default")
      (node (ref "Z1") (pin "9") (pinfunction "Q_9") (pintype "output"))
      (node (ref "Z31") (pin "9") (pinfunction "I0_9") (pintype "input"))
    )
    (net (code "150") (name "Net-(Z3-4A-~{CE})") (class "Default")
      (node (ref "JP3") (pin "2") (pinfunction "2_2") (pintype "passive"))
      (node (ref "Z3-4") (pin "20") (pinfunction "~{CE}_20") (pintype "input"))
    )
    (net (code "151") (name "Net-(Z10A-CLR)") (class "Default")
      (node (ref "Z10") (pin "2") (pinfunction "CLR_2") (pintype "input"))
      (node (ref "Z21") (pin "8") (pinfunction "O_8") (pintype "output"))
    )
    (net (code "152") (name "Net-(Z11A-CLR)") (class "Default")
      (node (ref "Z11") (pin "12") (pinfunction "CLR_12") (pintype "input"))
      (node (ref "Z11") (pin "2") (pinfunction "CLR_2") (pintype "input"))
      (node (ref "Z20") (pin "3") (pinfunction "O_3") (pintype "output"))
    )
    (net (code "153") (name "Net-(Z14A-1G)") (class "Default")
      (node (ref "Z14") (pin "1") (pinfunction "1G_1") (pintype "input"))
      (node (ref "Z14") (pin "15") (pinfunction "2G_15") (pintype "input"))
      (node (ref "Z23") (pin "2") (pinfunction "I1_2") (pintype "input"))
      (node (ref "Z26") (pin "8") (pinfunction "O_8") (pintype "output"))
    )
    (net (code "154") (name "Net-(Z15A-1G)") (class "Default")
      (node (ref "D11") (pin "C") (pinfunction "C_C") (pintype "passive"))
      (node (ref "R26") (pin "2") (pinfunction "2_2") (pintype "passive"))
      (node (ref "Z15") (pin "1") (pinfunction "1G_1") (pintype "input"))
      (node (ref "Z15") (pin "15") (pinfunction "2G_15") (pintype "input"))
      (node (ref "Z16") (pin "1") (pinfunction "1G_1") (pintype "input"))
      (node (ref "Z16") (pin "14") (pinfunction "2A2_14") (pintype "input"))
      (node (ref "Z24") (pin "2") (pinfunction "I0_2") (pintype "input"))
      (node (ref "Z24") (pin "5") (pinfunction "I0_5") (pintype "input"))
      (node (ref "Z26") (pin "13") (pinfunction "I1_13") (pintype "input"))
    )
    (net (code "155") (name "Net-(Z16A-2Y2)") (class "Default")
      (node (ref "D11") (pin "A") (pinfunction "A_A") (pintype "passive"))
      (node (ref "Z16") (pin "13") (pinfunction "2Y2_13") (pintype "tri_state"))
    )
    (net (code "156") (name "Net-(Z17A-1G)") (class "Default")
      (node (ref "Z17") (pin "1") (pinfunction "1G_1") (pintype "input"))
      (node (ref "Z17") (pin "15") (pinfunction "2G_15") (pintype "input"))
      (node (ref "Z18") (pin "1") (pinfunction "1G_1") (pintype "input"))
      (node (ref "Z23") (pin "6") (pinfunction "O_6") (pintype "output"))
    )
    (net (code "157") (name "Net-(Z18A-1Y2)") (class "Default")
      (node (ref "R23") (pin "2") (pinfunction "2_2") (pintype "passive"))
      (node (ref "Z18") (pin "5") (pinfunction "1Y2_5") (pintype "tri_state"))
      (node (ref "Z7-8") (pin "24") (pinfunction "A2_24") (pintype "input"))
    )
    (net (code "158") (name "Net-(Z18A-1Y3)") (class "Default")
      (node (ref "R22") (pin "2") (pinfunction "2_2") (pintype "passive"))
      (node (ref "Z18") (pin "7") (pinfunction "1Y3_7") (pintype "tri_state"))
      (node (ref "Z7-8") (pin "23") (pinfunction "A1_23") (pintype "input"))
    )
    (net (code "159") (name "Net-(Z18A-1Y4)") (class "Default")
      (node (ref "R21") (pin "2") (pinfunction "2_2") (pintype "passive"))
      (node (ref "Z18") (pin "9") (pinfunction "1Y4_9") (pintype "tri_state"))
      (node (ref "Z7-8") (pin "21") (pinfunction "A0_21") (pintype "input"))
    )
    (net (code "160") (name "Net-(Z18A-2A2)") (class "Default")
      (node (ref "C3") (pin "2") (pinfunction "2_2") (pintype "passive"))
      (node (ref "R5") (pin "2") (pinfunction "2_2") (pintype "passive"))
      (node (ref "R7") (pin "1") (pinfunction "1_1") (pintype "passive"))
      (node (ref "Z18") (pin "14") (pinfunction "2A2_14") (pintype "input"))
    )
    (net (code "161") (name "Net-(Z19A-O)") (class "Default")
      (node (ref "Z19") (pin "3") (pinfunction "O_3") (pintype "output"))
      (node (ref "Z20") (pin "4") (pinfunction "I0_4") (pintype "input"))
    )
    (net (code "162") (name "Net-(Z19B-I0)") (class "Default")
      (node (ref "Z19") (pin "4") (pinfunction "I0_4") (pintype "input"))
      (node (ref "Z20") (pin "9") (pinfunction "I0_9") (pintype "input"))
      (node (ref "Z22") (pin "6") (pinfunction "O_6") (pintype "output"))
    )
    (net (code "163") (name "Net-(Z19B-O)") (class "Default")
      (node (ref "Z19") (pin "6") (pinfunction "O_6") (pintype "output"))
      (node (ref "Z28") (pin "15") (pinfunction "SH/~{LD}_15") (pintype "input"))
    )
    (net (code "164") (name "Net-(Z20A-I0)") (class "Default")
      (node (ref "Z20") (pin "1") (pinfunction "I0_1") (pintype "input"))
      (node (ref "Z21") (pin "13") (pinfunction "I2_13") (pintype "input"))
      (node (ref "Z21") (pin "6") (pinfunction "O_6") (pintype "output"))
    )
    (net (code "165") (name "Net-(Z20B-I1)") (class "Default")
      (node (ref "Z20") (pin "5") (pinfunction "I1_5") (pintype "input"))
      (node (ref "Z25") (pin "1") (pinfunction "O_1") (pintype "output"))
    )
    (net (code "166") (name "Net-(Z20C-O)") (class "Default")
      (node (ref "Z20") (pin "8") (pinfunction "O_8") (pintype "output"))
      (node (ref "Z27") (pin "11") (pinfunction "CLK_11") (pintype "input"))
    )
    (net (code "167") (name "Net-(Z20D-O)") (class "Default")
      (node (ref "Z20") (pin "11") (pinfunction "O_11") (pintype "output"))
      (node (ref "Z27") (pin "12") (pinfunction "D_12") (pintype "input"))
    )
    (net (code "168") (name "Net-(Z22A-I1)") (class "Default")
      (node (ref "Z22") (pin "2") (pinfunction "I1_2") (pintype "input"))
      (node (ref "Z25") (pin "13") (pinfunction "O_13") (pintype "output"))
    )
    (net (code "169") (name "Net-(Z22C-I0)") (class "Default")
      (node (ref "Z22") (pin "9") (pinfunction "I0_9") (pintype "input"))
      (node (ref "Z29") (pin "15") (pinfunction "Y0_15") (pintype "output"))
    )
    (net (code "170") (name "Net-(Z22C-I1)") (class "Default")
      (node (ref "Z22") (pin "10") (pinfunction "I1_10") (pintype "input"))
      (node (ref "Z29") (pin "14") (pinfunction "Y1_14") (pintype "output"))
    )
    (net (code "171") (name "Net-(Z23A-O)") (class "Default")
      (node (ref "Z23") (pin "3") (pinfunction "O_3") (pintype "output"))
      (node (ref "Z24") (pin "12") (pinfunction "I1_12") (pintype "input"))
    )
    (net (code "172") (name "Net-(Z23B-I0)") (class "Default")
      (node (ref "Z23") (pin "4") (pinfunction "I0_4") (pintype "input"))
      (node (ref "Z24") (pin "1") (pinfunction "O_1") (pintype "output"))
      (node (ref "Z5-6") (pin "20") (pinfunction "~{CE}_20") (pintype "input"))
    )
    (net (code "173") (name "Net-(Z23D-I0)") (class "Default")
      (node (ref "JP4") (pin "2") (pinfunction "2_2") (pintype "passive"))
      (node (ref "Z23") (pin "12") (pinfunction "I0_12") (pintype "input"))
    )
    (net (code "174") (name "Net-(Z23D-I1)") (class "Default")
      (node (ref "Z23") (pin "13") (pinfunction "I1_13") (pintype "input"))
      (node (ref "Z28") (pin "13") (pinfunction "QH_13") (pintype "output"))
    )
    (net (code "175") (name "Net-(Z23D-O)") (class "Default")
      (node (ref "C4") (pin "2") (pinfunction "2_2") (pintype "passive"))
      (node (ref "R35") (pin "2") (pinfunction "2_2") (pintype "passive"))
      (node (ref "Z23") (pin "11") (pinfunction "O_11") (pintype "output"))
    )
    (net (code "176") (name "Net-(Z24A-I1)") (class "Default")
      (node (ref "Z24") (pin "3") (pinfunction "I1_3") (pintype "input"))
      (node (ref "Z24") (pin "4") (pinfunction "O_4") (pintype "output"))
      (node (ref "Z7-8") (pin "20") (pinfunction "~{CE}_20") (pintype "input"))
    )
    (net (code "177") (name "Net-(Z24C-I0)") (class "Default")
      (node (ref "Z24") (pin "8") (pinfunction "I0_8") (pintype "input"))
      (node (ref "Z25") (pin "10") (pinfunction "O_10") (pintype "output"))
      (node (ref "Z27") (pin "3") (pinfunction "CLK_3") (pintype "input"))
    )
    (net (code "178") (name "Net-(Z24C-I1)") (class "Default")
      (node (ref "R9") (pin "2") (pinfunction "2_2") (pintype "passive"))
      (node (ref "Z24") (pin "13") (pinfunction "O_13") (pintype "output"))
      (node (ref "Z24") (pin "9") (pinfunction "I1_9") (pintype "input"))
    )
    (net (code "179") (name "Net-(Z24C-O)") (class "Default")
      (node (ref "Z24") (pin "10") (pinfunction "O_10") (pintype "output"))
      (node (ref "Z24") (pin "11") (pinfunction "I0_11") (pintype "input"))
    )
    (net (code "180") (name "Net-(Z25C-I0)") (class "Default")
      (node (ref "Z25") (pin "8") (pinfunction "I0_8") (pintype "input"))
      (node (ref "Z26") (pin "6") (pinfunction "O_6") (pintype "output"))
      (node (ref "Z26") (pin "9") (pinfunction "I0_9") (pintype "input"))
    )
    (net (code "181") (name "Net-(Z26A-I1)") (class "Default")
      (node (ref "R26") (pin "1") (pinfunction "1_1") (pintype "passive"))
      (node (ref "Z26") (pin "2") (pinfunction "I1_2") (pintype "input"))
      (node (ref "Z29") (pin "13") (pinfunction "Y2_13") (pintype "output"))
    )
    (net (code "182") (name "Net-(Z27A-Q)") (class "Default")
      (node (ref "R10") (pin "2") (pinfunction "2_2") (pintype "passive"))
      (node (ref "Z27") (pin "5") (pinfunction "Q_5") (pintype "output"))
    )
    (net (code "183") (name "Net-(Z27B-Q)") (class "Default")
      (node (ref "JP4") (pin "1") (pinfunction "1_1") (pintype "passive"))
      (node (ref "Z27") (pin "9") (pinfunction "Q_9") (pintype "output"))
    )
    (net (code "184") (name "Net-(Z27B-~{Q})") (class "Default")
      (node (ref "JP4") (pin "3") (pinfunction "3_3") (pintype "passive"))
      (node (ref "Z27") (pin "8") (pinfunction "~{Q}_8") (pintype "output"))
    )
    (net (code "185") (name "Net-(Z28A-A)") (class "Default")
      (node (ref "R200") (pin "2") (pinfunction "2_2") (pintype "passive"))
      (node (ref "Z28") (pin "2") (pinfunction "A_2") (pintype "input"))
      (node (ref "Z7-8") (pin "11") (pinfunction "DQ0_11") (pintype "bidirectional"))
    )
    (net (code "186") (name "Net-(Z28A-B)") (class "Default")
      (node (ref "R201") (pin "2") (pinfunction "2_2") (pintype "passive"))
      (node (ref "Z28") (pin "3") (pinfunction "B_3") (pintype "input"))
      (node (ref "Z7-8") (pin "12") (pinfunction "DQ1_12") (pintype "bidirectional"))
    )
    (net (code "187") (name "Net-(Z28A-C)") (class "Default")
      (node (ref "R202") (pin "2") (pinfunction "2_2") (pintype "passive"))
      (node (ref "Z28") (pin "4") (pinfunction "C_4") (pintype "input"))
      (node (ref "Z7-8") (pin "13") (pinfunction "DQ2_13") (pintype "bidirectional"))
    )
    (net (code "188") (name "Net-(Z28A-D)") (class "Default")
      (node (ref "R203") (pin "2") (pinfunction "2_2") (pintype "passive"))
      (node (ref "Z28") (pin "5") (pinfunction "D_5") (pintype "input"))
      (node (ref "Z7-8") (pin "15") (pinfunction "DQ3_15") (pintype "bidirectional"))
    )
    (net (code "189") (name "Net-(Z28A-E)") (class "Default")
      (node (ref "R204") (pin "2") (pinfunction "2_2") (pintype "passive"))
      (node (ref "Z28") (pin "10") (pinfunction "E_10") (pintype "input"))
      (node (ref "Z7-8") (pin "16") (pinfunction "DQ4_16") (pintype "bidirectional"))
    )
    (net (code "190") (name "Net-(Z28A-F)") (class "Default")
      (node (ref "R205") (pin "2") (pinfunction "2_2") (pintype "passive"))
      (node (ref "Z28") (pin "11") (pinfunction "F_11") (pintype "input"))
      (node (ref "Z7-8") (pin "17") (pinfunction "DQ5_17") (pintype "bidirectional"))
    )
    (net (code "191") (name "Net-(Z28A-G)") (class "Default")
      (node (ref "R206") (pin "2") (pinfunction "2_2") (pintype "passive"))
      (node (ref "Z28") (pin "12") (pinfunction "G_12") (pintype "input"))
      (node (ref "Z7-8") (pin "18") (pinfunction "DQ6_18") (pintype "bidirectional"))
    )
    (net (code "192") (name "Net-(Z28A-H)") (class "Default")
      (node (ref "R207") (pin "2") (pinfunction "2_2") (pintype "passive"))
      (node (ref "Z28") (pin "14") (pinfunction "H_14") (pintype "input"))
      (node (ref "Z7-8") (pin "19") (pinfunction "DQ7_19") (pintype "bidirectional"))
    )
    (net (code "193") (name "Net-(Z29A-Y3)") (class "Default")
      (node (ref "JP3") (pin "1") (pinfunction "1_1") (pintype "passive"))
      (node (ref "Z29") (pin "12") (pinfunction "Y3_12") (pintype "output"))
      (node (ref "Z31") (pin "3") (pinfunction "I0_3") (pintype "input"))
    )
    (net (code "194") (name "Net-(Z29A-Y4)") (class "Default")
      (node (ref "Z29") (pin "11") (pinfunction "Y4_11") (pintype "output"))
      (node (ref "Z31") (pin "4") (pinfunction "I1_4") (pintype "input"))
    )
    (net (code "195") (name "Net-(Z29A-Y5)") (class "Default")
      (node (ref "Z29") (pin "10") (pinfunction "Y5_10") (pintype "output"))
      (node (ref "Z31") (pin "5") (pinfunction "I2_5") (pintype "input"))
    )
    (net (code "196") (name "Net-(Z29A-Y6)") (class "Default")
      (node (ref "Z29") (pin "9") (pinfunction "Y6_9") (pintype "output"))
      (node (ref "Z31") (pin "2") (pinfunction "I1_2") (pintype "input"))
    )
    (net (code "197") (name "Net-(Z29A-Y7)") (class "Default")
      (node (ref "Z29") (pin "7") (pinfunction "Y7_7") (pintype "output"))
      (node (ref "Z31") (pin "13") (pinfunction "I2_13") (pintype "input"))
    )
    (net (code "198") (name "Net-(Z30A-O)") (class "Default")
      (node (ref "Z30") (pin "3") (pinfunction "O_3") (pintype "output"))
      (node (ref "Z5-6") (pin "22") (pinfunction "~{OE}_22") (pintype "input"))
      (node (ref "Z7-8") (pin "22") (pinfunction "~{OE}_22") (pintype "input"))
    )
    (net (code "199") (name "Net-(Z31A-I0)") (class "Default")
      (node (ref "Z31") (pin "1") (pinfunction "I0_1") (pintype "input"))
      (node (ref "Z31") (pin "6") (pinfunction "O_6") (pintype "output"))
    )
    (net (code "200") (name "Net-(Z31A-O)") (class "Default")
      (node (ref "JP3") (pin "3") (pinfunction "3_3") (pintype "passive"))
      (node (ref "Z31") (pin "12") (pinfunction "O_12") (pintype "output"))
    )
    (net (code "201") (name "Net-(Z31C-I1)") (class "Default")
      (node (ref "R35") (pin "1") (pinfunction "1_1") (pintype "passive"))
      (node (ref "Z31") (pin "10") (pinfunction "I1_10") (pintype "input"))
    )
    (net (code "202") (name "Net-(Z31C-O)") (class "Default")
      (node (ref "R3") (pin "A") (pinfunction "A_A") (pintype "passive"))
      (node (ref "Z31") (pin "8") (pinfunction "O_8") (pintype "output"))
    )
    (net (code "203") (name "Net-(Z40-CLK)") (class "Default")
      (node (ref "JP9") (pin "2") (pinfunction "2_2") (pintype "passive"))
      (node (ref "Z40") (pin "1") (pinfunction "CLK_1") (pintype "input"))
    )
    (net (code "204") (name "Net-(Z40-O1)") (class "Default")
      (node (ref "D12") (pin "C") (pinfunction "C_C") (pintype "passive"))
      (node (ref "SJ9") (pin "2") (pinfunction "2_2") (pintype "passive"))
      (node (ref "Z40") (pin "19") (pinfunction "O1_19") (pintype "output"))
    )
    (net (code "205") (name "Net-(Z40-O2)") (class "Default")
      (node (ref "D13") (pin "C") (pinfunction "C_C") (pintype "passive"))
      (node (ref "SJ8") (pin "2") (pinfunction "2_2") (pintype "passive"))
      (node (ref "Z40") (pin "18") (pinfunction "O2_18") (pintype "output"))
    )
    (net (code "206") (name "Net-(Z40-O3)") (class "Default")
      (node (ref "D14") (pin "C") (pinfunction "C_C") (pintype "passive"))
      (node (ref "SJ2") (pin "2") (pinfunction "2_2") (pintype "passive"))
      (node (ref "Z40") (pin "17") (pinfunction "O3_17") (pintype "output"))
    )
    (net (code "207") (name "Net-(Z40-O4)") (class "Default")
      (node (ref "D15") (pin "C") (pinfunction "C_C") (pintype "passive"))
      (node (ref "SJ3") (pin "2") (pinfunction "2_2") (pintype "passive"))
      (node (ref "Z40") (pin "16") (pinfunction "O4_16") (pintype "output"))
    )
    (net (code "208") (name "Net-(Z40-O5)") (class "Default")
      (node (ref "D16") (pin "C") (pinfunction "C_C") (pintype "passive"))
      (node (ref "SJ4") (pin "2") (pinfunction "2_2") (pintype "passive"))
      (node (ref "Z40") (pin "15") (pinfunction "O5_15") (pintype "output"))
    )
    (net (code "209") (name "Net-(Z40-O6)") (class "Default")
      (node (ref "D17") (pin "C") (pinfunction "C_C") (pintype "passive"))
      (node (ref "SJ5") (pin "2") (pinfunction "2_2") (pintype "passive"))
      (node (ref "Z40") (pin "14") (pinfunction "O6_14") (pintype "output"))
    )
    (net (code "210") (name "Net-(Z41A-O)") (class "Default")
      (node (ref "Z41") (pin "3") (pinfunction "O_3") (pintype "output"))
      (node (ref "Z41") (pin "4") (pinfunction "I0_4") (pintype "input"))
    )
    (net (code "211") (name "Net-(Z41B-O)") (class "Default")
      (node (ref "Z41") (pin "10") (pinfunction "I1_10") (pintype "input"))
      (node (ref "Z41") (pin "6") (pinfunction "O_6") (pintype "output"))
    )
    (net (code "212") (name "VCC") (class "Default")
      (node (ref "11B1") (pin "1") (pinfunction "P_1") (pintype "passive"))
      (node (ref "4A") (pin "1") (pinfunction "P_1") (pintype "passive"))
      (node (ref "C12") (pin "+") (pinfunction "+_+") (pintype "passive"))
      (node (ref "C13") (pin "2") (pinfunction "2_2") (pintype "passive"))
      (node (ref "C14") (pin "2") (pinfunction "2_2") (pintype "passive"))
      (node (ref "C15") (pin "2") (pinfunction "2_2") (pintype "passive"))
      (node (ref "C16") (pin "2") (pinfunction "2_2") (pintype "passive"))
      (node (ref "C17") (pin "2") (pinfunction "2_2") (pintype "passive"))
      (node (ref "C18") (pin "2") (pinfunction "2_2") (pintype "passive"))
      (node (ref "C19") (pin "2") (pinfunction "2_2") (pintype "passive"))
      (node (ref "C20") (pin "2") (pinfunction "2_2") (pintype "passive"))
      (node (ref "C21") (pin "2") (pinfunction "2_2") (pintype "passive"))
      (node (ref "D2") (pin "C") (pinfunction "C_C") (pintype "passive"))
      (node (ref "JP8") (pin "1") (pinfunction "1_1") (pintype "passive"))
      (node (ref "JP8") (pin "2") (pinfunction "2_2") (pintype "passive"))
      (node (ref "JP9") (pin "1") (pinfunction "1_1") (pintype "passive"))
      (node (ref "LS1") (pin "+") (pinfunction "2_+") (pintype "passive"))
      (node (ref "R1") (pin "1") (pinfunction "1_1") (pintype "passive"))
      (node (ref "R24") (pin "2") (pinfunction "2_2") (pintype "passive"))
      (node (ref "R25") (pin "2") (pinfunction "2_2") (pintype "passive"))
      (node (ref "R27") (pin "1") (pinfunction "1_1") (pintype "passive"))
      (node (ref "R28") (pin "1") (pinfunction "1_1") (pintype "passive"))
      (node (ref "R3") (pin "E") (pinfunction "E_E") (pintype "passive"))
      (node (ref "R30") (pin "1") (pinfunction "1_1") (pintype "passive"))
      (node (ref "R31") (pin "1") (pinfunction "1_1") (pintype "passive"))
      (node (ref "R36") (pin "2") (pinfunction "2_2") (pintype "passive"))
      (node (ref "R37") (pin "2") (pinfunction "2_2") (pintype "passive"))
      (node (ref "R38") (pin "2") (pinfunction "2_2") (pintype "passive"))
      (node (ref "R39") (pin "2") (pinfunction "2_2") (pintype "passive"))
      (node (ref "R40") (pin "2") (pinfunction "2_2") (pintype "passive"))
      (node (ref "R41") (pin "2") (pinfunction "2_2") (pintype "passive"))
      (node (ref "R7") (pin "2") (pinfunction "2_2") (pintype "passive"))
      (node (ref "R8") (pin "1") (pinfunction "1_1") (pintype "passive"))
      (node (ref "RN1") (pin "1") (pinfunction "1_1") (pintype "passive"))
      (node (ref "U1") (pin "3") (pinfunction "VO_3") (pintype "passive"))
      (node (ref "U2") (pin "5") (pinfunction "VCC_5") (pintype "power_in"))
      (node (ref "Z0") (pin "11") (pinfunction "VCC_11") (pintype "power_in"))
      (node (ref "Z1") (pin "10") (pinfunction "PRE_10") (pintype "input"))
      (node (ref "Z1") (pin "12") (pinfunction "D_12") (pintype "input"))
      (node (ref "Z1-2") (pin "28") (pinfunction "VCC_28") (pintype "power_in"))
      (node (ref "Z16") (pin "12") (pinfunction "2A1_12") (pintype "input"))
      (node (ref "Z18") (pin "12") (pinfunction "2A1_12") (pintype "input"))
      (node (ref "Z19") (pin "13") (pinfunction "I1_13") (pintype "input"))
      (node (ref "Z22") (pin "11") (pinfunction "I2_11") (pintype "input"))
      (node (ref "Z23") (pin "1") (pinfunction "I0_1") (pintype "input"))
      (node (ref "Z23") (pin "5") (pinfunction "I1_5") (pintype "input"))
      (node (ref "Z27") (pin "1") (pinfunction "CLR_1") (pintype "input"))
      (node (ref "Z27") (pin "10") (pinfunction "PRE_10") (pintype "input"))
      (node (ref "Z27") (pin "13") (pinfunction "CLR_13") (pintype "input"))
      (node (ref "Z27") (pin "4") (pinfunction "PRE_4") (pintype "input"))
      (node (ref "Z28") (pin "9") (pinfunction "CLR_9") (pintype "input"))
      (node (ref "Z29") (pin "6") (pinfunction "G1_6") (pintype "input"))
      (node (ref "Z31") (pin "11") (pinfunction "I2_11") (pintype "input"))
      (node (ref "Z40") (pin "20") (pinfunction "VCC_20") (pintype "power_in"))
      (node (ref "Z41") (pin "1") (pinfunction "I0_1") (pintype "input"))
      (node (ref "Z41") (pin "9") (pinfunction "I0_9") (pintype "input"))
    )
    (net (code "213") (name "unconnected-(10A1-P-Pad1)") (class "Default")
      (node (ref "10A1") (pin "1") (pinfunction "P_1") (pintype "passive"))
    )
    (net (code "214") (name "unconnected-(EAR-SWITCH-PadSW)") (class "Default")
      (node (ref "EAR") (pin "SW") (pinfunction "SWITCH_SW") (pintype "passive"))
    )
    (net (code "215") (name "unconnected-(JP7-Pad3)") (class "Default")
      (node (ref "JP7") (pin "3") (pinfunction "3_3") (pintype "passive"))
    )
    (net (code "216") (name "unconnected-(MIC-SWITCH-PadSW)") (class "Default")
      (node (ref "MIC") (pin "SW") (pinfunction "SWITCH_SW") (pintype "passive"))
    )
    (net (code "217") (name "unconnected-(POWER-SWITCH-PadSW)") (class "Default")
      (node (ref "POWER") (pin "SW") (pinfunction "SWITCH_SW") (pintype "passive"))
    )
    (net (code "218") (name "unconnected-(Z1A-Q-Pad5)") (class "Default")
      (node (ref "Z1") (pin "5") (pinfunction "Q_5") (pintype "output"))
    )
    (net (code "219") (name "unconnected-(Z1A-~{Q}-Pad6)") (class "Default")
      (node (ref "Z1") (pin "6") (pinfunction "~{Q}_6") (pintype "output"))
    )
    (net (code "220") (name "unconnected-(Z1B-~{Q}-Pad8)") (class "Default")
      (node (ref "Z1") (pin "8") (pinfunction "~{Q}_8") (pintype "output"))
    )
    (net (code "221") (name "unconnected-(Z9B-QB-Pad10)") (class "Default")
      (node (ref "Z9") (pin "10") (pinfunction "QB_10") (pintype "output"))
    )
    (net (code "222") (name "unconnected-(Z9B-QC-Pad9)") (class "Default")
      (node (ref "Z9") (pin "9") (pinfunction "QC_9") (pintype "output"))
    )
    (net (code "223") (name "unconnected-(Z9B-QD-Pad8)") (class "Default")
      (node (ref "Z9") (pin "8") (pinfunction "QD_8") (pintype "output"))
    )
    (net (code "224") (name "unconnected-(Z10B-QD-Pad8)") (class "Default")
      (node (ref "Z10") (pin "8") (pinfunction "QD_8") (pintype "output"))
    )
    (net (code "225") (name "unconnected-(Z11B-QC-Pad9)") (class "Default")
      (node (ref "Z11") (pin "9") (pinfunction "QC_9") (pintype "output"))
    )
    (net (code "226") (name "unconnected-(Z11B-QD-Pad8)") (class "Default")
      (node (ref "Z11") (pin "8") (pinfunction "QD_8") (pintype "output"))
    )
    (net (code "227") (name "unconnected-(Z16A-2Y1-Pad11)") (class "Default")
      (node (ref "Z16") (pin "11") (pinfunction "2Y1_11") (pintype "tri_state"))
    )
    (net (code "228") (name "unconnected-(Z18A-2Y1-Pad11)") (class "Default")
      (node (ref "Z18") (pin "11") (pinfunction "2Y1_11") (pintype "tri_state"))
    )
    (net (code "229") (name "unconnected-(Z27A-~{Q}-Pad6)") (class "Default")
      (node (ref "Z27") (pin "6") (pinfunction "~{Q}_6") (pintype "output"))
    )
    (net (code "230") (name "unconnected-(Z40-O7-Pad13)") (class "Default")
      (node (ref "Z40") (pin "13") (pinfunction "O7_13") (pintype "output"))
    )
    (net (code "231") (name "unconnected-(Z40-O8-Pad12)") (class "Default")
      (node (ref "Z40") (pin "12") (pinfunction "O8_12") (pintype "output"))
    )
    (net (code "232") (name "unconnected-(Z40-OE-Pad11)") (class "Default")
      (node (ref "Z40") (pin "11") (pinfunction "OE_11") (pintype "input"))
    )
    (net (code "233") (name "unconnected-(Z41D-O-Pad11)") (class "Default")
      (node (ref "Z41") (pin "11") (pinfunction "O_11") (pintype "output"))
    )
  )
)
